# SM2000.net
KiCad netlist of a schematic drawn in EAGLE
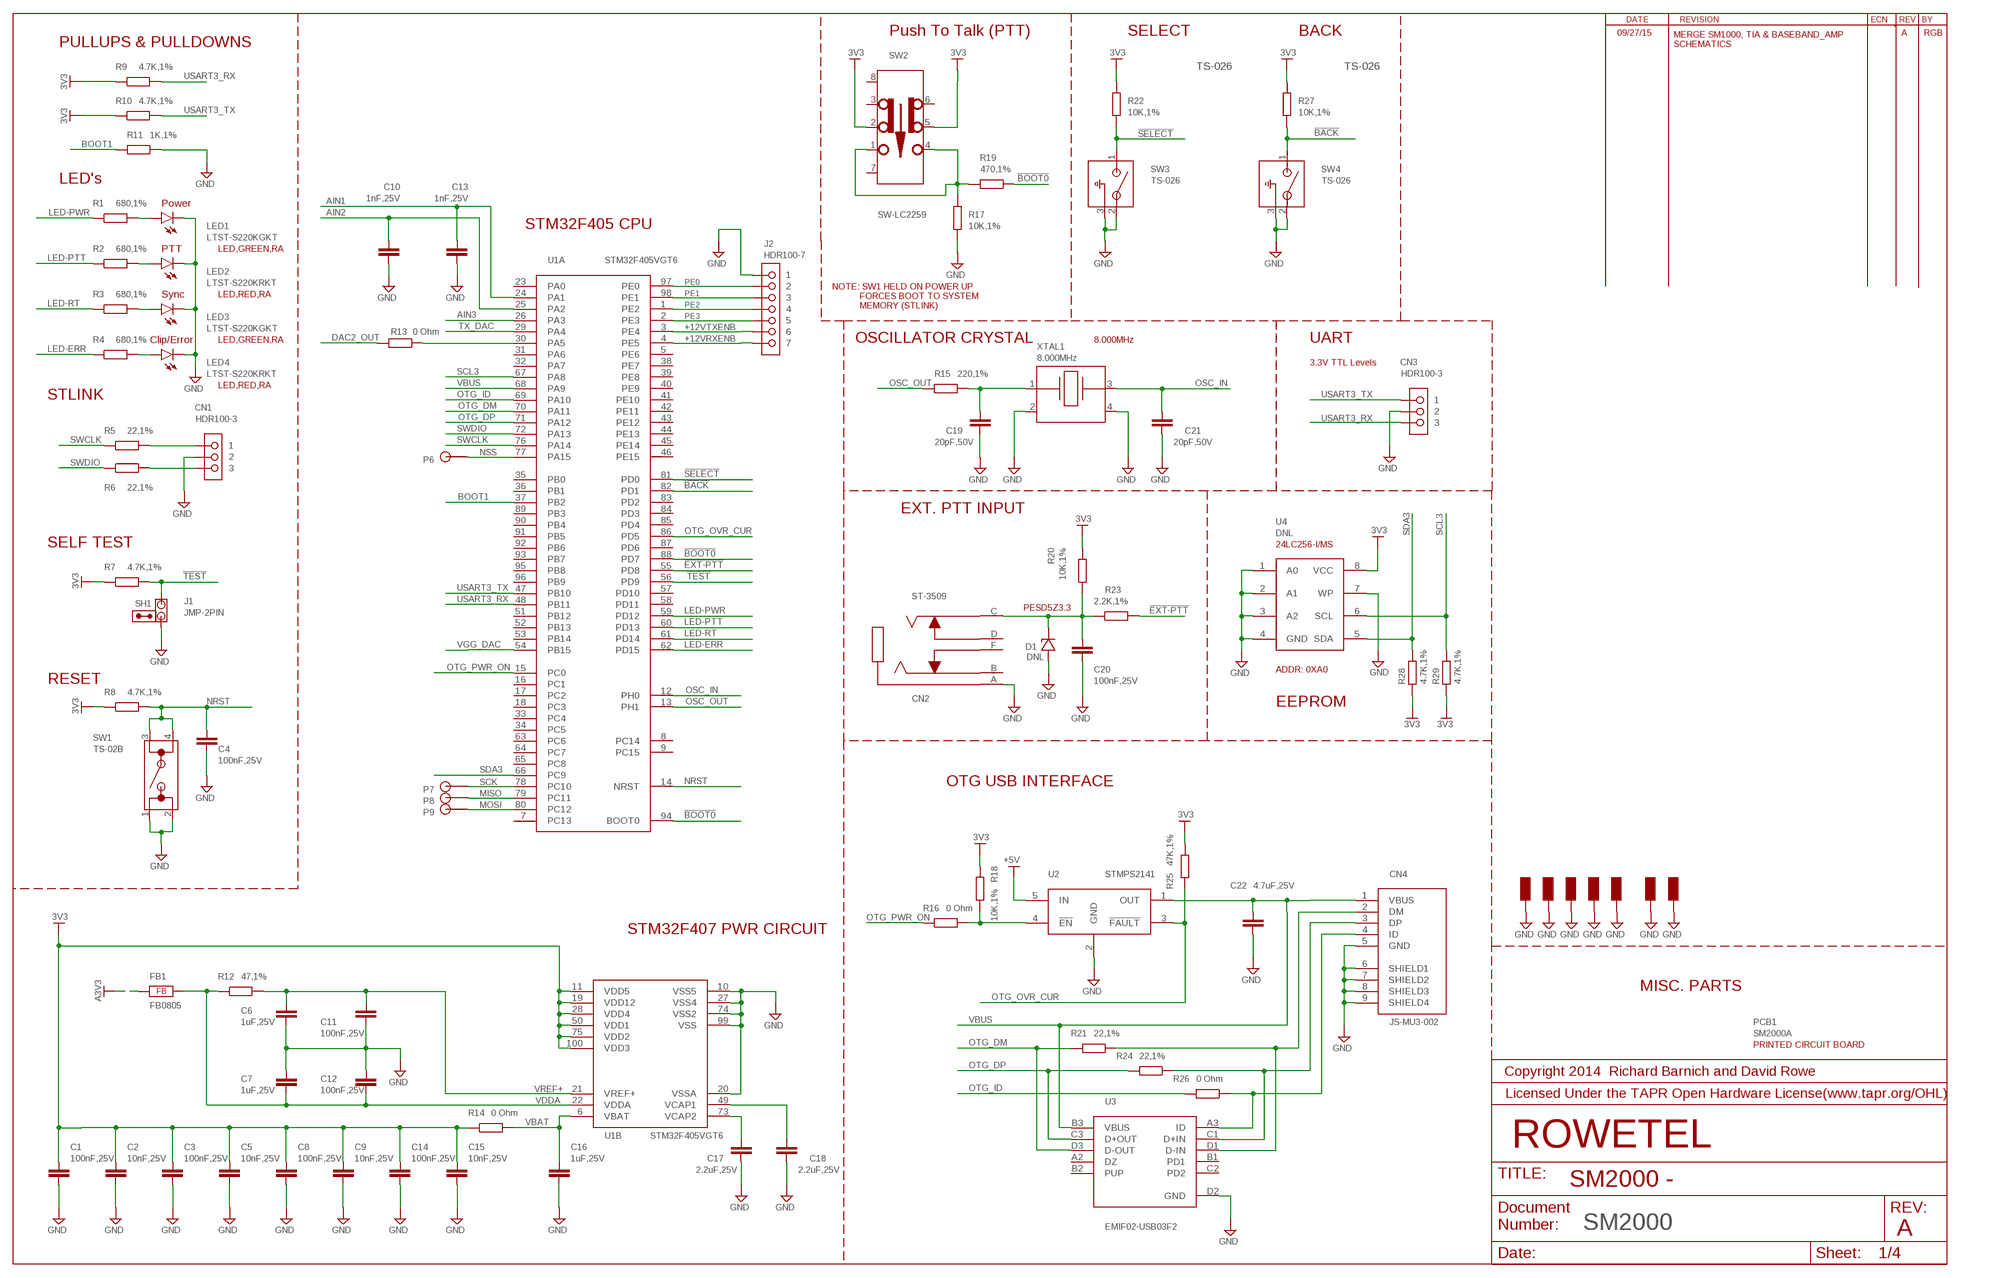
[diagram p0: schematic, sheet 1]
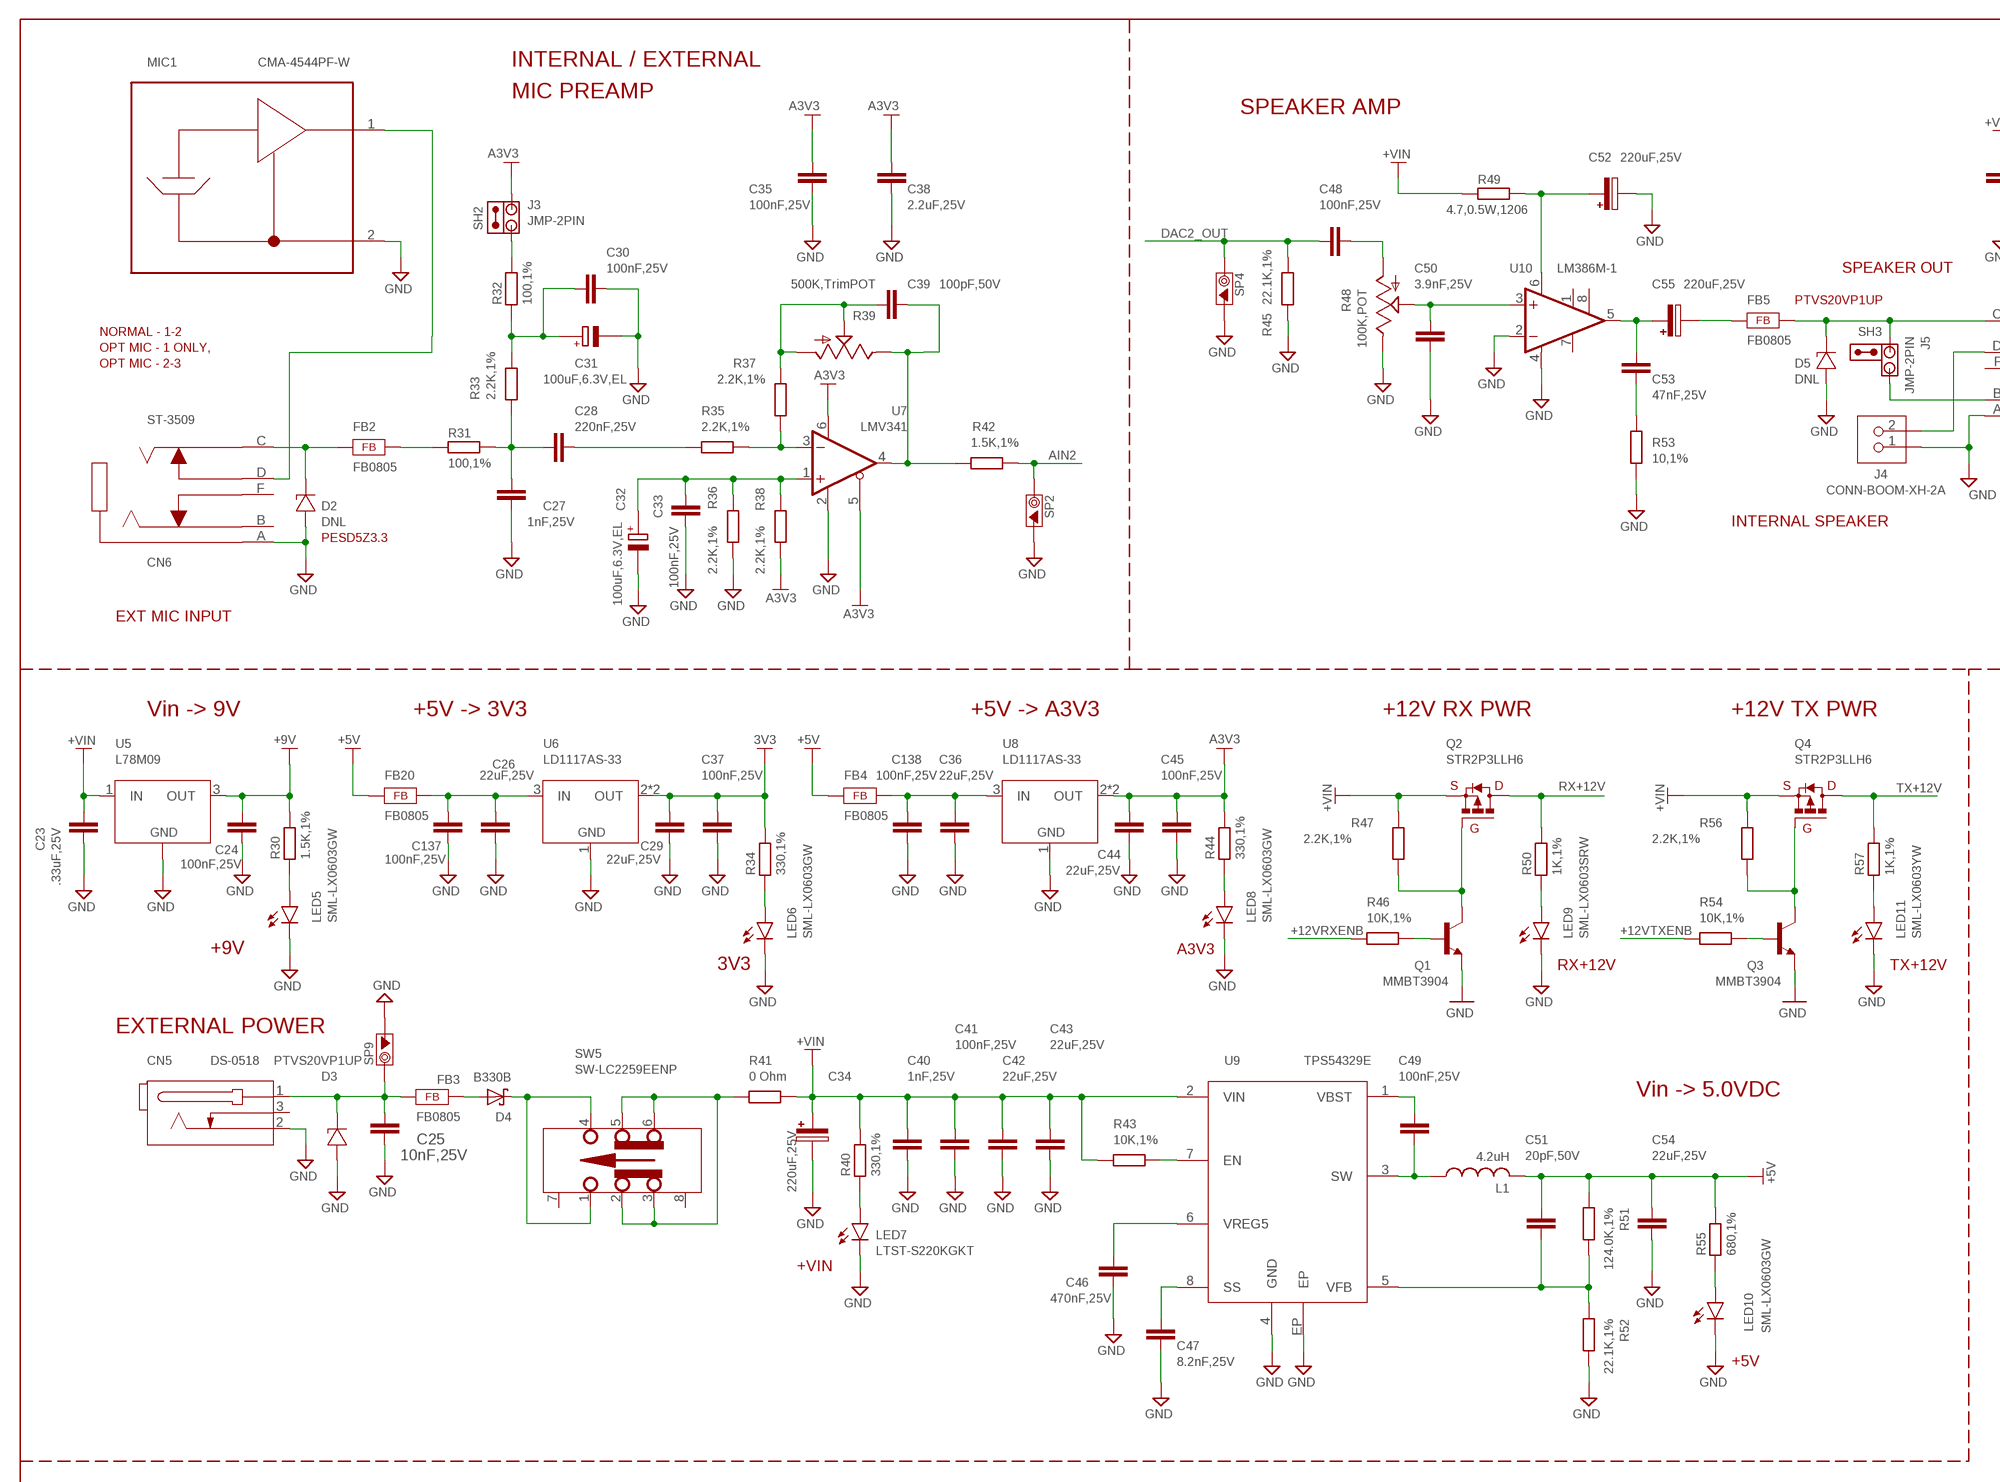
[diagram p1: schematic, sheet 2, part 1 of 2]
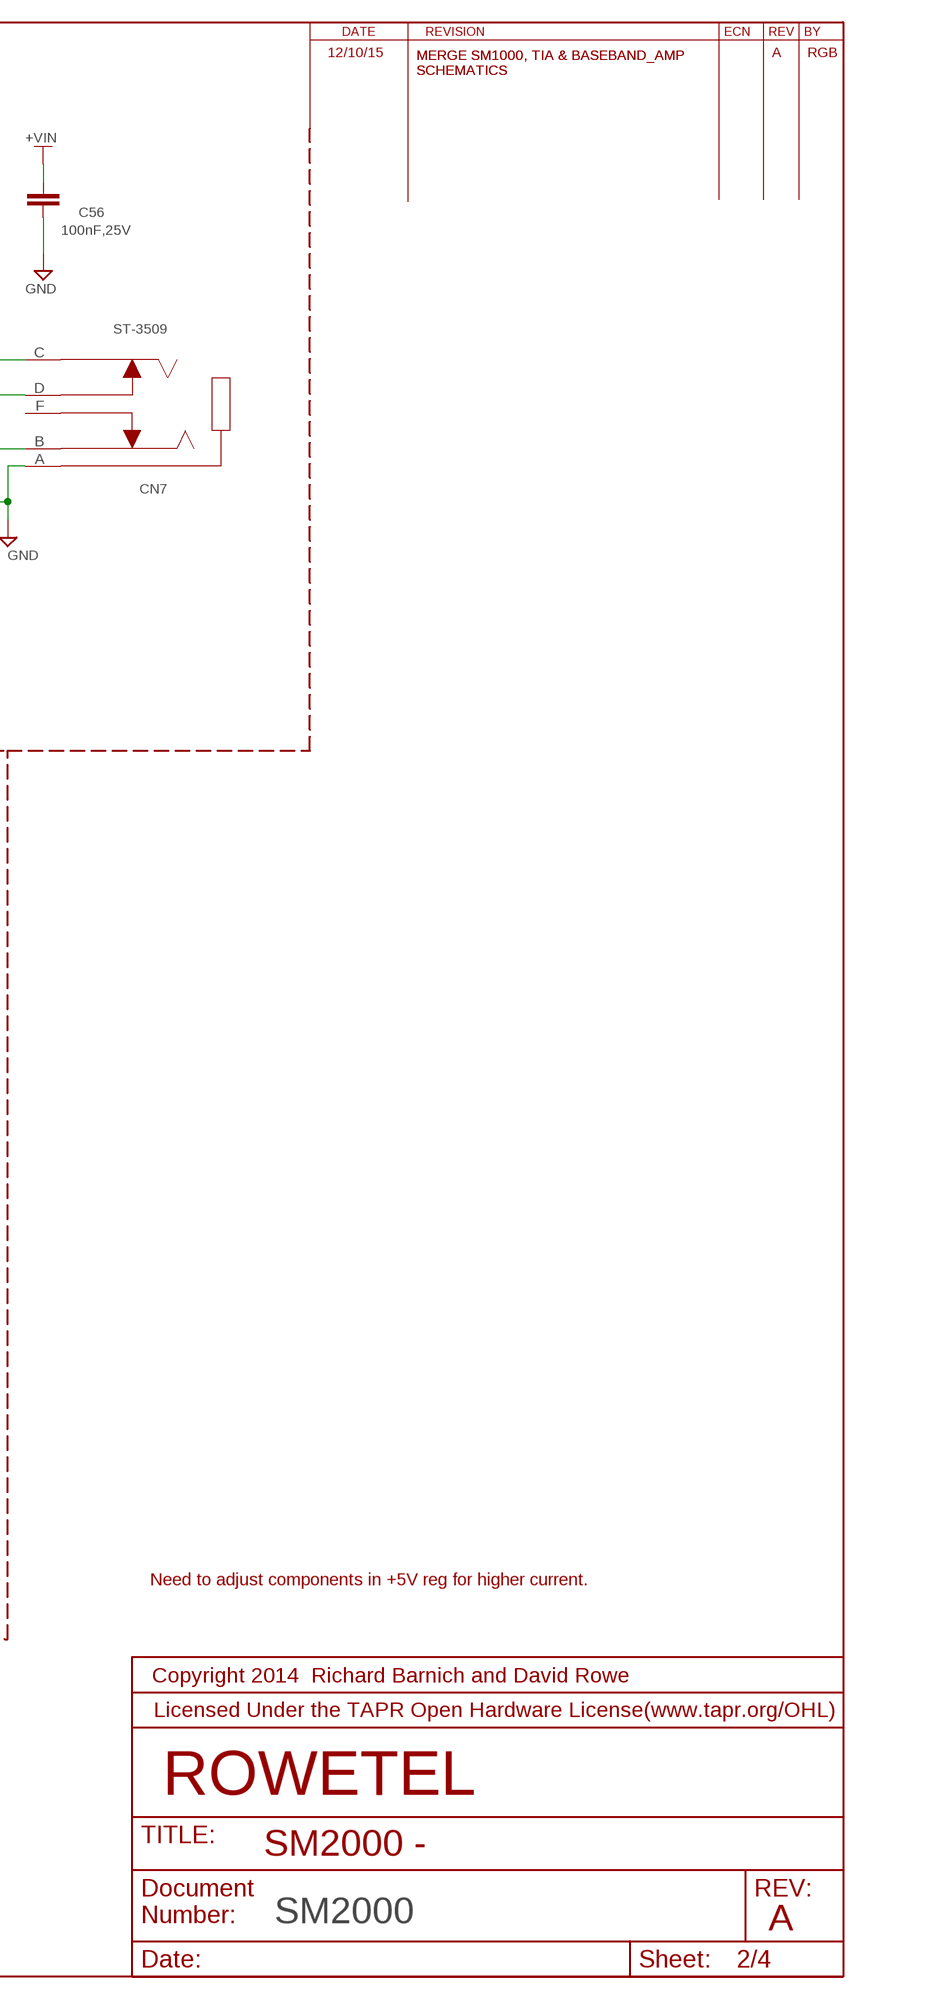
[diagram p2: schematic, sheet 2, part 2 of 2]
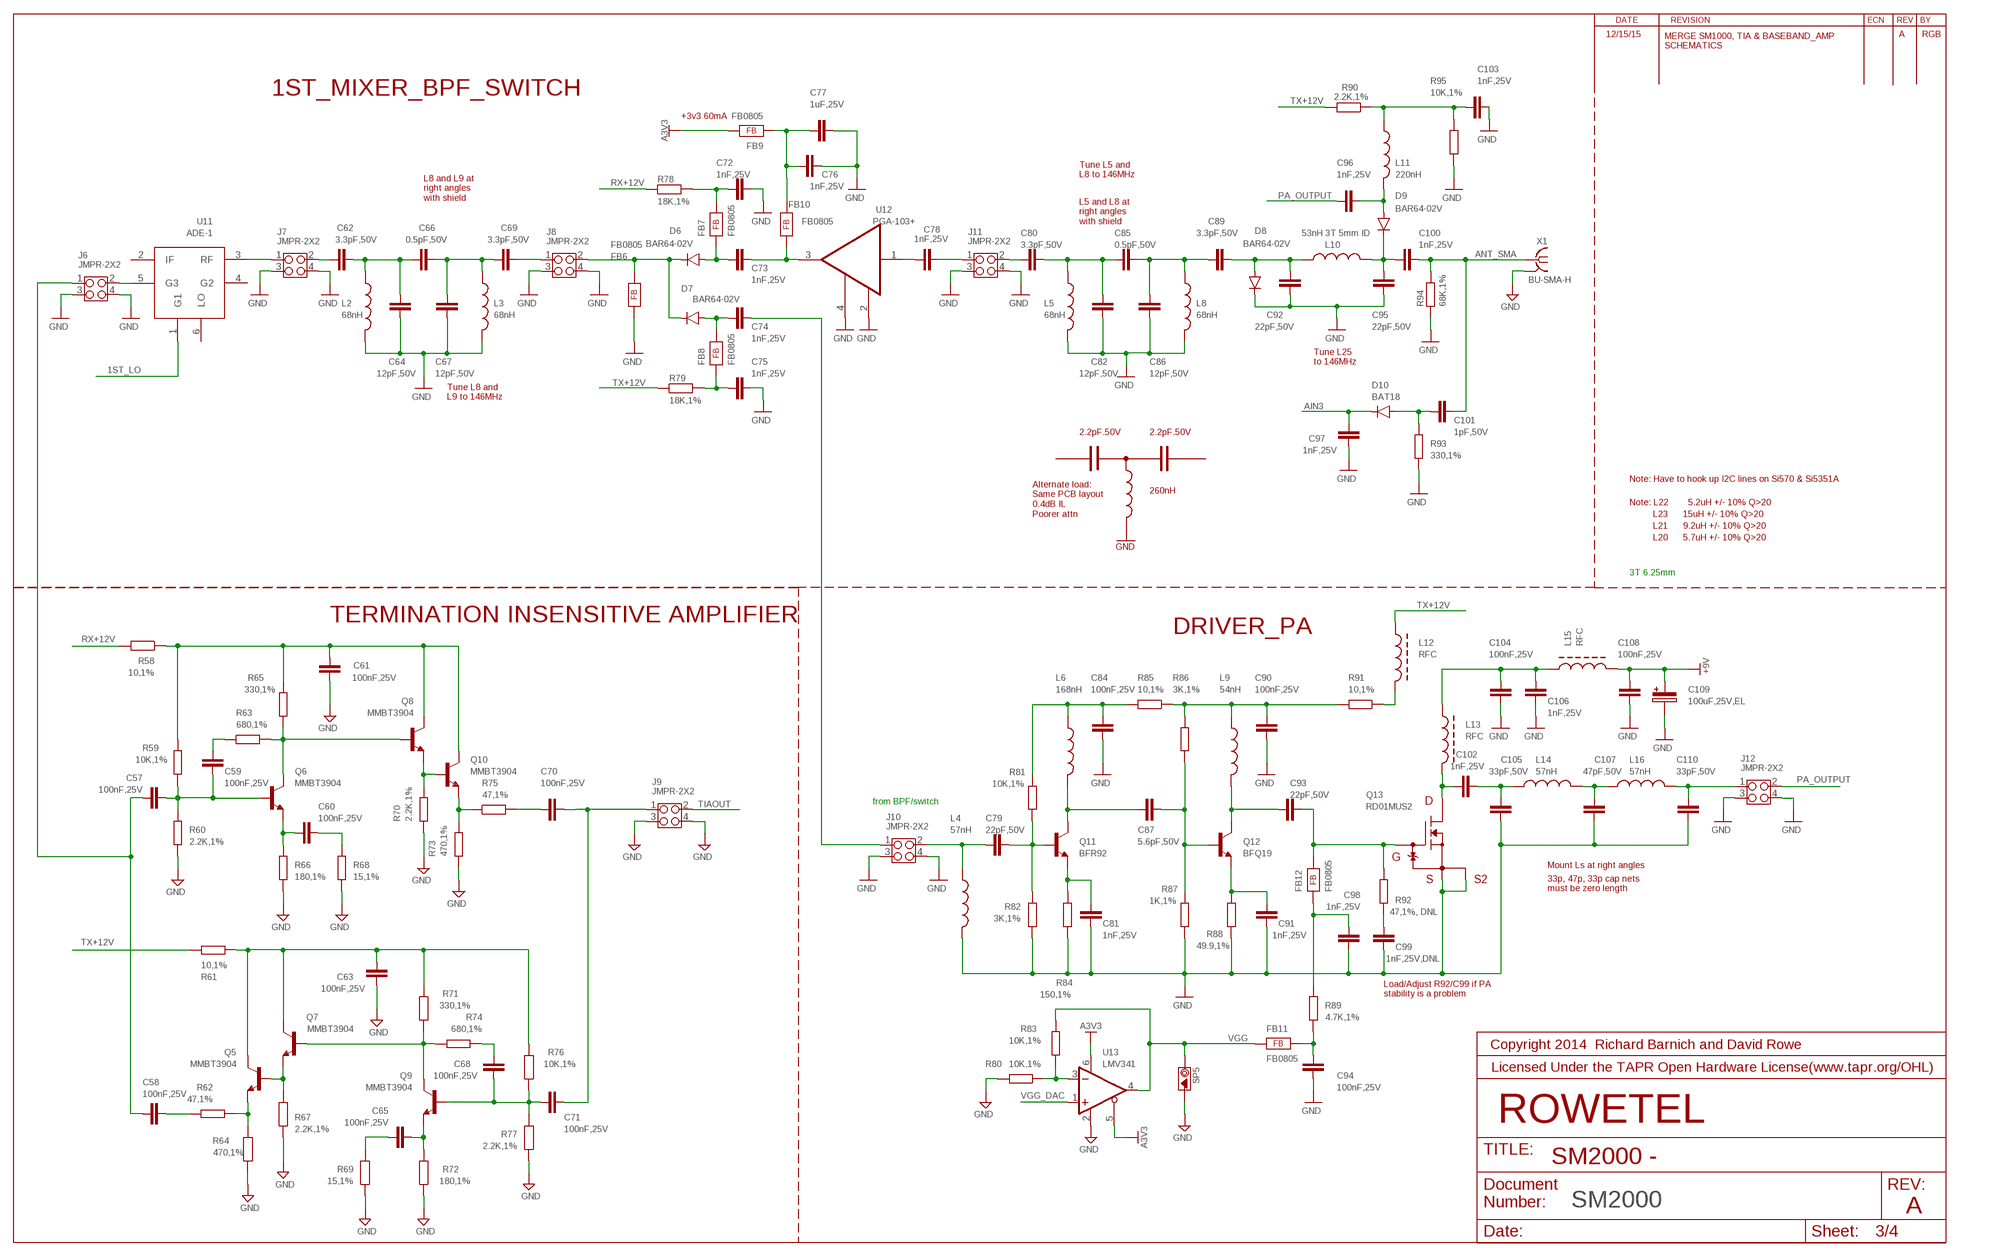
[diagram p3: schematic, sheet 3]
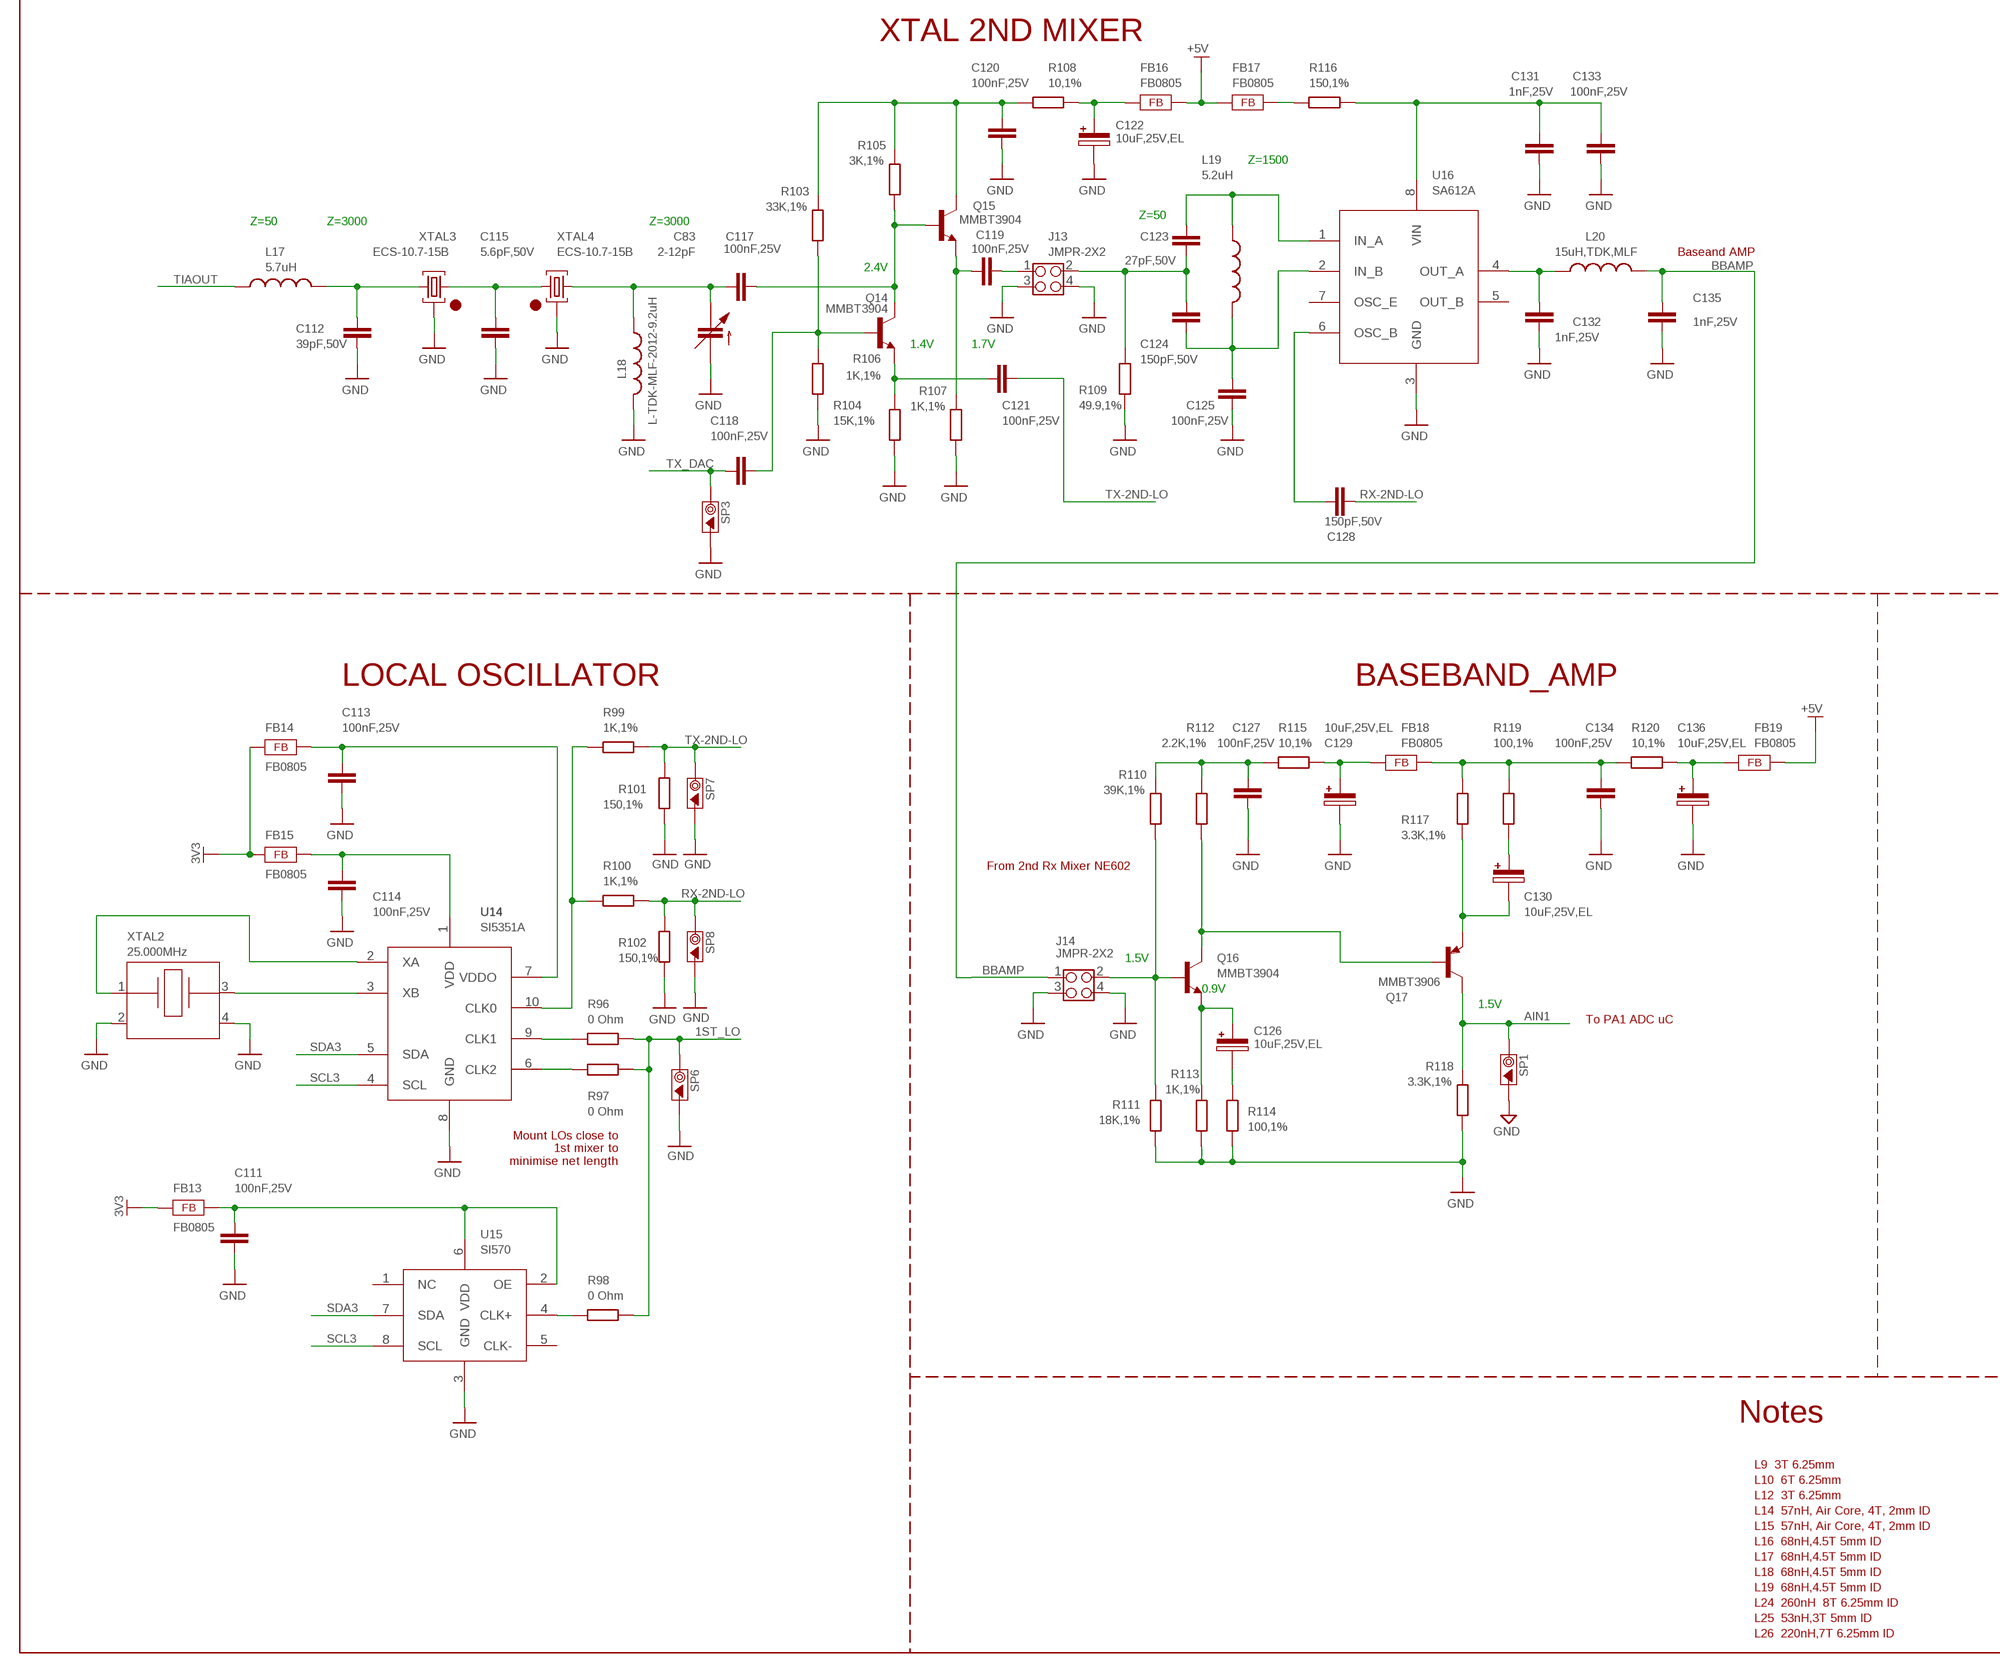
[diagram p4: schematic, sheet 4, part 1 of 2]
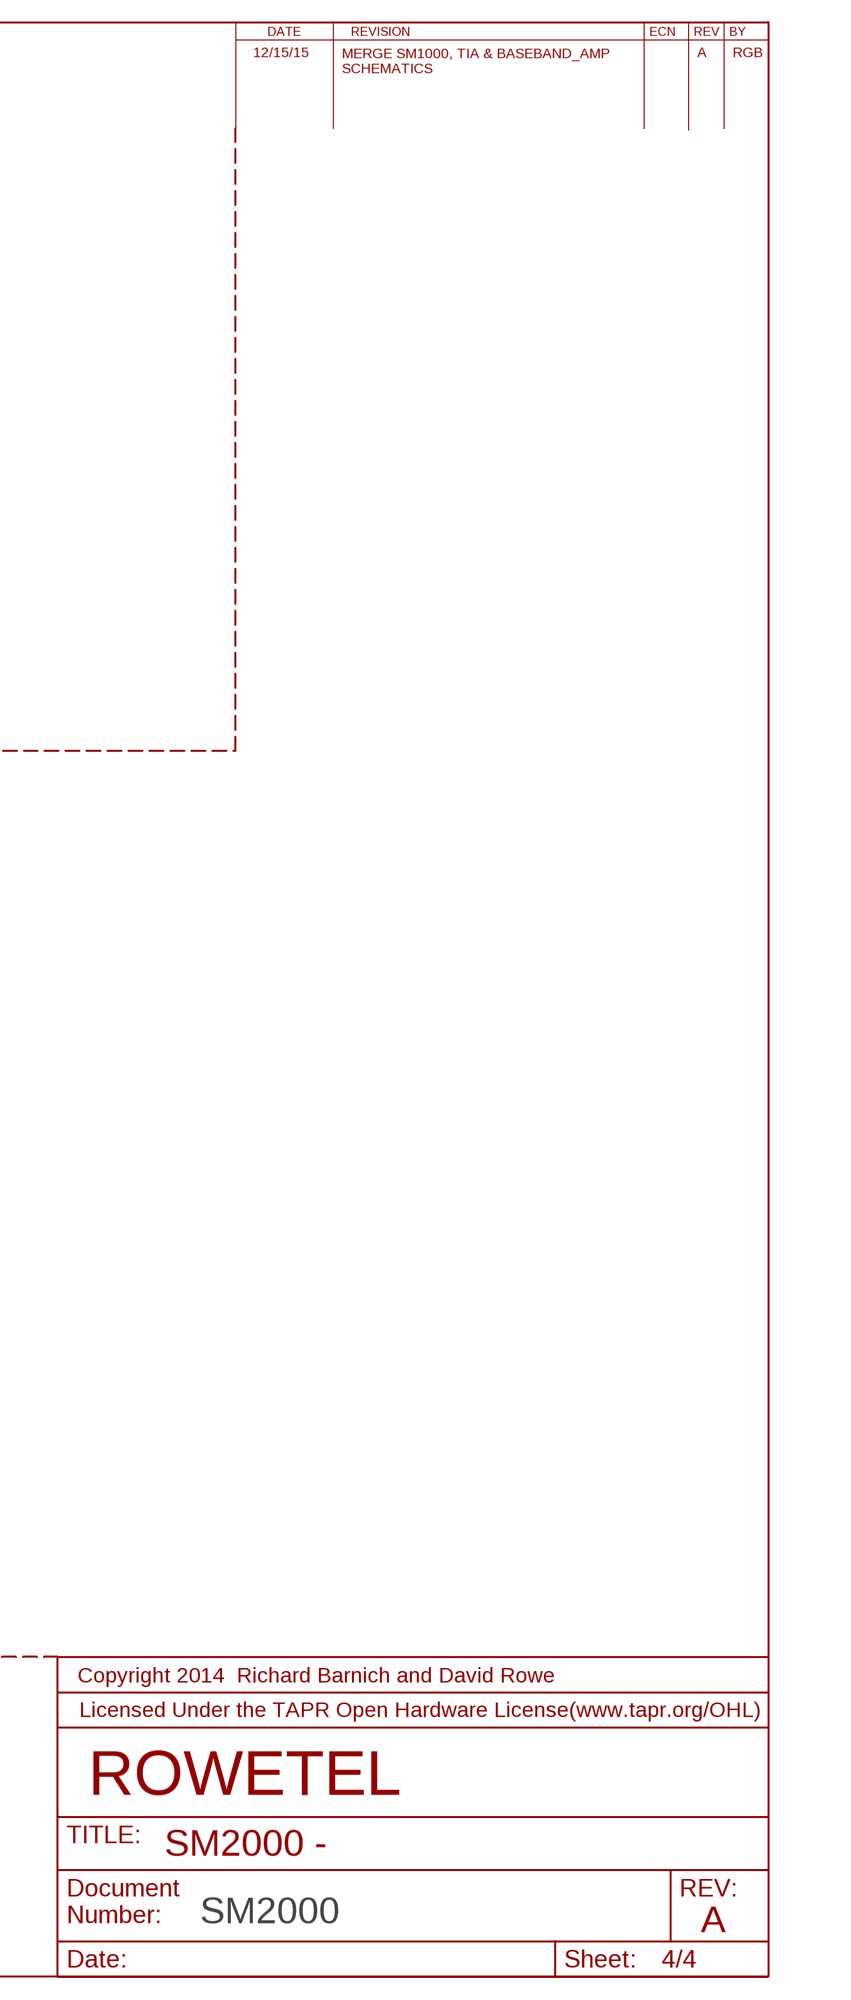
[diagram p5: schematic, sheet 4, part 2 of 2]

(export (version "E")
  (design (tool "Eeschema 10.0.6"))
  (components
    (comp (ref "C57")
      (value "100nF,25V")
      (footprint "eagle-import:C0805")
      (libsource (lib "eagle-import") (part "CAP-0805"))
    )
    (comp (ref "C58")
      (value "100nF,25V")
      (footprint "eagle-import:C0805")
      (libsource (lib "eagle-import") (part "CAP-0805"))
    )
    (comp (ref "C59")
      (value "100nF,25V")
      (footprint "eagle-import:C0805")
      (libsource (lib "eagle-import") (part "CAP-0805"))
    )
    (comp (ref "C60")
      (value "100nF,25V")
      (footprint "eagle-import:C0805")
      (libsource (lib "eagle-import") (part "CAP-0805"))
    )
    (comp (ref "C61")
      (value "100nF,25V")
      (footprint "eagle-import:C0805")
      (libsource (lib "eagle-import") (part "CAP-0805"))
    )
    (comp (ref "C62")
      (value "3.3pF,50V")
      (footprint "eagle-import:C0805")
      (libsource (lib "eagle-import") (part "CAP-0805"))
    )
    (comp (ref "C63")
      (value "100nF,25V")
      (footprint "eagle-import:C0805")
      (libsource (lib "eagle-import") (part "CAP-0805"))
    )
    (comp (ref "C64")
      (value "12pF,50V")
      (footprint "eagle-import:C0805")
      (libsource (lib "eagle-import") (part "CAP-0805"))
    )
    (comp (ref "C65")
      (value "100nF,25V")
      (footprint "eagle-import:C0805")
      (libsource (lib "eagle-import") (part "CAP-0805"))
    )
    (comp (ref "C66")
      (value "0.5pF,50V")
      (footprint "eagle-import:C0805")
      (libsource (lib "eagle-import") (part "CAP-0805"))
    )
    (comp (ref "C67")
      (value "12pF,50V")
      (footprint "eagle-import:C0805")
      (libsource (lib "eagle-import") (part "CAP-0805"))
    )
    (comp (ref "C68")
      (value "100nF,25V")
      (footprint "eagle-import:C0805")
      (libsource (lib "eagle-import") (part "CAP-0805"))
    )
    (comp (ref "C69")
      (value "3.3pF,50V")
      (footprint "eagle-import:C0805")
      (libsource (lib "eagle-import") (part "CAP-0805"))
    )
    (comp (ref "C70")
      (value "100nF,25V")
      (footprint "eagle-import:C0805")
      (libsource (lib "eagle-import") (part "CAP-0805"))
    )
    (comp (ref "C71")
      (value "100nF,25V")
      (footprint "eagle-import:C0805")
      (libsource (lib "eagle-import") (part "CAP-0805"))
    )
    (comp (ref "C72")
      (value "1nF,25V")
      (footprint "eagle-import:C0805")
      (libsource (lib "eagle-import") (part "CAP-0805"))
    )
    (comp (ref "C73")
      (value "1nF,25V")
      (footprint "eagle-import:C0805")
      (libsource (lib "eagle-import") (part "CAP-0805"))
    )
    (comp (ref "C74")
      (value "1nF,25V")
      (footprint "eagle-import:C0805")
      (libsource (lib "eagle-import") (part "CAP-0805"))
    )
    (comp (ref "C75")
      (value "1nF,25V")
      (footprint "eagle-import:C0805")
      (libsource (lib "eagle-import") (part "CAP-0805"))
    )
    (comp (ref "C76")
      (value "1nF,25V")
      (footprint "eagle-import:C0805")
      (libsource (lib "eagle-import") (part "CAP-0805"))
    )
    (comp (ref "C77")
      (value "1uF,25V")
      (footprint "eagle-import:C0805")
      (libsource (lib "eagle-import") (part "CAP-0805"))
    )
    (comp (ref "C78")
      (value "1nF,25V")
      (footprint "eagle-import:C0805")
      (libsource (lib "eagle-import") (part "CAP-0805"))
    )
    (comp (ref "C79")
      (value "22pF,50V")
      (footprint "eagle-import:C0805")
      (libsource (lib "eagle-import") (part "CAP-0805"))
    )
    (comp (ref "C80")
      (value "3.3pF,50V")
      (footprint "eagle-import:C0805")
      (libsource (lib "eagle-import") (part "CAP-0805"))
    )
    (comp (ref "C81")
      (value "1nF,25V")
      (footprint "eagle-import:C0805")
      (libsource (lib "eagle-import") (part "CAP-0805"))
    )
    (comp (ref "C82")
      (value "12pF,50V")
      (footprint "eagle-import:C0805")
      (libsource (lib "eagle-import") (part "CAP-0805"))
    )
    (comp (ref "C84")
      (value "100nF,25V")
      (footprint "eagle-import:C0805")
      (libsource (lib "eagle-import") (part "CAP-0805"))
    )
    (comp (ref "C85")
      (value "0.5pF,50V")
      (footprint "eagle-import:C0805")
      (libsource (lib "eagle-import") (part "CAP-0805"))
    )
    (comp (ref "C86")
      (value "12pF,50V")
      (footprint "eagle-import:C0805")
      (libsource (lib "eagle-import") (part "CAP-0805"))
    )
    (comp (ref "C87")
      (value "5.6pF,50V")
      (footprint "eagle-import:C0805")
      (libsource (lib "eagle-import") (part "CAP-0805"))
    )
    (comp (ref "C89")
      (value "3.3pF,50V")
      (footprint "eagle-import:C0805")
      (libsource (lib "eagle-import") (part "CAP-0805"))
    )
    (comp (ref "C90")
      (value "100nF,25V")
      (footprint "eagle-import:C0805")
      (libsource (lib "eagle-import") (part "CAP-0805"))
    )
    (comp (ref "C91")
      (value "1nF,25V")
      (footprint "eagle-import:C0805")
      (libsource (lib "eagle-import") (part "CAP-0805"))
    )
    (comp (ref "C92")
      (value "22pF,50V")
      (footprint "eagle-import:C0805")
      (libsource (lib "eagle-import") (part "CAP-0805"))
    )
    (comp (ref "C93")
      (value "22pF,50V")
      (footprint "eagle-import:C0805")
      (libsource (lib "eagle-import") (part "CAP-0805"))
    )
    (comp (ref "C94")
      (value "100nF,25V")
      (footprint "eagle-import:C0805")
      (libsource (lib "eagle-import") (part "CAP-0805"))
    )
    (comp (ref "C95")
      (value "22pF,50V")
      (footprint "eagle-import:C0805")
      (libsource (lib "eagle-import") (part "CAP-0805"))
    )
    (comp (ref "C96")
      (value "1nF,25V")
      (footprint "eagle-import:C0805")
      (libsource (lib "eagle-import") (part "CAP-0805"))
    )
    (comp (ref "C97")
      (value "1nF,25V")
      (footprint "eagle-import:C0805")
      (libsource (lib "eagle-import") (part "CAP-0805"))
    )
    (comp (ref "C98")
      (value "1nF,25V")
      (footprint "eagle-import:C0805")
      (libsource (lib "eagle-import") (part "CAP-0805"))
    )
    (comp (ref "C99")
      (value "1nF,25V,DNL")
      (footprint "eagle-import:C0805")
      (libsource (lib "eagle-import") (part "CAP-0805"))
    )
    (comp (ref "C100")
      (value "1nF,25V")
      (footprint "eagle-import:C0805")
      (libsource (lib "eagle-import") (part "CAP-0805"))
    )
    (comp (ref "C101")
      (value "1pF,50V")
      (footprint "eagle-import:C0805")
      (libsource (lib "eagle-import") (part "CAP-0805"))
    )
    (comp (ref "C102")
      (value "1nF,25V")
      (footprint "eagle-import:C0805")
      (libsource (lib "eagle-import") (part "CAP-0805"))
    )
    (comp (ref "C103")
      (value "1nF,25V")
      (footprint "eagle-import:C0805")
      (libsource (lib "eagle-import") (part "CAP-0805"))
    )
    (comp (ref "C104")
      (value "100nF,25V")
      (footprint "eagle-import:C0805")
      (libsource (lib "eagle-import") (part "CAP-0805"))
    )
    (comp (ref "C105")
      (value "33pF,50V")
      (footprint "eagle-import:C0805")
      (libsource (lib "eagle-import") (part "CAP-0805"))
    )
    (comp (ref "C106")
      (value "1nF,25V")
      (footprint "eagle-import:C0805")
      (libsource (lib "eagle-import") (part "CAP-0805"))
    )
    (comp (ref "C107")
      (value "47pF,50V")
      (footprint "eagle-import:C0805")
      (libsource (lib "eagle-import") (part "CAP-0805"))
    )
    (comp (ref "C108")
      (value "100nF,25V")
      (footprint "eagle-import:C0805")
      (libsource (lib "eagle-import") (part "CAP-0805"))
    )
    (comp (ref "C109")
      (value "100uF,25V,EL")
      (footprint "eagle-import:CAP-CHEMI-F80")
      (libsource (lib "eagle-import") (part "CAP-CHEMI-F80"))
    )
    (comp (ref "C110")
      (value "33pF,50V")
      (footprint "eagle-import:C0805")
      (libsource (lib "eagle-import") (part "CAP-0805"))
    )
    (comp (ref "D6")
      (value "BAR64-02V")
      (footprint "eagle-import:SC79_INFINEON")
      (libsource (lib "eagle-import") (part "BAR64-02V"))
    )
    (comp (ref "D7")
      (value "BAR64-02V")
      (footprint "eagle-import:SC79_INFINEON")
      (libsource (lib "eagle-import") (part "BAR64-02V"))
    )
    (comp (ref "D8")
      (value "BAR64-02V")
      (footprint "eagle-import:SC79_INFINEON")
      (libsource (lib "eagle-import") (part "BAR64-02V"))
    )
    (comp (ref "D9")
      (value "BAR64-02V")
      (footprint "eagle-import:SC79_INFINEON")
      (libsource (lib "eagle-import") (part "BAR64-02V"))
    )
    (comp (ref "D10")
      (value "BAT18")
      (footprint "eagle-import:SOT23")
      (libsource (lib "eagle-import") (part "BAT18"))
    )
    (comp (ref "FB6")
      (value "FB0805")
      (footprint "eagle-import:FE0805")
      (libsource (lib "eagle-import") (part "FB0805"))
    )
    (comp (ref "FB7")
      (value "FB0805")
      (footprint "eagle-import:FE0805")
      (libsource (lib "eagle-import") (part "FB0805"))
    )
    (comp (ref "FB8")
      (value "FB0805")
      (footprint "eagle-import:FE0805")
      (libsource (lib "eagle-import") (part "FB0805"))
    )
    (comp (ref "FB9")
      (value "FB0805")
      (footprint "eagle-import:FE0805")
      (libsource (lib "eagle-import") (part "FB0805"))
    )
    (comp (ref "FB10")
      (value "FB0805")
      (footprint "eagle-import:FE0805")
      (libsource (lib "eagle-import") (part "FB0805"))
    )
    (comp (ref "FB11")
      (value "FB0805")
      (footprint "eagle-import:FE0805")
      (libsource (lib "eagle-import") (part "FB0805"))
    )
    (comp (ref "FB12")
      (value "FB0805")
      (footprint "eagle-import:FE0805")
      (libsource (lib "eagle-import") (part "FB0805"))
    )
    (comp (ref "J6")
      (value "JMPR-2X2")
      (footprint "eagle-import:JMPR-2X2X.1")
      (libsource (lib "eagle-import") (part "JMPR-2X2"))
    )
    (comp (ref "J7")
      (value "JMPR-2X2")
      (footprint "eagle-import:JMPR-2X2X.1")
      (libsource (lib "eagle-import") (part "JMPR-2X2"))
    )
    (comp (ref "J8")
      (value "JMPR-2X2")
      (footprint "eagle-import:JMPR-2X2X.1")
      (libsource (lib "eagle-import") (part "JMPR-2X2"))
    )
    (comp (ref "J9")
      (value "JMPR-2X2")
      (footprint "eagle-import:JMPR-2X2X.1")
      (libsource (lib "eagle-import") (part "JMPR-2X2"))
    )
    (comp (ref "J10")
      (value "JMPR-2X2")
      (footprint "eagle-import:JMPR-2X2X.1")
      (libsource (lib "eagle-import") (part "JMPR-2X2"))
    )
    (comp (ref "J11")
      (value "JMPR-2X2")
      (footprint "eagle-import:JMPR-2X2X.1")
      (libsource (lib "eagle-import") (part "JMPR-2X2"))
    )
    (comp (ref "J12")
      (value "JMPR-2X2")
      (footprint "eagle-import:JMPR-2X2X.1")
      (libsource (lib "eagle-import") (part "JMPR-2X2"))
    )
    (comp (ref "L2")
      (value "68nH")
      (footprint "eagle-import:L10X15")
      (libsource (lib "eagle-import") (part "L-ROWE_15X10"))
    )
    (comp (ref "L3")
      (value "68nH")
      (footprint "eagle-import:L10X15")
      (libsource (lib "eagle-import") (part "L-ROWE_15X10"))
    )
    (comp (ref "L4")
      (value "57nH")
      (footprint "eagle-import:L10X15")
      (libsource (lib "eagle-import") (part "L-ROWE_15X10"))
    )
    (comp (ref "L5")
      (value "68nH")
      (footprint "eagle-import:L10X15")
      (libsource (lib "eagle-import") (part "L-ROWE_15X10"))
    )
    (comp (ref "L6")
      (value "168nH")
      (footprint "eagle-import:L10X15")
      (libsource (lib "eagle-import") (part "L-ROWE_15X10"))
    )
    (comp (ref "L8")
      (value "68nH")
      (footprint "eagle-import:L10X15")
      (libsource (lib "eagle-import") (part "L-ROWE_15X10"))
    )
    (comp (ref "L9")
      (value "54nH")
      (footprint "eagle-import:L10X15")
      (libsource (lib "eagle-import") (part "L-ROWE_15X10"))
    )
    (comp (ref "L10")
      (value "53nH 3T 5mm ID")
      (footprint "eagle-import:L10X15")
      (libsource (lib "eagle-import") (part "L-ROWE_15X10"))
    )
    (comp (ref "L11")
      (value "220nH")
      (footprint "eagle-import:L10X15")
      (libsource (lib "eagle-import") (part "L-ROWE_15X10"))
    )
    (comp (ref "L12")
      (value "RFC")
      (footprint "eagle-import:Z15_4")
      (libsource (lib "eagle-import") (part "RFC"))
    )
    (comp (ref "L13")
      (value "RFC")
      (footprint "eagle-import:Z15_4")
      (libsource (lib "eagle-import") (part "RFC"))
    )
    (comp (ref "L14")
      (value "57nH")
      (footprint "eagle-import:L10X15")
      (libsource (lib "eagle-import") (part "L-ROWE_15X10"))
    )
    (comp (ref "L15")
      (value "RFC")
      (footprint "eagle-import:Z15_4")
      (libsource (lib "eagle-import") (part "RFC"))
    )
    (comp (ref "L16")
      (value "57nH")
      (footprint "eagle-import:L10X15")
      (libsource (lib "eagle-import") (part "L-ROWE_15X10"))
    )
    (comp (ref "Q5")
      (value "MMBT3904")
      (footprint "eagle-import:SOT23")
      (libsource (lib "eagle-import") (part "MMBT3904"))
    )
    (comp (ref "Q6")
      (value "MMBT3904")
      (footprint "eagle-import:SOT23")
      (libsource (lib "eagle-import") (part "MMBT3904"))
    )
    (comp (ref "Q7")
      (value "MMBT3904")
      (footprint "eagle-import:SOT23")
      (libsource (lib "eagle-import") (part "MMBT3904"))
    )
    (comp (ref "Q8")
      (value "MMBT3904")
      (footprint "eagle-import:SOT23")
      (libsource (lib "eagle-import") (part "MMBT3904"))
    )
    (comp (ref "Q9")
      (value "MMBT3904")
      (footprint "eagle-import:SOT23")
      (libsource (lib "eagle-import") (part "MMBT3904"))
    )
    (comp (ref "Q10")
      (value "MMBT3904")
      (footprint "eagle-import:SOT23")
      (libsource (lib "eagle-import") (part "MMBT3904"))
    )
    (comp (ref "Q11")
      (value "BFR92")
      (footprint "eagle-import:SOT23")
      (libsource (lib "eagle-import") (part "BFR92"))
    )
    (comp (ref "Q12")
      (value "BFQ19")
      (footprint "eagle-import:SOT89")
      (libsource (lib "eagle-import") (part "BFQ19"))
    )
    (comp (ref "Q13")
      (value "RD01MUS2")
      (footprint "eagle-import:SOT89")
      (libsource (lib "eagle-import") (part "RD01MUS2"))
    )
    (comp (ref "R58")
      (value "10,1%")
      (footprint "eagle-import:R0805")
      (libsource (lib "eagle-import") (part "RES-0805"))
    )
    (comp (ref "R59")
      (value "10K,1%")
      (footprint "eagle-import:R0805")
      (libsource (lib "eagle-import") (part "RES-0805"))
    )
    (comp (ref "R60")
      (value "2.2K,1%")
      (footprint "eagle-import:R0805")
      (libsource (lib "eagle-import") (part "RES-0805"))
    )
    (comp (ref "R61")
      (value "10,1%")
      (footprint "eagle-import:R0805")
      (libsource (lib "eagle-import") (part "RES-0805"))
    )
    (comp (ref "R62")
      (value "47,1%")
      (footprint "eagle-import:R0805")
      (libsource (lib "eagle-import") (part "RES-0805"))
    )
    (comp (ref "R63")
      (value "680,1%")
      (footprint "eagle-import:R0805")
      (libsource (lib "eagle-import") (part "RES-0805"))
    )
    (comp (ref "R64")
      (value "470,1%")
      (footprint "eagle-import:R0805")
      (libsource (lib "eagle-import") (part "RES-0805"))
    )
    (comp (ref "R65")
      (value "330,1%")
      (footprint "eagle-import:R0805")
      (libsource (lib "eagle-import") (part "RES-0805"))
    )
    (comp (ref "R66")
      (value "180,1%")
      (footprint "eagle-import:R0805")
      (libsource (lib "eagle-import") (part "RES-0805"))
    )
    (comp (ref "R67")
      (value "2.2K,1%")
      (footprint "eagle-import:R0805")
      (libsource (lib "eagle-import") (part "RES-0805"))
    )
    (comp (ref "R68")
      (value "15,1%")
      (footprint "eagle-import:R0805")
      (libsource (lib "eagle-import") (part "RES-0805"))
    )
    (comp (ref "R69")
      (value "15,1%")
      (footprint "eagle-import:R0805")
      (libsource (lib "eagle-import") (part "RES-0805"))
    )
    (comp (ref "R70")
      (value "2.2K,1%")
      (footprint "eagle-import:R0805")
      (libsource (lib "eagle-import") (part "RES-0805"))
    )
    (comp (ref "R71")
      (value "330,1%")
      (footprint "eagle-import:R0805")
      (libsource (lib "eagle-import") (part "RES-0805"))
    )
    (comp (ref "R72")
      (value "180,1%")
      (footprint "eagle-import:R0805")
      (libsource (lib "eagle-import") (part "RES-0805"))
    )
    (comp (ref "R73")
      (value "470,1%")
      (footprint "eagle-import:R0805")
      (libsource (lib "eagle-import") (part "RES-0805"))
    )
    (comp (ref "R74")
      (value "680,1%")
      (footprint "eagle-import:R0805")
      (libsource (lib "eagle-import") (part "RES-0805"))
    )
    (comp (ref "R75")
      (value "47,1%")
      (footprint "eagle-import:R0805")
      (libsource (lib "eagle-import") (part "RES-0805"))
    )
    (comp (ref "R76")
      (value "10K,1%")
      (footprint "eagle-import:R0805")
      (libsource (lib "eagle-import") (part "RES-0805"))
    )
    (comp (ref "R77")
      (value "2.2K,1%")
      (footprint "eagle-import:R0805")
      (libsource (lib "eagle-import") (part "RES-0805"))
    )
    (comp (ref "R78")
      (value "18K,1%")
      (footprint "eagle-import:R0805")
      (libsource (lib "eagle-import") (part "RES-0805"))
    )
    (comp (ref "R79")
      (value "18K,1%")
      (footprint "eagle-import:R0805")
      (libsource (lib "eagle-import") (part "RES-0805"))
    )
    (comp (ref "R80")
      (value "10K,1%")
      (footprint "eagle-import:R0805")
      (libsource (lib "eagle-import") (part "RES-0805"))
    )
    (comp (ref "R81")
      (value "10K,1%")
      (footprint "eagle-import:R0805")
      (libsource (lib "eagle-import") (part "RES-0805"))
    )
    (comp (ref "R82")
      (value "3K,1%")
      (footprint "eagle-import:R0805")
      (libsource (lib "eagle-import") (part "RES-0805"))
    )
    (comp (ref "R83")
      (value "10K,1%")
      (footprint "eagle-import:R0805")
      (libsource (lib "eagle-import") (part "RES-0805"))
    )
    (comp (ref "R84")
      (value "150,1%")
      (footprint "eagle-import:R0805")
      (libsource (lib "eagle-import") (part "RES-0805"))
    )
    (comp (ref "R85")
      (value "10,1%")
      (footprint "eagle-import:R0805")
      (libsource (lib "eagle-import") (part "RES-0805"))
    )
    (comp (ref "R86")
      (value "3K,1%")
      (footprint "eagle-import:R0805")
      (libsource (lib "eagle-import") (part "RES-0805"))
    )
    (comp (ref "R87")
      (value "1K,1%")
      (footprint "eagle-import:R0805")
      (libsource (lib "eagle-import") (part "RES-0805"))
    )
    (comp (ref "R88")
      (value "49.9,1%")
      (footprint "eagle-import:R0805")
      (libsource (lib "eagle-import") (part "RES-0805"))
    )
    (comp (ref "R89")
      (value "4.7K,1%")
      (footprint "eagle-import:R0805")
      (libsource (lib "eagle-import") (part "RES-0805"))
    )
    (comp (ref "R90")
      (value "2.2K,1%")
      (footprint "eagle-import:R0805")
      (libsource (lib "eagle-import") (part "RES-0805"))
    )
    (comp (ref "R91")
      (value "10,1%")
      (footprint "eagle-import:R0805")
      (libsource (lib "eagle-import") (part "RES-0805"))
    )
    (comp (ref "R92")
      (value "47,1%, DNL")
      (footprint "eagle-import:R0805")
      (libsource (lib "eagle-import") (part "RES-0805"))
    )
    (comp (ref "R93")
      (value "330,1%")
      (footprint "eagle-import:R0805")
      (libsource (lib "eagle-import") (part "RES-0805"))
    )
    (comp (ref "R94")
      (value "68K,1%")
      (footprint "eagle-import:R0805")
      (libsource (lib "eagle-import") (part "RES-0805"))
    )
    (comp (ref "R95")
      (value "10K,1%")
      (footprint "eagle-import:R0805")
      (libsource (lib "eagle-import") (part "RES-0805"))
    )
    (comp (ref "SP5")
      (value "SCOPE_PAD")
      (footprint "eagle-import:SCOPE_PAD")
      (libsource (lib "eagle-import") (part "SCOPE_PAD"))
    )
    (comp (ref "U11")
      (value "ADE-1")
      (footprint "eagle-import:ADE-1")
      (libsource (lib "eagle-import") (part "ADE-1"))
    )
    (comp (ref "U12")
      (value "PGA-103+")
      (footprint "eagle-import:DF782")
      (libsource (lib "eagle-import") (part "PGA-103+"))
    )
    (comp (ref "U13")
      (value "LMV341")
      (footprint "eagle-import:SOT23-6")
      (libsource (lib "eagle-import") (part "LMV341"))
    )
    (comp (ref "X1")
      (value "BU-SMA-H")
      (footprint "eagle-import:BU-SMA-H")
      (libsource (lib "eagle-import") (part "BU-SMA-H"))
    )
    (comp (ref "C1")
      (value "100nF,25V")
      (footprint "eagle-import:C0805")
      (libsource (lib "eagle-import") (part "CAP-0805"))
    )
    (comp (ref "C2")
      (value "10nF,25V")
      (footprint "eagle-import:C0805")
      (libsource (lib "eagle-import") (part "CAP-0805"))
    )
    (comp (ref "C3")
      (value "100nF,25V")
      (footprint "eagle-import:C0805")
      (libsource (lib "eagle-import") (part "CAP-0805"))
    )
    (comp (ref "C4")
      (value "100nF,25V")
      (footprint "eagle-import:C0805")
      (libsource (lib "eagle-import") (part "CAP-0805"))
    )
    (comp (ref "C5")
      (value "10nF,25V")
      (footprint "eagle-import:C0805")
      (libsource (lib "eagle-import") (part "CAP-0805"))
    )
    (comp (ref "C6")
      (value "1uF,25V")
      (footprint "eagle-import:C0805")
      (libsource (lib "eagle-import") (part "CAP-0805"))
    )
    (comp (ref "C7")
      (value "1uF,25V")
      (footprint "eagle-import:C0805")
      (libsource (lib "eagle-import") (part "CAP-0805"))
    )
    (comp (ref "C8")
      (value "100nF,25V")
      (footprint "eagle-import:C0805")
      (libsource (lib "eagle-import") (part "CAP-0805"))
    )
    (comp (ref "C9")
      (value "10nF,25V")
      (footprint "eagle-import:C0805")
      (libsource (lib "eagle-import") (part "CAP-0805"))
    )
    (comp (ref "C10")
      (value "1nF,25V")
      (footprint "eagle-import:C0805")
      (libsource (lib "eagle-import") (part "CAP-0805"))
    )
    (comp (ref "C11")
      (value "100nF,25V")
      (footprint "eagle-import:C0805")
      (libsource (lib "eagle-import") (part "CAP-0805"))
    )
    (comp (ref "C12")
      (value "100nF,25V")
      (footprint "eagle-import:C0805")
      (libsource (lib "eagle-import") (part "CAP-0805"))
    )
    (comp (ref "C13")
      (value "1nF,25V")
      (footprint "eagle-import:C0805")
      (libsource (lib "eagle-import") (part "CAP-0805"))
    )
    (comp (ref "C14")
      (value "100nF,25V")
      (footprint "eagle-import:C0805")
      (libsource (lib "eagle-import") (part "CAP-0805"))
    )
    (comp (ref "C15")
      (value "10nF,25V")
      (footprint "eagle-import:C0805")
      (libsource (lib "eagle-import") (part "CAP-0805"))
    )
    (comp (ref "C16")
      (value "1uF,25V")
      (footprint "eagle-import:C0805")
      (libsource (lib "eagle-import") (part "CAP-0805"))
    )
    (comp (ref "C17")
      (value "2.2uF,25V")
      (footprint "eagle-import:C0805")
      (libsource (lib "eagle-import") (part "CAP-0805"))
    )
    (comp (ref "C18")
      (value "2.2uF,25V")
      (footprint "eagle-import:C0805")
      (libsource (lib "eagle-import") (part "CAP-0805"))
    )
    (comp (ref "C19")
      (value "20pF,50V")
      (footprint "eagle-import:C0805")
      (libsource (lib "eagle-import") (part "CAP-0805"))
    )
    (comp (ref "C20")
      (value "100nF,25V")
      (footprint "eagle-import:C0805")
      (libsource (lib "eagle-import") (part "CAP-0805"))
    )
    (comp (ref "C21")
      (value "20pF,50V")
      (footprint "eagle-import:C0805")
      (libsource (lib "eagle-import") (part "CAP-0805"))
    )
    (comp (ref "C22")
      (value "4.7uF,25V")
      (footprint "eagle-import:C0805")
      (libsource (lib "eagle-import") (part "CAP-0805"))
    )
    (comp (ref "CN1")
      (value "HDR100-3")
      (footprint "eagle-import:HDR100-3")
      (libsource (lib "eagle-import") (part "HDR100-3"))
    )
    (comp (ref "CN2")
      (value "ST-3509")
      (footprint "eagle-import:ST-3509")
      (libsource (lib "eagle-import") (part "ST-3509"))
    )
    (comp (ref "CN3")
      (value "HDR100-3")
      (footprint "eagle-import:HDR100-3")
      (libsource (lib "eagle-import") (part "HDR100-3"))
    )
    (comp (ref "CN4")
      (value "JS-MU3-002")
      (footprint "eagle-import:JI-MU3-002")
      (libsource (lib "eagle-import") (part "JS-MU3-002"))
    )
    (comp (ref "D1")
      (value "DNL")
      (footprint "eagle-import:SOD523")
      (libsource (lib "eagle-import") (part "PESD5ZX"))
    )
    (comp (ref "FB1")
      (value "FB0805")
      (footprint "eagle-import:FE0805")
      (libsource (lib "eagle-import") (part "FB0805"))
    )
    (comp (ref "J1")
      (value "JMP-2PIN")
      (footprint "eagle-import:JMPR-2PIN")
      (libsource (lib "eagle-import") (part "JMP-2PIN"))
    )
    (comp (ref "J2")
      (value "HDR100-7")
      (footprint "eagle-import:HDR100-7")
      (libsource (lib "eagle-import") (part "HDR100-7"))
    )
    (comp (ref "LED1")
      (value "LTST-S220KGKT")
      (footprint "eagle-import:LTST-S2200K")
      (libsource (lib "eagle-import") (part "LTST-S220K"))
    )
    (comp (ref "LED2")
      (value "LTST-S220KRKT")
      (footprint "eagle-import:LTST-S2200K")
      (libsource (lib "eagle-import") (part "LTST-S220K"))
    )
    (comp (ref "LED3")
      (value "LTST-S220KGKT")
      (footprint "eagle-import:LTST-S2200K")
      (libsource (lib "eagle-import") (part "LTST-S220K"))
    )
    (comp (ref "LED4")
      (value "LTST-S220KRKT")
      (footprint "eagle-import:LTST-S2200K")
      (libsource (lib "eagle-import") (part "LTST-S220K"))
    )
    (comp (ref "P6")
      (value "TPAD50")
      (footprint "eagle-import:TPAD50")
      (libsource (lib "eagle-import") (part "TPAD50"))
    )
    (comp (ref "P7")
      (value "TPAD50")
      (footprint "eagle-import:TPAD50")
      (libsource (lib "eagle-import") (part "TPAD50"))
    )
    (comp (ref "P8")
      (value "TPAD50")
      (footprint "eagle-import:TPAD50")
      (libsource (lib "eagle-import") (part "TPAD50"))
    )
    (comp (ref "P9")
      (value "TPAD50")
      (footprint "eagle-import:TPAD50")
      (libsource (lib "eagle-import") (part "TPAD50"))
    )
    (comp (ref "PCB1")
      (value "SM2000A")
      (footprint "eagle-import:NOPACKAGE")
      (libsource (lib "eagle-import") (part "PCB"))
    )
    (comp (ref "R1")
      (value "680,1%")
      (footprint "eagle-import:R0805")
      (libsource (lib "eagle-import") (part "RES-0805"))
    )
    (comp (ref "R2")
      (value "680,1%")
      (footprint "eagle-import:R0805")
      (libsource (lib "eagle-import") (part "RES-0805"))
    )
    (comp (ref "R3")
      (value "680,1%")
      (footprint "eagle-import:R0805")
      (libsource (lib "eagle-import") (part "RES-0805"))
    )
    (comp (ref "R4")
      (value "680,1%")
      (footprint "eagle-import:R0805")
      (libsource (lib "eagle-import") (part "RES-0805"))
    )
    (comp (ref "R5")
      (value "22,1%")
      (footprint "eagle-import:R0805")
      (libsource (lib "eagle-import") (part "RES-0805"))
    )
    (comp (ref "R6")
      (value "22,1%")
      (footprint "eagle-import:R0805")
      (libsource (lib "eagle-import") (part "RES-0805"))
    )
    (comp (ref "R7")
      (value "4.7K,1%")
      (footprint "eagle-import:R0805")
      (libsource (lib "eagle-import") (part "RES-0805"))
    )
    (comp (ref "R8")
      (value "4.7K,1%")
      (footprint "eagle-import:R0805")
      (libsource (lib "eagle-import") (part "RES-0805"))
    )
    (comp (ref "R9")
      (value "4.7K,1%")
      (footprint "eagle-import:R0805")
      (libsource (lib "eagle-import") (part "RES-0805"))
    )
    (comp (ref "R10")
      (value "4.7K,1%")
      (footprint "eagle-import:R0805")
      (libsource (lib "eagle-import") (part "RES-0805"))
    )
    (comp (ref "R11")
      (value "1K,1%")
      (footprint "eagle-import:R0805")
      (libsource (lib "eagle-import") (part "RES-0805"))
    )
    (comp (ref "R12")
      (value "47,1%")
      (footprint "eagle-import:R0805")
      (libsource (lib "eagle-import") (part "RES-0805"))
    )
    (comp (ref "R13")
      (value "0 Ohm")
      (footprint "eagle-import:R0805")
      (libsource (lib "eagle-import") (part "RES-0805"))
    )
    (comp (ref "R14")
      (value "0 Ohm")
      (footprint "eagle-import:R0805")
      (libsource (lib "eagle-import") (part "RES-0805"))
    )
    (comp (ref "R15")
      (value "220,1%")
      (footprint "eagle-import:R0805")
      (libsource (lib "eagle-import") (part "RES-0805"))
    )
    (comp (ref "R16")
      (value "0 Ohm")
      (footprint "eagle-import:R0805")
      (libsource (lib "eagle-import") (part "RES-0805"))
    )
    (comp (ref "R17")
      (value "10K,1%")
      (footprint "eagle-import:R0805")
      (libsource (lib "eagle-import") (part "RES-0805"))
    )
    (comp (ref "R18")
      (value "10K,1%")
      (footprint "eagle-import:R0805")
      (libsource (lib "eagle-import") (part "RES-0805"))
    )
    (comp (ref "R19")
      (value "470,1%")
      (footprint "eagle-import:R0805")
      (libsource (lib "eagle-import") (part "RES-0805"))
    )
    (comp (ref "R20")
      (value "10K,1%")
      (footprint "eagle-import:R0805")
      (libsource (lib "eagle-import") (part "RES-0805"))
    )
    (comp (ref "R21")
      (value "22,1%")
      (footprint "eagle-import:R0805")
      (libsource (lib "eagle-import") (part "RES-0805"))
    )
    (comp (ref "R22")
      (value "10K,1%")
      (footprint "eagle-import:R0805")
      (libsource (lib "eagle-import") (part "RES-0805"))
    )
    (comp (ref "R23")
      (value "2.2K,1%")
      (footprint "eagle-import:R0805")
      (libsource (lib "eagle-import") (part "RES-0805"))
    )
    (comp (ref "R24")
      (value "22,1%")
      (footprint "eagle-import:R0805")
      (libsource (lib "eagle-import") (part "RES-0805"))
    )
    (comp (ref "R25")
      (value "47K,1%")
      (footprint "eagle-import:R0805")
      (libsource (lib "eagle-import") (part "RES-0805"))
    )
    (comp (ref "R26")
      (value "0 Ohm")
      (footprint "eagle-import:R0805")
      (libsource (lib "eagle-import") (part "RES-0805"))
    )
    (comp (ref "R27")
      (value "10K,1%")
      (footprint "eagle-import:R0805")
      (libsource (lib "eagle-import") (part "RES-0805"))
    )
    (comp (ref "R28")
      (value "4.7K,1%")
      (footprint "eagle-import:R0805")
      (libsource (lib "eagle-import") (part "RES-0805"))
    )
    (comp (ref "R29")
      (value "4.7K,1%")
      (footprint "eagle-import:R0805")
      (libsource (lib "eagle-import") (part "RES-0805"))
    )
    (comp (ref "S1")
      (value "SGND")
      (footprint "eagle-import:SGND")
      (libsource (lib "eagle-import") (part "SGND"))
    )
    (comp (ref "S2")
      (value "SGND")
      (footprint "eagle-import:SGND")
      (libsource (lib "eagle-import") (part "SGND"))
    )
    (comp (ref "S3")
      (value "SGND")
      (footprint "eagle-import:SGND")
      (libsource (lib "eagle-import") (part "SGND"))
    )
    (comp (ref "S4")
      (value "SGND")
      (footprint "eagle-import:SGND")
      (libsource (lib "eagle-import") (part "SGND"))
    )
    (comp (ref "S5")
      (value "SGND")
      (footprint "eagle-import:SGND")
      (libsource (lib "eagle-import") (part "SGND"))
    )
    (comp (ref "S6")
      (value "SGND")
      (footprint "eagle-import:SGND")
      (libsource (lib "eagle-import") (part "SGND"))
    )
    (comp (ref "S7")
      (value "SGND")
      (footprint "eagle-import:SGND")
      (libsource (lib "eagle-import") (part "SGND"))
    )
    (comp (ref "SH1")
      (value "SHUNT,0.1IN")
      (footprint "eagle-import:NOPACKAGE")
      (libsource (lib "eagle-import") (part "SHUNT,0.1IN"))
    )
    (comp (ref "SW1")
      (value "TS-02B")
      (footprint "eagle-import:TS-02B")
      (libsource (lib "eagle-import") (part "TS-02B"))
    )
    (comp (ref "SW2")
      (value "SW-LC2259")
      (footprint "eagle-import:SW-LC2259")
      (libsource (lib "eagle-import") (part "SW-LC2259"))
    )
    (comp (ref "SW3")
      (value "TS-026")
      (footprint "eagle-import:TS-026")
      (libsource (lib "eagle-import") (part "TS-026"))
    )
    (comp (ref "SW4")
      (value "TS-026")
      (footprint "eagle-import:TS-026")
      (libsource (lib "eagle-import") (part "TS-026"))
    )
    (comp (ref "U1")
      (value "STM32F405VGT6")
      (footprint "eagle-import:LQFP100-14")
      (libsource (lib "eagle-import") (part "STM32F407"))
    )
    (comp (ref "U2")
      (value "STMPS2141")
      (footprint "eagle-import:SOT23-5L")
      (libsource (lib "eagle-import") (part "STMPS2141"))
    )
    (comp (ref "U3")
      (value "EMIF02-USB03F2")
      (footprint "eagle-import:ECOPACK-11")
      (libsource (lib "eagle-import") (part "EMIF02-USB03F2"))
    )
    (comp (ref "U4")
      (value "DNL")
      (footprint "eagle-import:SOIC8")
      (libsource (lib "eagle-import") (part "I2C-EEPROM-256K"))
    )
    (comp (ref "XTAL1")
      (value "8.000MHz")
      (footprint "eagle-import:CTS-405")
      (libsource (lib "eagle-import") (part "CTS-405"))
    )
    (comp (ref "C83")
      (value "2-12pF")
      (footprint "eagle-import:TRIMCAP_VAR_2222_V")
      (libsource (lib "eagle-import") (part "TRIMCAP_VAR_2222_V"))
    )
    (comp (ref "C111")
      (value "100nF,25V")
      (footprint "eagle-import:C0805")
      (libsource (lib "eagle-import") (part "CAP-0805"))
    )
    (comp (ref "C112")
      (value "39pF,50V")
      (footprint "eagle-import:C0805")
      (libsource (lib "eagle-import") (part "CAP-0805"))
    )
    (comp (ref "C113")
      (value "100nF,25V")
      (footprint "eagle-import:C0805")
      (libsource (lib "eagle-import") (part "CAP-0805"))
    )
    (comp (ref "C114")
      (value "100nF,25V")
      (footprint "eagle-import:C0805")
      (libsource (lib "eagle-import") (part "CAP-0805"))
    )
    (comp (ref "C115")
      (value "5.6pF,50V")
      (footprint "eagle-import:C0805")
      (libsource (lib "eagle-import") (part "CAP-0805"))
    )
    (comp (ref "C117")
      (value "100nF,25V")
      (footprint "eagle-import:C0805")
      (libsource (lib "eagle-import") (part "CAP-0805"))
    )
    (comp (ref "C118")
      (value "100nF,25V")
      (footprint "eagle-import:C0805")
      (libsource (lib "eagle-import") (part "CAP-0805"))
    )
    (comp (ref "C119")
      (value "100nF,25V")
      (footprint "eagle-import:C0805")
      (libsource (lib "eagle-import") (part "CAP-0805"))
    )
    (comp (ref "C120")
      (value "100nF,25V")
      (footprint "eagle-import:C0805")
      (libsource (lib "eagle-import") (part "CAP-0805"))
    )
    (comp (ref "C121")
      (value "100nF,25V")
      (footprint "eagle-import:C0805")
      (libsource (lib "eagle-import") (part "CAP-0805"))
    )
    (comp (ref "C122")
      (value "10uF,25V,EL")
      (footprint "eagle-import:NICHICON-WJ-5")
      (libsource (lib "eagle-import") (part "CAP-10UF-WJ5"))
    )
    (comp (ref "C123")
      (value "27pF,50V")
      (footprint "eagle-import:C0805")
      (libsource (lib "eagle-import") (part "CAP-0805"))
    )
    (comp (ref "C124")
      (value "150pF,50V")
      (footprint "eagle-import:C0805")
      (libsource (lib "eagle-import") (part "CAP-0805"))
    )
    (comp (ref "C125")
      (value "100nF,25V")
      (footprint "eagle-import:C0805")
      (libsource (lib "eagle-import") (part "CAP-0805"))
    )
    (comp (ref "C126")
      (value "10uF,25V,EL")
      (footprint "eagle-import:NICHICON-WJ-5")
      (libsource (lib "eagle-import") (part "CAP-10UF-WJ5"))
    )
    (comp (ref "C127")
      (value "100nF,25V")
      (footprint "eagle-import:C0805")
      (libsource (lib "eagle-import") (part "CAP-0805"))
    )
    (comp (ref "C128")
      (value "150pF,50V")
      (footprint "eagle-import:C0805")
      (libsource (lib "eagle-import") (part "CAP-0805"))
    )
    (comp (ref "C129")
      (value "10uF,25V,EL")
      (footprint "eagle-import:NICHICON-WJ-5")
      (libsource (lib "eagle-import") (part "CAP-10UF-WJ5"))
    )
    (comp (ref "C130")
      (value "10uF,25V,EL")
      (footprint "eagle-import:NICHICON-WJ-5")
      (libsource (lib "eagle-import") (part "CAP-10UF-WJ5"))
    )
    (comp (ref "C131")
      (value "1nF,25V")
      (footprint "eagle-import:C0805")
      (libsource (lib "eagle-import") (part "CAP-0805"))
    )
    (comp (ref "C132")
      (value "1nF,25V")
      (footprint "eagle-import:C0805")
      (libsource (lib "eagle-import") (part "CAP-0805"))
    )
    (comp (ref "C133")
      (value "100nF,25V")
      (footprint "eagle-import:C0805")
      (libsource (lib "eagle-import") (part "CAP-0805"))
    )
    (comp (ref "C134")
      (value "100nF,25V")
      (footprint "eagle-import:C0805")
      (libsource (lib "eagle-import") (part "CAP-0805"))
    )
    (comp (ref "C135")
      (value "1nF,25V")
      (footprint "eagle-import:C0805")
      (libsource (lib "eagle-import") (part "CAP-0805"))
    )
    (comp (ref "C136")
      (value "10uF,25V,EL")
      (footprint "eagle-import:NICHICON-WJ-5")
      (libsource (lib "eagle-import") (part "CAP-10UF-WJ5"))
    )
    (comp (ref "FB13")
      (value "FB0805")
      (footprint "eagle-import:FE0805")
      (libsource (lib "eagle-import") (part "FB0805"))
    )
    (comp (ref "FB14")
      (value "FB0805")
      (footprint "eagle-import:FE0805")
      (libsource (lib "eagle-import") (part "FB0805"))
    )
    (comp (ref "FB15")
      (value "FB0805")
      (footprint "eagle-import:FE0805")
      (libsource (lib "eagle-import") (part "FB0805"))
    )
    (comp (ref "FB16")
      (value "FB0805")
      (footprint "eagle-import:FE0805")
      (libsource (lib "eagle-import") (part "FB0805"))
    )
    (comp (ref "FB17")
      (value "FB0805")
      (footprint "eagle-import:FE0805")
      (libsource (lib "eagle-import") (part "FB0805"))
    )
    (comp (ref "FB18")
      (value "FB0805")
      (footprint "eagle-import:FE0805")
      (libsource (lib "eagle-import") (part "FB0805"))
    )
    (comp (ref "FB19")
      (value "FB0805")
      (footprint "eagle-import:FE0805")
      (libsource (lib "eagle-import") (part "FB0805"))
    )
    (comp (ref "J13")
      (value "JMPR-2X2")
      (footprint "eagle-import:JMPR-2X2X.1")
      (libsource (lib "eagle-import") (part "JMPR-2X2"))
    )
    (comp (ref "J14")
      (value "JMPR-2X2")
      (footprint "eagle-import:JMPR-2X2X.1")
      (libsource (lib "eagle-import") (part "JMPR-2X2"))
    )
    (comp (ref "L17")
      (value "5.7uH")
      (footprint "eagle-import:L-TDK-MLF2012")
      (libsource (lib "eagle-import") (part "L-TDK-MLF-2012"))
    )
    (comp (ref "L18")
      (value "L-TDK-MLF-2012-9.2uH")
      (footprint "eagle-import:L-TDK-MLF2012")
      (libsource (lib "eagle-import") (part "L-TDK-MLF-2012"))
    )
    (comp (ref "L19")
      (value "5.2uH")
      (footprint "eagle-import:L-TDK-MLF2012")
      (libsource (lib "eagle-import") (part "L-TDK-MLF-2012"))
    )
    (comp (ref "L20")
      (value "15uH,TDK,MLF")
      (footprint "eagle-import:L-TDK-MLF2012")
      (libsource (lib "eagle-import") (part "L-TDK-MLF-2012"))
    )
    (comp (ref "Q14")
      (value "MMBT3904")
      (footprint "eagle-import:SOT23")
      (libsource (lib "eagle-import") (part "MMBT3904"))
    )
    (comp (ref "Q15")
      (value "MMBT3904")
      (footprint "eagle-import:SOT23")
      (libsource (lib "eagle-import") (part "MMBT3904"))
    )
    (comp (ref "Q16")
      (value "MMBT3904")
      (footprint "eagle-import:SOT23")
      (libsource (lib "eagle-import") (part "MMBT3904"))
    )
    (comp (ref "Q17")
      (value "MMBT3906")
      (footprint "eagle-import:SOT23")
      (libsource (lib "eagle-import") (part "MMBT3906"))
    )
    (comp (ref "R96")
      (value "0 Ohm")
      (footprint "eagle-import:R0805")
      (libsource (lib "eagle-import") (part "RES-0805"))
    )
    (comp (ref "R97")
      (value "0 Ohm")
      (footprint "eagle-import:R0805")
      (libsource (lib "eagle-import") (part "RES-0805"))
    )
    (comp (ref "R98")
      (value "0 Ohm")
      (footprint "eagle-import:R0805")
      (libsource (lib "eagle-import") (part "RES-0805"))
    )
    (comp (ref "R99")
      (value "1K,1%")
      (footprint "eagle-import:R0805")
      (libsource (lib "eagle-import") (part "RES-0805"))
    )
    (comp (ref "R100")
      (value "1K,1%")
      (footprint "eagle-import:R0805")
      (libsource (lib "eagle-import") (part "RES-0805"))
    )
    (comp (ref "R101")
      (value "150,1%")
      (footprint "eagle-import:R0805")
      (libsource (lib "eagle-import") (part "RES-0805"))
    )
    (comp (ref "R102")
      (value "150,1%")
      (footprint "eagle-import:R0805")
      (libsource (lib "eagle-import") (part "RES-0805"))
    )
    (comp (ref "R103")
      (value "33K,1%")
      (footprint "eagle-import:R0805")
      (libsource (lib "eagle-import") (part "RES-0805"))
    )
    (comp (ref "R104")
      (value "15K,1%")
      (footprint "eagle-import:R0805")
      (libsource (lib "eagle-import") (part "RES-0805"))
    )
    (comp (ref "R105")
      (value "3K,1%")
      (footprint "eagle-import:R0805")
      (libsource (lib "eagle-import") (part "RES-0805"))
    )
    (comp (ref "R106")
      (value "1K,1%")
      (footprint "eagle-import:R0805")
      (libsource (lib "eagle-import") (part "RES-0805"))
    )
    (comp (ref "R107")
      (value "1K,1%")
      (footprint "eagle-import:R0805")
      (libsource (lib "eagle-import") (part "RES-0805"))
    )
    (comp (ref "R108")
      (value "10,1%")
      (footprint "eagle-import:R0805")
      (libsource (lib "eagle-import") (part "RES-0805"))
    )
    (comp (ref "R109")
      (value "49.9,1%")
      (footprint "eagle-import:R0805")
      (libsource (lib "eagle-import") (part "RES-0805"))
    )
    (comp (ref "R110")
      (value "39K,1%")
      (footprint "eagle-import:R0805")
      (libsource (lib "eagle-import") (part "RES-0805"))
    )
    (comp (ref "R111")
      (value "18K,1%")
      (footprint "eagle-import:R0805")
      (libsource (lib "eagle-import") (part "RES-0805"))
    )
    (comp (ref "R112")
      (value "2.2K,1%")
      (footprint "eagle-import:R0805")
      (libsource (lib "eagle-import") (part "RES-0805"))
    )
    (comp (ref "R113")
      (value "1K,1%")
      (footprint "eagle-import:R0805")
      (libsource (lib "eagle-import") (part "RES-0805"))
    )
    (comp (ref "R114")
      (value "100,1%")
      (footprint "eagle-import:R0805")
      (libsource (lib "eagle-import") (part "RES-0805"))
    )
    (comp (ref "R115")
      (value "10,1%")
      (footprint "eagle-import:R0805")
      (libsource (lib "eagle-import") (part "RES-0805"))
    )
    (comp (ref "R116")
      (value "150,1%")
      (footprint "eagle-import:R0805")
      (libsource (lib "eagle-import") (part "RES-0805"))
    )
    (comp (ref "R117")
      (value "3.3K,1%")
      (footprint "eagle-import:R0805")
      (libsource (lib "eagle-import") (part "RES-0805"))
    )
    (comp (ref "R118")
      (value "3.3K,1%")
      (footprint "eagle-import:R0805")
      (libsource (lib "eagle-import") (part "RES-0805"))
    )
    (comp (ref "R119")
      (value "100,1%")
      (footprint "eagle-import:R0805")
      (libsource (lib "eagle-import") (part "RES-0805"))
    )
    (comp (ref "R120")
      (value "10,1%")
      (footprint "eagle-import:R0805")
      (libsource (lib "eagle-import") (part "RES-0805"))
    )
    (comp (ref "SP1")
      (value "SCOPE_PAD")
      (footprint "eagle-import:SCOPE_PAD")
      (libsource (lib "eagle-import") (part "SCOPE_PAD"))
    )
    (comp (ref "SP3")
      (value "SCOPE_PAD")
      (footprint "eagle-import:SCOPE_PAD")
      (libsource (lib "eagle-import") (part "SCOPE_PAD"))
    )
    (comp (ref "SP6")
      (value "SCOPE_PAD")
      (footprint "eagle-import:SCOPE_PAD")
      (libsource (lib "eagle-import") (part "SCOPE_PAD"))
    )
    (comp (ref "SP7")
      (value "SCOPE_PAD")
      (footprint "eagle-import:SCOPE_PAD")
      (libsource (lib "eagle-import") (part "SCOPE_PAD"))
    )
    (comp (ref "SP8")
      (value "SCOPE_PAD")
      (footprint "eagle-import:SCOPE_PAD")
      (libsource (lib "eagle-import") (part "SCOPE_PAD"))
    )
    (comp (ref "U14")
      (value "SI5351A")
      (footprint "eagle-import:MSOP10")
      (libsource (lib "eagle-import") (part "SI5351A"))
    )
    (comp (ref "U15")
      (value "SI570")
      (footprint "eagle-import:SI570")
      (libsource (lib "eagle-import") (part "SI570"))
    )
    (comp (ref "U16")
      (value "SA612A")
      (footprint "eagle-import:SO-08")
      (libsource (lib "eagle-import") (part "SA612A"))
    )
    (comp (ref "XTAL2")
      (value "25.000MHz")
      (footprint "eagle-import:CTS-405")
      (libsource (lib "eagle-import") (part "CTS-405"))
    )
    (comp (ref "XTAL3")
      (value "ECS-10.7-15B")
      (footprint "eagle-import:HC49U")
      (libsource (lib "eagle-import") (part "ECS-10.7-15BECS-10.7-12A"))
    )
    (comp (ref "XTAL4")
      (value "ECS-10.7-15B")
      (footprint "eagle-import:HC49U")
      (libsource (lib "eagle-import") (part "ECS-10.7-15BECS-10.7-12A"))
    )
    (comp (ref "C23")
      (value ".33uF,25V")
      (footprint "eagle-import:C0805")
      (libsource (lib "eagle-import") (part "CAP-0805"))
    )
    (comp (ref "C24")
      (value "100nF,25V")
      (footprint "eagle-import:C0805")
      (libsource (lib "eagle-import") (part "CAP-0805"))
    )
    (comp (ref "C25")
      (value "10nF,25V")
      (footprint "eagle-import:C0805")
      (libsource (lib "eagle-import") (part "CAP-0805"))
    )
    (comp (ref "C26")
      (value "22uF,25V")
      (footprint "eagle-import:C1210")
      (libsource (lib "eagle-import") (part "CAP-1210"))
    )
    (comp (ref "C27")
      (value "1nF,25V")
      (footprint "eagle-import:C0805")
      (libsource (lib "eagle-import") (part "CAP-0805"))
    )
    (comp (ref "C28")
      (value "220nF,25V")
      (footprint "eagle-import:C0805")
      (libsource (lib "eagle-import") (part "CAP-0805"))
    )
    (comp (ref "C29")
      (value "22uF,25V")
      (footprint "eagle-import:C1210")
      (libsource (lib "eagle-import") (part "CAP-1210"))
    )
    (comp (ref "C30")
      (value "100nF,25V")
      (footprint "eagle-import:C0805")
      (libsource (lib "eagle-import") (part "CAP-0805"))
    )
    (comp (ref "C31")
      (value "100uF,6.3V,EL")
      (footprint "eagle-import:NICHICON-WX-6.3")
      (libsource (lib "eagle-import") (part "NICHICON-WX-6.3"))
    )
    (comp (ref "C32")
      (value "100uF,6.3V,EL")
      (footprint "eagle-import:NICHICON-WX-6.3")
      (libsource (lib "eagle-import") (part "NICHICON-WX-6.3"))
    )
    (comp (ref "C33")
      (value "100nF,25V")
      (footprint "eagle-import:C0805")
      (libsource (lib "eagle-import") (part "CAP-0805"))
    )
    (comp (ref "C34")
      (value "220uF,25V")
      (footprint "eagle-import:CAP-CHEMI-HA0")
      (libsource (lib "eagle-import") (part "CAP-CHEMI-MVE-HA0"))
    )
    (comp (ref "C35")
      (value "100nF,25V")
      (footprint "eagle-import:C0805")
      (libsource (lib "eagle-import") (part "CAP-0805"))
    )
    (comp (ref "C36")
      (value "22uF,25V")
      (footprint "eagle-import:C1210")
      (libsource (lib "eagle-import") (part "CAP-1210"))
    )
    (comp (ref "C37")
      (value "100nF,25V")
      (footprint "eagle-import:C0805")
      (libsource (lib "eagle-import") (part "CAP-0805"))
    )
    (comp (ref "C38")
      (value "2.2uF,25V")
      (footprint "eagle-import:C0805")
      (libsource (lib "eagle-import") (part "CAP-0805"))
    )
    (comp (ref "C39")
      (value "100pF,50V")
      (footprint "eagle-import:C0805")
      (libsource (lib "eagle-import") (part "CAP-0805"))
    )
    (comp (ref "C40")
      (value "1nF,25V")
      (footprint "eagle-import:C0805")
      (libsource (lib "eagle-import") (part "CAP-0805"))
    )
    (comp (ref "C41")
      (value "100nF,25V")
      (footprint "eagle-import:C0805")
      (libsource (lib "eagle-import") (part "CAP-0805"))
    )
    (comp (ref "C42")
      (value "22uF,25V")
      (footprint "eagle-import:C1210")
      (libsource (lib "eagle-import") (part "CAP-1210"))
    )
    (comp (ref "C43")
      (value "22uF,25V")
      (footprint "eagle-import:C1210")
      (libsource (lib "eagle-import") (part "CAP-1210"))
    )
    (comp (ref "C44")
      (value "22uF,25V")
      (footprint "eagle-import:C1210")
      (libsource (lib "eagle-import") (part "CAP-1210"))
    )
    (comp (ref "C45")
      (value "100nF,25V")
      (footprint "eagle-import:C0805")
      (libsource (lib "eagle-import") (part "CAP-0805"))
    )
    (comp (ref "C46")
      (value "470nF,25V")
      (footprint "eagle-import:C0805")
      (libsource (lib "eagle-import") (part "CAP-0805"))
    )
    (comp (ref "C47")
      (value "8.2nF,25V")
      (footprint "eagle-import:C0805")
      (libsource (lib "eagle-import") (part "CAP-0805"))
    )
    (comp (ref "C48")
      (value "100nF,25V")
      (footprint "eagle-import:C0805")
      (libsource (lib "eagle-import") (part "CAP-0805"))
    )
    (comp (ref "C49")
      (value "100nF,25V")
      (footprint "eagle-import:C0805")
      (libsource (lib "eagle-import") (part "CAP-0805"))
    )
    (comp (ref "C50")
      (value "3.9nF,25V")
      (footprint "eagle-import:C0805")
      (libsource (lib "eagle-import") (part "CAP-0805"))
    )
    (comp (ref "C51")
      (value "20pF,50V")
      (footprint "eagle-import:C0805")
      (libsource (lib "eagle-import") (part "CAP-0805"))
    )
    (comp (ref "C52")
      (value "220uF,25V")
      (footprint "eagle-import:CAP-CHEMI-HA0")
      (libsource (lib "eagle-import") (part "CAP-CHEMI-MVE-HA0"))
    )
    (comp (ref "C53")
      (value "47nF,25V")
      (footprint "eagle-import:C0805")
      (libsource (lib "eagle-import") (part "CAP-0805"))
    )
    (comp (ref "C54")
      (value "22uF,25V")
      (footprint "eagle-import:C1210")
      (libsource (lib "eagle-import") (part "CAP-1210"))
    )
    (comp (ref "C55")
      (value "220uF,25V")
      (footprint "eagle-import:CAP-CHEMI-HA0")
      (libsource (lib "eagle-import") (part "CAP-CHEMI-MVE-HA0"))
    )
    (comp (ref "C56")
      (value "100nF,25V")
      (footprint "eagle-import:C0805")
      (libsource (lib "eagle-import") (part "CAP-0805"))
    )
    (comp (ref "C137")
      (value "100nF,25V")
      (footprint "eagle-import:C0805")
      (libsource (lib "eagle-import") (part "CAP-0805"))
    )
    (comp (ref "C138")
      (value "100nF,25V")
      (footprint "eagle-import:C0805")
      (libsource (lib "eagle-import") (part "CAP-0805"))
    )
    (comp (ref "CN5")
      (value "DS-0518")
      (footprint "eagle-import:DS-0518")
      (libsource (lib "eagle-import") (part "DS-0518"))
    )
    (comp (ref "CN6")
      (value "ST-3509")
      (footprint "eagle-import:ST-3509")
      (libsource (lib "eagle-import") (part "ST-3509"))
    )
    (comp (ref "CN7")
      (value "ST-3509")
      (footprint "eagle-import:ST-3509")
      (libsource (lib "eagle-import") (part "ST-3509"))
    )
    (comp (ref "D2")
      (value "DNL")
      (footprint "eagle-import:SOD523")
      (libsource (lib "eagle-import") (part "PESD5ZX"))
    )
    (comp (ref "D3")
      (value "PTVS20VP1UP")
      (footprint "eagle-import:SOD128")
      (libsource (lib "eagle-import") (part "PTVS20VP1UP"))
    )
    (comp (ref "D4")
      (value "B330B")
      (footprint "eagle-import:SMB")
      (libsource (lib "eagle-import") (part "B330B"))
    )
    (comp (ref "D5")
      (value "DNL")
      (footprint "eagle-import:SOD128")
      (libsource (lib "eagle-import") (part "PTVS20VP1UP"))
    )
    (comp (ref "FB2")
      (value "FB0805")
      (footprint "eagle-import:FE0805")
      (libsource (lib "eagle-import") (part "FB0805"))
    )
    (comp (ref "FB3")
      (value "FB0805")
      (footprint "eagle-import:FE0805")
      (libsource (lib "eagle-import") (part "FB0805"))
    )
    (comp (ref "FB4")
      (value "FB0805")
      (footprint "eagle-import:FE0805")
      (libsource (lib "eagle-import") (part "FB0805"))
    )
    (comp (ref "FB5")
      (value "FB0805")
      (footprint "eagle-import:FE0805")
      (libsource (lib "eagle-import") (part "FB0805"))
    )
    (comp (ref "FB20")
      (value "FB0805")
      (footprint "eagle-import:FE0805")
      (libsource (lib "eagle-import") (part "FB0805"))
    )
    (comp (ref "J3")
      (value "JMP-2PIN")
      (footprint "eagle-import:JMPR-2PIN")
      (libsource (lib "eagle-import") (part "JMP-2PIN"))
    )
    (comp (ref "J4")
      (value "CONN-BOOM-XH-2A")
      (footprint "eagle-import:CONN-BOOM-XH-2A")
      (libsource (lib "eagle-import") (part "CONN-BOOM-XH-2A"))
    )
    (comp (ref "J5")
      (value "JMP-2PIN")
      (footprint "eagle-import:JMPR-2PIN")
      (libsource (lib "eagle-import") (part "JMP-2PIN"))
    )
    (comp (ref "L1")
      (value "4.2uH")
      (footprint "eagle-import:SRR5028")
      (libsource (lib "eagle-import") (part "SRR5028"))
    )
    (comp (ref "LED5")
      (value "SML-LX0603GW")
      (footprint "eagle-import:SML-LX0603SRW")
      (libsource (lib "eagle-import") (part "SML-LX0603SRW"))
    )
    (comp (ref "LED6")
      (value "SML-LX0603GW")
      (footprint "eagle-import:SML-LX0603SRW")
      (libsource (lib "eagle-import") (part "SML-LX0603SRW"))
    )
    (comp (ref "LED7")
      (value "LTST-S220KGKT")
      (footprint "eagle-import:LTST-S2200K")
      (libsource (lib "eagle-import") (part "LTST-S220K"))
    )
    (comp (ref "LED8")
      (value "SML-LX0603GW")
      (footprint "eagle-import:SML-LX0603SRW")
      (libsource (lib "eagle-import") (part "SML-LX0603SRW"))
    )
    (comp (ref "LED9")
      (value "SML-LX0603SRW")
      (footprint "eagle-import:SML-LX0603SRW")
      (libsource (lib "eagle-import") (part "SML-LX0603SRW"))
    )
    (comp (ref "LED10")
      (value "SML-LX0603GW")
      (footprint "eagle-import:SML-LX0603SRW")
      (libsource (lib "eagle-import") (part "SML-LX0603SRW"))
    )
    (comp (ref "LED11")
      (value "SML-LX0603YW")
      (footprint "eagle-import:SML-LX0603SRW")
      (libsource (lib "eagle-import") (part "SML-LX0603SRW"))
    )
    (comp (ref "MIC1")
      (value "CMA-4544PF-W")
      (footprint "eagle-import:CMA-4544PF-W")
      (libsource (lib "eagle-import") (part "CMA-4544PF-W"))
    )
    (comp (ref "Q1")
      (value "MMBT3904")
      (footprint "eagle-import:SOT23")
      (libsource (lib "eagle-import") (part "MMBT3904"))
    )
    (comp (ref "Q2")
      (value "STR2P3LLH6")
      (footprint "eagle-import:SOT23")
      (libsource (lib "eagle-import") (part "STR2P3LLH6"))
    )
    (comp (ref "Q3")
      (value "MMBT3904")
      (footprint "eagle-import:SOT23")
      (libsource (lib "eagle-import") (part "MMBT3904"))
    )
    (comp (ref "Q4")
      (value "STR2P3LLH6")
      (footprint "eagle-import:SOT23")
      (libsource (lib "eagle-import") (part "STR2P3LLH6"))
    )
    (comp (ref "R30")
      (value "1.5K,1%")
      (footprint "eagle-import:R0805")
      (libsource (lib "eagle-import") (part "RES-0805"))
    )
    (comp (ref "R31")
      (value "100,1%")
      (footprint "eagle-import:R0805")
      (libsource (lib "eagle-import") (part "RES-0805"))
    )
    (comp (ref "R32")
      (value "100,1%")
      (footprint "eagle-import:R0805")
      (libsource (lib "eagle-import") (part "RES-0805"))
    )
    (comp (ref "R33")
      (value "2.2K,1%")
      (footprint "eagle-import:R0805")
      (libsource (lib "eagle-import") (part "RES-0805"))
    )
    (comp (ref "R34")
      (value "330,1%")
      (footprint "eagle-import:R0805")
      (libsource (lib "eagle-import") (part "RES-0805"))
    )
    (comp (ref "R35")
      (value "2.2K,1%")
      (footprint "eagle-import:R0805")
      (libsource (lib "eagle-import") (part "RES-0805"))
    )
    (comp (ref "R36")
      (value "2.2K,1%")
      (footprint "eagle-import:R0805")
      (libsource (lib "eagle-import") (part "RES-0805"))
    )
    (comp (ref "R37")
      (value "2.2K,1%")
      (footprint "eagle-import:R0805")
      (libsource (lib "eagle-import") (part "RES-0805"))
    )
    (comp (ref "R38")
      (value "2.2K,1%")
      (footprint "eagle-import:R0805")
      (libsource (lib "eagle-import") (part "RES-0805"))
    )
    (comp (ref "R39")
      (value "500K,TrimPOT")
      (footprint "eagle-import:POT3361")
      (libsource (lib "eagle-import") (part "POT3361"))
    )
    (comp (ref "R40")
      (value "330,1%")
      (footprint "eagle-import:R0805")
      (libsource (lib "eagle-import") (part "RES-0805"))
    )
    (comp (ref "R41")
      (value "0 Ohm")
      (footprint "eagle-import:R0805")
      (libsource (lib "eagle-import") (part "RES-0805"))
    )
    (comp (ref "R42")
      (value "1.5K,1%")
      (footprint "eagle-import:R0805")
      (libsource (lib "eagle-import") (part "RES-0805"))
    )
    (comp (ref "R43")
      (value "10K,1%")
      (footprint "eagle-import:R0805")
      (libsource (lib "eagle-import") (part "RES-0805"))
    )
    (comp (ref "R44")
      (value "330,1%")
      (footprint "eagle-import:R0805")
      (libsource (lib "eagle-import") (part "RES-0805"))
    )
    (comp (ref "R45")
      (value "22.1K,1%")
      (footprint "eagle-import:R0805")
      (libsource (lib "eagle-import") (part "RES-0805"))
    )
    (comp (ref "R46")
      (value "10K,1%")
      (footprint "eagle-import:R0805")
      (libsource (lib "eagle-import") (part "RES-0805"))
    )
    (comp (ref "R47")
      (value "2.2K,1%")
      (footprint "eagle-import:R0805")
      (libsource (lib "eagle-import") (part "RES-0805"))
    )
    (comp (ref "R48")
      (value "100K,POT")
      (footprint "eagle-import:POT-3310C")
      (libsource (lib "eagle-import") (part "POT-3310C"))
    )
    (comp (ref "R49")
      (value "4.7,0.5W,1206")
      (footprint "eagle-import:R1206")
      (libsource (lib "eagle-import") (part "RES-1206"))
    )
    (comp (ref "R50")
      (value "1K,1%")
      (footprint "eagle-import:R0805")
      (libsource (lib "eagle-import") (part "RES-0805"))
    )
    (comp (ref "R51")
      (value "124.0K,1%")
      (footprint "eagle-import:R0805")
      (libsource (lib "eagle-import") (part "RES-0805"))
    )
    (comp (ref "R52")
      (value "22.1K,1%")
      (footprint "eagle-import:R0805")
      (libsource (lib "eagle-import") (part "RES-0805"))
    )
    (comp (ref "R53")
      (value "10,1%")
      (footprint "eagle-import:R0805")
      (libsource (lib "eagle-import") (part "RES-0805"))
    )
    (comp (ref "R54")
      (value "10K,1%")
      (footprint "eagle-import:R0805")
      (libsource (lib "eagle-import") (part "RES-0805"))
    )
    (comp (ref "R55")
      (value "680,1%")
      (footprint "eagle-import:R0805")
      (libsource (lib "eagle-import") (part "RES-0805"))
    )
    (comp (ref "R56")
      (value "2.2K,1%")
      (footprint "eagle-import:R0805")
      (libsource (lib "eagle-import") (part "RES-0805"))
    )
    (comp (ref "R57")
      (value "1K,1%")
      (footprint "eagle-import:R0805")
      (libsource (lib "eagle-import") (part "RES-0805"))
    )
    (comp (ref "SH2")
      (value "SHUNT,0.1IN")
      (footprint "eagle-import:NOPACKAGE")
      (libsource (lib "eagle-import") (part "SHUNT,0.1IN"))
    )
    (comp (ref "SH3")
      (value "SHUNT,0.1IN")
      (footprint "eagle-import:NOPACKAGE")
      (libsource (lib "eagle-import") (part "SHUNT,0.1IN"))
    )
    (comp (ref "SP2")
      (value "SCOPE_PAD")
      (footprint "eagle-import:SCOPE_PAD")
      (libsource (lib "eagle-import") (part "SCOPE_PAD"))
    )
    (comp (ref "SP4")
      (value "SCOPE_PAD")
      (footprint "eagle-import:SCOPE_PAD")
      (libsource (lib "eagle-import") (part "SCOPE_PAD"))
    )
    (comp (ref "SP9")
      (value "SCOPE_PAD")
      (footprint "eagle-import:SCOPE_PAD")
      (libsource (lib "eagle-import") (part "SCOPE_PAD"))
    )
    (comp (ref "SW5")
      (value "SW-LC2259EENP")
      (footprint "eagle-import:SW-LC2259")
      (libsource (lib "eagle-import") (part "SW-LC2259"))
    )
    (comp (ref "U5")
      (value "L78M09")
      (footprint "eagle-import:DPAK")
      (libsource (lib "eagle-import") (part "L78MXX"))
    )
    (comp (ref "U6")
      (value "LD1117AS-33")
      (footprint "eagle-import:SOT223")
      (libsource (lib "eagle-import") (part "LD1117AS33"))
    )
    (comp (ref "U7")
      (value "LMV341")
      (footprint "eagle-import:SOT23-6")
      (libsource (lib "eagle-import") (part "LMV341"))
    )
    (comp (ref "U8")
      (value "LD1117AS-33")
      (footprint "eagle-import:SOT223")
      (libsource (lib "eagle-import") (part "LD1117AS33"))
    )
    (comp (ref "U9")
      (value "TPS54329E")
      (footprint "eagle-import:PSO-DDA")
      (libsource (lib "eagle-import") (part "TPS54329E"))
    )
    (comp (ref "U10")
      (value "LM386M-1")
      (footprint "eagle-import:SO08")
      (libsource (lib "eagle-import") (part "LM386?-M1"))
    )
  )
  (nets
    (net (code "1") (name "+5V") (class "Default")
      (node (ref "C51") (pin "1") (pinfunction "1_1") (pintype "passive"))
      (node (ref "C54") (pin "1") (pinfunction "1_1") (pintype "passive"))
      (node (ref "FB16") (pin "2") (pinfunction "2_2") (pintype "passive"))
      (node (ref "FB17") (pin "1") (pinfunction "1_1") (pintype "passive"))
      (node (ref "FB19") (pin "2") (pinfunction "2_2") (pintype "passive"))
      (node (ref "FB20") (pin "1") (pinfunction "1_1") (pintype "passive"))
      (node (ref "FB4") (pin "1") (pinfunction "1_1") (pintype "passive"))
      (node (ref "L1") (pin "2") (pinfunction "2_2") (pintype "passive"))
      (node (ref "R51") (pin "1") (pinfunction "1_1") (pintype "passive"))
      (node (ref "R55") (pin "2") (pinfunction "2_2") (pintype "passive"))
      (node (ref "U2") (pin "5") (pinfunction "IN_5") (pintype "bidirectional"))
    )
    (net (code "2") (name "+9V") (class "Default")
      (node (ref "C108") (pin "1") (pinfunction "1_1") (pintype "passive"))
      (node (ref "C109") (pin "1") (pinfunction "1_1") (pintype "passive"))
      (node (ref "C24") (pin "1") (pinfunction "1_1") (pintype "passive"))
      (node (ref "L15") (pin "2") (pinfunction "2_2") (pintype "passive"))
      (node (ref "R30") (pin "2") (pinfunction "2_2") (pintype "passive"))
      (node (ref "U5") (pin "3") (pinfunction "OUT_3") (pintype "bidirectional"))
    )
    (net (code "3") (name "+12VRXENB") (class "Default")
      (node (ref "J2") (pin "7") (pinfunction "7_7") (pintype "bidirectional"))
      (node (ref "R46") (pin "1") (pinfunction "1_1") (pintype "passive"))
      (node (ref "U1") (pin "4") (pinfunction "PE5_4") (pintype "bidirectional"))
    )
    (net (code "4") (name "+12VTXENB") (class "Default")
      (node (ref "J2") (pin "6") (pinfunction "6_6") (pintype "bidirectional"))
      (node (ref "R54") (pin "1") (pinfunction "1_1") (pintype "passive"))
      (node (ref "U1") (pin "3") (pinfunction "PE4_3") (pintype "bidirectional"))
    )
    (net (code "5") (name "+VIN") (class "Default")
      (node (ref "C23") (pin "1") (pinfunction "1_1") (pintype "passive"))
      (node (ref "C34") (pin "1") (pinfunction "1_1") (pintype "passive"))
      (node (ref "C40") (pin "1") (pinfunction "1_1") (pintype "passive"))
      (node (ref "C41") (pin "1") (pinfunction "1_1") (pintype "passive"))
      (node (ref "C42") (pin "1") (pinfunction "1_1") (pintype "passive"))
      (node (ref "C43") (pin "1") (pinfunction "1_1") (pintype "passive"))
      (node (ref "C56") (pin "1") (pinfunction "1_1") (pintype "passive"))
      (node (ref "Q2") (pin "2") (pinfunction "S_2") (pintype "bidirectional"))
      (node (ref "Q4") (pin "2") (pinfunction "S_2") (pintype "bidirectional"))
      (node (ref "R40") (pin "2") (pinfunction "2_2") (pintype "passive"))
      (node (ref "R41") (pin "2") (pinfunction "2_2") (pintype "passive"))
      (node (ref "R43") (pin "1") (pinfunction "1_1") (pintype "passive"))
      (node (ref "R47") (pin "2") (pinfunction "2_2") (pintype "passive"))
      (node (ref "R49") (pin "1") (pinfunction "1_1") (pintype "passive"))
      (node (ref "R56") (pin "2") (pinfunction "2_2") (pintype "passive"))
      (node (ref "U5") (pin "1") (pinfunction "IN_1") (pintype "bidirectional"))
      (node (ref "U9") (pin "2") (pinfunction "VIN_2") (pintype "bidirectional"))
    )
    (net (code "6") (name "1ST_LO") (class "Default")
      (node (ref "R96") (pin "1") (pinfunction "1_1") (pintype "passive"))
      (node (ref "R97") (pin "1") (pinfunction "1_1") (pintype "passive"))
      (node (ref "R98") (pin "1") (pinfunction "1_1") (pintype "passive"))
      (node (ref "SP6") (pin "1") (pinfunction "1_1") (pintype "bidirectional"))
      (node (ref "U11") (pin "1") (pinfunction "G1_1") (pintype "bidirectional"))
    )
    (net (code "7") (name "3V3") (class "Default")
      (node (ref "C1") (pin "1") (pinfunction "1_1") (pintype "passive"))
      (node (ref "C14") (pin "1") (pinfunction "1_1") (pintype "passive"))
      (node (ref "C15") (pin "1") (pinfunction "1_1") (pintype "passive"))
      (node (ref "C2") (pin "1") (pinfunction "1_1") (pintype "passive"))
      (node (ref "C29") (pin "1") (pinfunction "1_1") (pintype "passive"))
      (node (ref "C3") (pin "1") (pinfunction "1_1") (pintype "passive"))
      (node (ref "C37") (pin "1") (pinfunction "1_1") (pintype "passive"))
      (node (ref "C5") (pin "1") (pinfunction "1_1") (pintype "passive"))
      (node (ref "C8") (pin "1") (pinfunction "1_1") (pintype "passive"))
      (node (ref "C9") (pin "1") (pinfunction "1_1") (pintype "passive"))
      (node (ref "FB13") (pin "1") (pinfunction "1_1") (pintype "passive"))
      (node (ref "FB14") (pin "1") (pinfunction "1_1") (pintype "passive"))
      (node (ref "FB15") (pin "1") (pinfunction "1_1") (pintype "passive"))
      (node (ref "R10") (pin "1") (pinfunction "1_1") (pintype "passive"))
      (node (ref "R14") (pin "1") (pinfunction "1_1") (pintype "passive"))
      (node (ref "R18") (pin "2") (pinfunction "2_2") (pintype "passive"))
      (node (ref "R20") (pin "1") (pinfunction "1_1") (pintype "passive"))
      (node (ref "R22") (pin "2") (pinfunction "2_2") (pintype "passive"))
      (node (ref "R25") (pin "1") (pinfunction "1_1") (pintype "passive"))
      (node (ref "R27") (pin "2") (pinfunction "2_2") (pintype "passive"))
      (node (ref "R28") (pin "1") (pinfunction "1_1") (pintype "passive"))
      (node (ref "R29") (pin "1") (pinfunction "1_1") (pintype "passive"))
      (node (ref "R34") (pin "2") (pinfunction "2_2") (pintype "passive"))
      (node (ref "R7") (pin "1") (pinfunction "1_1") (pintype "passive"))
      (node (ref "R8") (pin "1") (pinfunction "1_1") (pintype "passive"))
      (node (ref "R9") (pin "1") (pinfunction "1_1") (pintype "passive"))
      (node (ref "SW2") (pin "2") (pinfunction "2_2") (pintype "passive"))
      (node (ref "SW2") (pin "5") (pinfunction "5_5") (pintype "passive"))
      (node (ref "U1") (pin "100") (pinfunction "VDD3_100") (pintype "bidirectional"))
      (node (ref "U1") (pin "11") (pinfunction "VDD5_11") (pintype "bidirectional"))
      (node (ref "U1") (pin "19") (pinfunction "VDD12_19") (pintype "bidirectional"))
      (node (ref "U1") (pin "28") (pinfunction "VDD4_28") (pintype "bidirectional"))
      (node (ref "U1") (pin "50") (pinfunction "VDD1_50") (pintype "bidirectional"))
      (node (ref "U1") (pin "75") (pinfunction "VDD2_75") (pintype "bidirectional"))
      (node (ref "U4") (pin "8") (pinfunction "VCC_8") (pintype "bidirectional"))
      (node (ref "U6") (pin "2") (pinfunction "OUT_2") (pintype "bidirectional"))
      (node (ref "U6") (pin "4") (pinfunction "OUT_4") (pintype "bidirectional"))
    )
    (net (code "8") (name "A3V3") (class "Default")
      (node (ref "C35") (pin "1") (pinfunction "1_1") (pintype "passive"))
      (node (ref "C38") (pin "1") (pinfunction "1_1") (pintype "passive"))
      (node (ref "C44") (pin "1") (pinfunction "1_1") (pintype "passive"))
      (node (ref "C45") (pin "1") (pinfunction "1_1") (pintype "passive"))
      (node (ref "FB1") (pin "1") (pinfunction "1_1") (pintype "passive"))
      (node (ref "FB9") (pin "2") (pinfunction "2_2") (pintype "passive"))
      (node (ref "J3") (pin "2") (pinfunction "2_2") (pintype "bidirectional"))
      (node (ref "R38") (pin "2") (pinfunction "2_2") (pintype "passive"))
      (node (ref "R44") (pin "2") (pinfunction "2_2") (pintype "passive"))
      (node (ref "U13") (pin "5") (pinfunction "~{SHDN}_5") (pintype "bidirectional"))
      (node (ref "U13") (pin "6") (pinfunction "V+_6") (pintype "bidirectional"))
      (node (ref "U7") (pin "5") (pinfunction "~{SHDN}_5") (pintype "bidirectional"))
      (node (ref "U7") (pin "6") (pinfunction "V+_6") (pintype "bidirectional"))
      (node (ref "U8") (pin "2") (pinfunction "OUT_2") (pintype "bidirectional"))
      (node (ref "U8") (pin "4") (pinfunction "OUT_4") (pintype "bidirectional"))
    )
    (net (code "9") (name "AIN1") (class "Default")
      (node (ref "C13") (pin "1") (pinfunction "1_1") (pintype "passive"))
      (node (ref "Q17") (pin "3") (pinfunction "C_3") (pintype "passive"))
      (node (ref "R118") (pin "2") (pinfunction "2_2") (pintype "passive"))
      (node (ref "SP1") (pin "1") (pinfunction "1_1") (pintype "bidirectional"))
      (node (ref "U1") (pin "24") (pinfunction "PA1_24") (pintype "bidirectional"))
    )
    (net (code "10") (name "AIN2") (class "Default")
      (node (ref "C10") (pin "1") (pinfunction "1_1") (pintype "passive"))
      (node (ref "R42") (pin "1") (pinfunction "1_1") (pintype "passive"))
      (node (ref "SP2") (pin "1") (pinfunction "1_1") (pintype "bidirectional"))
      (node (ref "U1") (pin "25") (pinfunction "PA2_25") (pintype "bidirectional"))
    )
    (net (code "11") (name "AIN3") (class "Default")
      (node (ref "C97") (pin "2") (pinfunction "2_2") (pintype "passive"))
      (node (ref "D10") (pin "1") (pinfunction "K_1") (pintype "passive"))
      (node (ref "U1") (pin "26") (pinfunction "PA3_26") (pintype "bidirectional"))
    )
    (net (code "12") (name "ANT_SMA") (class "Default")
      (node (ref "C100") (pin "1") (pinfunction "1_1") (pintype "passive"))
      (node (ref "C101") (pin "2") (pinfunction "2_2") (pintype "passive"))
      (node (ref "R94") (pin "2") (pinfunction "2_2") (pintype "passive"))
      (node (ref "X1") (pin "1") (pinfunction "1_1") (pintype "passive"))
    )
    (net (code "13") (name "BBAMP") (class "Default")
      (node (ref "C135") (pin "2") (pinfunction "2_2") (pintype "passive"))
      (node (ref "J14") (pin "1") (pinfunction "1_1") (pintype "bidirectional"))
      (node (ref "L20") (pin "P$2") (pinfunction "2_P$2") (pintype "passive"))
    )
    (net (code "14") (name "BOOT1") (class "Default")
      (node (ref "R11") (pin "2") (pinfunction "2_2") (pintype "passive"))
      (node (ref "U1") (pin "37") (pinfunction "PB2_37") (pintype "bidirectional"))
    )
    (net (code "15") (name "DAC2_OUT") (class "Default")
      (node (ref "C48") (pin "1") (pinfunction "1_1") (pintype "passive"))
      (node (ref "R13") (pin "2") (pinfunction "2_2") (pintype "passive"))
      (node (ref "R45") (pin "1") (pinfunction "1_1") (pintype "passive"))
      (node (ref "SP4") (pin "1") (pinfunction "1_1") (pintype "bidirectional"))
    )
    (net (code "16") (name "GND") (class "Default")
      (node (ref "C1") (pin "2") (pinfunction "2_2") (pintype "passive"))
      (node (ref "C10") (pin "2") (pinfunction "2_2") (pintype "passive"))
      (node (ref "C103") (pin "2") (pinfunction "2_2") (pintype "passive"))
      (node (ref "C104") (pin "2") (pinfunction "2_2") (pintype "passive"))
      (node (ref "C105") (pin "2") (pinfunction "2_2") (pintype "passive"))
      (node (ref "C106") (pin "2") (pinfunction "2_2") (pintype "passive"))
      (node (ref "C107") (pin "2") (pinfunction "2_2") (pintype "passive"))
      (node (ref "C108") (pin "2") (pinfunction "2_2") (pintype "passive"))
      (node (ref "C109") (pin "2") (pinfunction "2_2") (pintype "passive"))
      (node (ref "C11") (pin "2") (pinfunction "2_2") (pintype "passive"))
      (node (ref "C110") (pin "2") (pinfunction "2_2") (pintype "passive"))
      (node (ref "C111") (pin "2") (pinfunction "2_2") (pintype "passive"))
      (node (ref "C112") (pin "2") (pinfunction "2_2") (pintype "passive"))
      (node (ref "C113") (pin "2") (pinfunction "2_2") (pintype "passive"))
      (node (ref "C114") (pin "2") (pinfunction "2_2") (pintype "passive"))
      (node (ref "C115") (pin "2") (pinfunction "2_2") (pintype "passive"))
      (node (ref "C12") (pin "2") (pinfunction "2_2") (pintype "passive"))
      (node (ref "C120") (pin "2") (pinfunction "2_2") (pintype "passive"))
      (node (ref "C122") (pin "2") (pinfunction "2_2") (pintype "passive"))
      (node (ref "C125") (pin "1") (pinfunction "1_1") (pintype "passive"))
      (node (ref "C127") (pin "2") (pinfunction "2_2") (pintype "passive"))
      (node (ref "C129") (pin "2") (pinfunction "2_2") (pintype "passive"))
      (node (ref "C13") (pin "2") (pinfunction "2_2") (pintype "passive"))
      (node (ref "C131") (pin "1") (pinfunction "1_1") (pintype "passive"))
      (node (ref "C132") (pin "1") (pinfunction "1_1") (pintype "passive"))
      (node (ref "C133") (pin "1") (pinfunction "1_1") (pintype "passive"))
      (node (ref "C134") (pin "2") (pinfunction "2_2") (pintype "passive"))
      (node (ref "C135") (pin "1") (pinfunction "1_1") (pintype "passive"))
      (node (ref "C136") (pin "2") (pinfunction "2_2") (pintype "passive"))
      (node (ref "C137") (pin "2") (pinfunction "2_2") (pintype "passive"))
      (node (ref "C138") (pin "2") (pinfunction "2_2") (pintype "passive"))
      (node (ref "C14") (pin "2") (pinfunction "2_2") (pintype "passive"))
      (node (ref "C15") (pin "2") (pinfunction "2_2") (pintype "passive"))
      (node (ref "C16") (pin "2") (pinfunction "2_2") (pintype "passive"))
      (node (ref "C17") (pin "2") (pinfunction "2_2") (pintype "passive"))
      (node (ref "C18") (pin "2") (pinfunction "2_2") (pintype "passive"))
      (node (ref "C19") (pin "2") (pinfunction "2_2") (pintype "passive"))
      (node (ref "C2") (pin "2") (pinfunction "2_2") (pintype "passive"))
      (node (ref "C20") (pin "2") (pinfunction "2_2") (pintype "passive"))
      (node (ref "C21") (pin "2") (pinfunction "2_2") (pintype "passive"))
      (node (ref "C22") (pin "2") (pinfunction "2_2") (pintype "passive"))
      (node (ref "C23") (pin "2") (pinfunction "2_2") (pintype "passive"))
      (node (ref "C24") (pin "2") (pinfunction "2_2") (pintype "passive"))
      (node (ref "C25") (pin "2") (pinfunction "2_2") (pintype "passive"))
      (node (ref "C26") (pin "2") (pinfunction "2_2") (pintype "passive"))
      (node (ref "C27") (pin "2") (pinfunction "2_2") (pintype "passive"))
      (node (ref "C29") (pin "2") (pinfunction "2_2") (pintype "passive"))
      (node (ref "C3") (pin "2") (pinfunction "2_2") (pintype "passive"))
      (node (ref "C30") (pin "2") (pinfunction "2_2") (pintype "passive"))
      (node (ref "C31") (pin "2") (pinfunction "-_2") (pintype "passive"))
      (node (ref "C32") (pin "2") (pinfunction "-_2") (pintype "passive"))
      (node (ref "C33") (pin "1") (pinfunction "1_1") (pintype "passive"))
      (node (ref "C34") (pin "2") (pinfunction "2_2") (pintype "passive"))
      (node (ref "C35") (pin "2") (pinfunction "2_2") (pintype "passive"))
      (node (ref "C36") (pin "2") (pinfunction "2_2") (pintype "passive"))
      (node (ref "C37") (pin "2") (pinfunction "2_2") (pintype "passive"))
      (node (ref "C38") (pin "2") (pinfunction "2_2") (pintype "passive"))
      (node (ref "C4") (pin "2") (pinfunction "2_2") (pintype "passive"))
      (node (ref "C40") (pin "2") (pinfunction "2_2") (pintype "passive"))
      (node (ref "C41") (pin "2") (pinfunction "2_2") (pintype "passive"))
      (node (ref "C42") (pin "2") (pinfunction "2_2") (pintype "passive"))
      (node (ref "C43") (pin "2") (pinfunction "2_2") (pintype "passive"))
      (node (ref "C44") (pin "2") (pinfunction "2_2") (pintype "passive"))
      (node (ref "C45") (pin "2") (pinfunction "2_2") (pintype "passive"))
      (node (ref "C46") (pin "2") (pinfunction "2_2") (pintype "passive"))
      (node (ref "C47") (pin "2") (pinfunction "2_2") (pintype "passive"))
      (node (ref "C5") (pin "2") (pinfunction "2_2") (pintype "passive"))
      (node (ref "C50") (pin "2") (pinfunction "2_2") (pintype "passive"))
      (node (ref "C52") (pin "2") (pinfunction "2_2") (pintype "passive"))
      (node (ref "C54") (pin "2") (pinfunction "2_2") (pintype "passive"))
      (node (ref "C56") (pin "2") (pinfunction "2_2") (pintype "passive"))
      (node (ref "C6") (pin "2") (pinfunction "2_2") (pintype "passive"))
      (node (ref "C61") (pin "2") (pinfunction "2_2") (pintype "passive"))
      (node (ref "C63") (pin "2") (pinfunction "2_2") (pintype "passive"))
      (node (ref "C64") (pin "2") (pinfunction "2_2") (pintype "passive"))
      (node (ref "C67") (pin "1") (pinfunction "1_1") (pintype "passive"))
      (node (ref "C7") (pin "2") (pinfunction "2_2") (pintype "passive"))
      (node (ref "C72") (pin "2") (pinfunction "2_2") (pintype "passive"))
      (node (ref "C75") (pin "2") (pinfunction "2_2") (pintype "passive"))
      (node (ref "C76") (pin "2") (pinfunction "2_2") (pintype "passive"))
      (node (ref "C77") (pin "2") (pinfunction "2_2") (pintype "passive"))
      (node (ref "C8") (pin "2") (pinfunction "2_2") (pintype "passive"))
      (node (ref "C81") (pin "2") (pinfunction "2_2") (pintype "passive"))
      (node (ref "C82") (pin "2") (pinfunction "2_2") (pintype "passive"))
      (node (ref "C83") (pin "S") (pinfunction "S_S") (pintype "passive"))
      (node (ref "C84") (pin "2") (pinfunction "2_2") (pintype "passive"))
      (node (ref "C86") (pin "1") (pinfunction "1_1") (pintype "passive"))
      (node (ref "C9") (pin "2") (pinfunction "2_2") (pintype "passive"))
      (node (ref "C90") (pin "2") (pinfunction "2_2") (pintype "passive"))
      (node (ref "C91") (pin "2") (pinfunction "2_2") (pintype "passive"))
      (node (ref "C92") (pin "2") (pinfunction "2_2") (pintype "passive"))
      (node (ref "C94") (pin "2") (pinfunction "2_2") (pintype "passive"))
      (node (ref "C95") (pin "2") (pinfunction "2_2") (pintype "passive"))
      (node (ref "C97") (pin "1") (pinfunction "1_1") (pintype "passive"))
      (node (ref "C98") (pin "2") (pinfunction "2_2") (pintype "passive"))
      (node (ref "C99") (pin "2") (pinfunction "2_2") (pintype "passive"))
      (node (ref "CN1") (pin "2") (pinfunction "2_2") (pintype "bidirectional"))
      (node (ref "CN2") (pin "A") (pinfunction "A_A") (pintype "bidirectional"))
      (node (ref "CN3") (pin "2") (pinfunction "2_2") (pintype "bidirectional"))
      (node (ref "CN4") (pin "5") (pinfunction "GND_5") (pintype "bidirectional"))
      (node (ref "CN4") (pin "6") (pinfunction "SHIELD1_6") (pintype "bidirectional"))
      (node (ref "CN4") (pin "7") (pinfunction "SHIELD2_7") (pintype "bidirectional"))
      (node (ref "CN4") (pin "8") (pinfunction "SHIELD3_8") (pintype "bidirectional"))
      (node (ref "CN4") (pin "9") (pinfunction "SHIELD4_9") (pintype "bidirectional"))
      (node (ref "CN5") (pin "2") (pinfunction "2_2") (pintype "bidirectional"))
      (node (ref "CN6") (pin "A") (pinfunction "A_A") (pintype "bidirectional"))
      (node (ref "CN7") (pin "A") (pinfunction "A_A") (pintype "bidirectional"))
      (node (ref "D1") (pin "A") (pinfunction "A_A") (pintype "passive"))
      (node (ref "D2") (pin "A") (pinfunction "A_A") (pintype "passive"))
      (node (ref "D3") (pin "A") (pinfunction "A_A") (pintype "passive"))
      (node (ref "D5") (pin "A") (pinfunction "A_A") (pintype "passive"))
      (node (ref "D8") (pin "C") (pinfunction "C_C") (pintype "passive"))
      (node (ref "FB6") (pin "1") (pinfunction "1_1") (pintype "passive"))
      (node (ref "J1") (pin "2") (pinfunction "2_2") (pintype "bidirectional"))
      (node (ref "J10") (pin "3") (pinfunction "3_3") (pintype "bidirectional"))
      (node (ref "J10") (pin "4") (pinfunction "4_4") (pintype "bidirectional"))
      (node (ref "J11") (pin "3") (pinfunction "3_3") (pintype "bidirectional"))
      (node (ref "J11") (pin "4") (pinfunction "4_4") (pintype "bidirectional"))
      (node (ref "J12") (pin "3") (pinfunction "3_3") (pintype "bidirectional"))
      (node (ref "J12") (pin "4") (pinfunction "4_4") (pintype "bidirectional"))
      (node (ref "J13") (pin "3") (pinfunction "3_3") (pintype "bidirectional"))
      (node (ref "J13") (pin "4") (pinfunction "4_4") (pintype "bidirectional"))
      (node (ref "J14") (pin "3") (pinfunction "3_3") (pintype "bidirectional"))
      (node (ref "J14") (pin "4") (pinfunction "4_4") (pintype "bidirectional"))
      (node (ref "J2") (pin "1") (pinfunction "1_1") (pintype "bidirectional"))
      (node (ref "J4") (pin "1") (pinfunction "1_1") (pintype "passive"))
      (node (ref "J6") (pin "3") (pinfunction "3_3") (pintype "bidirectional"))
      (node (ref "J6") (pin "4") (pinfunction "4_4") (pintype "bidirectional"))
      (node (ref "J7") (pin "3") (pinfunction "3_3") (pintype "bidirectional"))
      (node (ref "J7") (pin "4") (pinfunction "4_4") (pintype "bidirectional"))
      (node (ref "J8") (pin "3") (pinfunction "3_3") (pintype "bidirectional"))
      (node (ref "J8") (pin "4") (pinfunction "4_4") (pintype "bidirectional"))
      (node (ref "J9") (pin "3") (pinfunction "3_3") (pintype "bidirectional"))
      (node (ref "J9") (pin "4") (pinfunction "4_4") (pintype "bidirectional"))
      (node (ref "L18") (pin "P$2") (pinfunction "2_P$2") (pintype "passive"))
      (node (ref "L2") (pin "2") (pinfunction "2_2") (pintype "passive"))
      (node (ref "L3") (pin "2") (pinfunction "2_2") (pintype "passive"))
      (node (ref "L4") (pin "2") (pinfunction "2_2") (pintype "passive"))
      (node (ref "L5") (pin "2") (pinfunction "2_2") (pintype "passive"))
      (node (ref "L8") (pin "2") (pinfunction "2_2") (pintype "passive"))
      (node (ref "LED1") (pin "C") (pinfunction "C_C") (pintype "passive"))
      (node (ref "LED10") (pin "C") (pinfunction "C_C") (pintype "passive"))
      (node (ref "LED11") (pin "C") (pinfunction "C_C") (pintype "passive"))
      (node (ref "LED2") (pin "C") (pinfunction "C_C") (pintype "passive"))
      (node (ref "LED3") (pin "C") (pinfunction "C_C") (pintype "passive"))
      (node (ref "LED4") (pin "C") (pinfunction "C_C") (pintype "passive"))
      (node (ref "LED5") (pin "C") (pinfunction "C_C") (pintype "passive"))
      (node (ref "LED6") (pin "C") (pinfunction "C_C") (pintype "passive"))
      (node (ref "LED7") (pin "C") (pinfunction "C_C") (pintype "passive"))
      (node (ref "LED8") (pin "C") (pinfunction "C_C") (pintype "passive"))
      (node (ref "LED9") (pin "C") (pinfunction "C_C") (pintype "passive"))
      (node (ref "MIC1") (pin "2") (pinfunction "2_2") (pintype "bidirectional"))
      (node (ref "Q1") (pin "2") (pinfunction "E_2") (pintype "passive"))
      (node (ref "Q13") (pin "2") (pinfunction "S_2") (pintype "passive"))
      (node (ref "Q13") (pin "4") (pinfunction "S2_4") (pintype "bidirectional"))
      (node (ref "Q3") (pin "2") (pinfunction "E_2") (pintype "passive"))
      (node (ref "R101") (pin "2") (pinfunction "2_2") (pintype "passive"))
      (node (ref "R102") (pin "2") (pinfunction "2_2") (pintype "passive"))
      (node (ref "R104") (pin "1") (pinfunction "1_1") (pintype "passive"))
      (node (ref "R106") (pin "1") (pinfunction "1_1") (pintype "passive"))
      (node (ref "R107") (pin "1") (pinfunction "1_1") (pintype "passive"))
      (node (ref "R109") (pin "1") (pinfunction "1_1") (pintype "passive"))
      (node (ref "R11") (pin "1") (pinfunction "1_1") (pintype "passive"))
      (node (ref "R111") (pin "1") (pinfunction "1_1") (pintype "passive"))
      (node (ref "R113") (pin "1") (pinfunction "1_1") (pintype "passive"))
      (node (ref "R114") (pin "1") (pinfunction "1_1") (pintype "passive"))
      (node (ref "R118") (pin "1") (pinfunction "1_1") (pintype "passive"))
      (node (ref "R17") (pin "1") (pinfunction "1_1") (pintype "passive"))
      (node (ref "R36") (pin "2") (pinfunction "2_2") (pintype "passive"))
      (node (ref "R45") (pin "2") (pinfunction "2_2") (pintype "passive"))
      (node (ref "R48") (pin "1") (pinfunction "1_1") (pintype "passive"))
      (node (ref "R52") (pin "2") (pinfunction "2_2") (pintype "passive"))
      (node (ref "R53") (pin "2") (pinfunction "2_2") (pintype "passive"))
      (node (ref "R60") (pin "1") (pinfunction "1_1") (pintype "passive"))
      (node (ref "R64") (pin "1") (pinfunction "1_1") (pintype "passive"))
      (node (ref "R66") (pin "1") (pinfunction "1_1") (pintype "passive"))
      (node (ref "R67") (pin "1") (pinfunction "1_1") (pintype "passive"))
      (node (ref "R68") (pin "1") (pinfunction "1_1") (pintype "passive"))
      (node (ref "R69") (pin "1") (pinfunction "1_1") (pintype "passive"))
      (node (ref "R70") (pin "1") (pinfunction "1_1") (pintype "passive"))
      (node (ref "R72") (pin "1") (pinfunction "1_1") (pintype "passive"))
      (node (ref "R73") (pin "1") (pinfunction "1_1") (pintype "passive"))
      (node (ref "R77") (pin "1") (pinfunction "1_1") (pintype "passive"))
      (node (ref "R80") (pin "2") (pinfunction "2_2") (pintype "passive"))
      (node (ref "R82") (pin "1") (pinfunction "1_1") (pintype "passive"))
      (node (ref "R84") (pin "1") (pinfunction "1_1") (pintype "passive"))
      (node (ref "R87") (pin "1") (pinfunction "1_1") (pintype "passive"))
      (node (ref "R88") (pin "1") (pinfunction "1_1") (pintype "passive"))
      (node (ref "R93") (pin "1") (pinfunction "1_1") (pintype "passive"))
      (node (ref "R94") (pin "1") (pinfunction "1_1") (pintype "passive"))
      (node (ref "R95") (pin "1") (pinfunction "1_1") (pintype "passive"))
      (node (ref "S1") (pin "SGND") (pinfunction "P$1_SGND") (pintype "bidirectional"))
      (node (ref "S2") (pin "SGND") (pinfunction "P$1_SGND") (pintype "bidirectional"))
      (node (ref "S3") (pin "SGND") (pinfunction "P$1_SGND") (pintype "bidirectional"))
      (node (ref "S4") (pin "SGND") (pinfunction "P$1_SGND") (pintype "bidirectional"))
      (node (ref "S5") (pin "SGND") (pinfunction "P$1_SGND") (pintype "bidirectional"))
      (node (ref "S6") (pin "SGND") (pinfunction "P$1_SGND") (pintype "bidirectional"))
      (node (ref "S7") (pin "SGND") (pinfunction "P$1_SGND") (pintype "bidirectional"))
      (node (ref "SP1") (pin "2") (pinfunction "2_2") (pintype "bidirectional"))
      (node (ref "SP2") (pin "2") (pinfunction "2_2") (pintype "bidirectional"))
      (node (ref "SP3") (pin "2") (pinfunction "2_2") (pintype "bidirectional"))
      (node (ref "SP4") (pin "2") (pinfunction "2_2") (pintype "bidirectional"))
      (node (ref "SP5") (pin "2") (pinfunction "2_2") (pintype "bidirectional"))
      (node (ref "SP6") (pin "2") (pinfunction "2_2") (pintype "bidirectional"))
      (node (ref "SP7") (pin "2") (pinfunction "2_2") (pintype "bidirectional"))
      (node (ref "SP8") (pin "2") (pinfunction "2_2") (pintype "bidirectional"))
      (node (ref "SP9") (pin "2") (pinfunction "2_2") (pintype "bidirectional"))
      (node (ref "SW1") (pin "1") (pinfunction "1_1") (pintype "bidirectional"))
      (node (ref "SW1") (pin "2") (pinfunction "2_2") (pintype "bidirectional"))
      (node (ref "SW3") (pin "2") (pinfunction "2_2") (pintype "bidirectional"))
      (node (ref "SW3") (pin "3") (pinfunction "3_3") (pintype "bidirectional"))
      (node (ref "SW4") (pin "2") (pinfunction "2_2") (pintype "bidirectional"))
      (node (ref "SW4") (pin "3") (pinfunction "3_3") (pintype "bidirectional"))
      (node (ref "U1") (pin "10") (pinfunction "VSS5_10") (pintype "bidirectional"))
      (node (ref "U1") (pin "20") (pinfunction "VSSA_20") (pintype "bidirectional"))
      (node (ref "U1") (pin "27") (pinfunction "VSS4_27") (pintype "bidirectional"))
      (node (ref "U1") (pin "74") (pinfunction "VSS2_74") (pintype "bidirectional"))
      (node (ref "U1") (pin "99") (pinfunction "VSS_99") (pintype "bidirectional"))
      (node (ref "U10") (pin "2") (pinfunction "-IN_2") (pintype "input"))
      (node (ref "U10") (pin "4") (pinfunction "GND_4") (pintype "power_in"))
      (node (ref "U12") (pin "2") (pinfunction "GND_2") (pintype "bidirectional"))
      (node (ref "U12") (pin "4") (pinfunction "GND1_4") (pintype "bidirectional"))
      (node (ref "U13") (pin "2") (pinfunction "GND_2") (pintype "bidirectional"))
      (node (ref "U14") (pin "8") (pinfunction "GND_8") (pintype "power_in"))
      (node (ref "U15") (pin "3") (pinfunction "GND_3") (pintype "power_in"))
      (node (ref "U16") (pin "3") (pinfunction "GND_3") (pintype "bidirectional"))
      (node (ref "U2") (pin "2") (pinfunction "GND_2") (pintype "bidirectional"))
      (node (ref "U3") (pin "D2") (pinfunction "GND_D2") (pintype "bidirectional"))
      (node (ref "U4") (pin "1") (pinfunction "A0_1") (pintype "bidirectional"))
      (node (ref "U4") (pin "2") (pinfunction "A1_2") (pintype "bidirectional"))
      (node (ref "U4") (pin "3") (pinfunction "A2_3") (pintype "bidirectional"))
      (node (ref "U4") (pin "4") (pinfunction "GND_4") (pintype "bidirectional"))
      (node (ref "U4") (pin "7") (pinfunction "WP_7") (pintype "bidirectional"))
      (node (ref "U5") (pin "4") (pinfunction "GND_4") (pintype "bidirectional"))
      (node (ref "U6") (pin "1") (pinfunction "GND_1") (pintype "bidirectional"))
      (node (ref "U7") (pin "2") (pinfunction "GND_2") (pintype "bidirectional"))
      (node (ref "U8") (pin "1") (pinfunction "GND_1") (pintype "bidirectional"))
      (node (ref "U9") (pin "4") (pinfunction "GND_4") (pintype "bidirectional"))
      (node (ref "U9") (pin "EP") (pinfunction "EP_EP") (pintype "bidirectional"))
      (node (ref "X1") (pin "2") (pinfunction "2_2") (pintype "passive"))
      (node (ref "X1") (pin "3") (pinfunction "2_3") (pintype "passive"))
      (node (ref "X1") (pin "4") (pinfunction "2_4") (pintype "passive"))
      (node (ref "X1") (pin "5") (pinfunction "2_5") (pintype "passive"))
      (node (ref "XTAL1") (pin "2") (pinfunction "2_2") (pintype "passive"))
      (node (ref "XTAL1") (pin "4") (pinfunction "4_4") (pintype "passive"))
      (node (ref "XTAL2") (pin "2") (pinfunction "2_2") (pintype "passive"))
      (node (ref "XTAL2") (pin "4") (pinfunction "4_4") (pintype "passive"))
      (node (ref "XTAL3") (pin "2") (pinfunction "2_2") (pintype "passive"))
      (node (ref "XTAL4") (pin "2") (pinfunction "2_2") (pintype "passive"))
    )
    (net (code "17") (name "LED-ERR") (class "Default")
      (node (ref "R4") (pin "1") (pinfunction "1_1") (pintype "passive"))
      (node (ref "U1") (pin "62") (pinfunction "PD15_62") (pintype "bidirectional"))
    )
    (net (code "18") (name "LED-PTT") (class "Default")
      (node (ref "R2") (pin "1") (pinfunction "1_1") (pintype "passive"))
      (node (ref "U1") (pin "60") (pinfunction "PD13_60") (pintype "bidirectional"))
    )
    (net (code "19") (name "LED-PWR") (class "Default")
      (node (ref "R1") (pin "1") (pinfunction "1_1") (pintype "passive"))
      (node (ref "U1") (pin "59") (pinfunction "PD12_59") (pintype "bidirectional"))
    )
    (net (code "20") (name "LED-RT") (class "Default")
      (node (ref "R3") (pin "1") (pinfunction "1_1") (pintype "passive"))
      (node (ref "U1") (pin "61") (pinfunction "PD14_61") (pintype "bidirectional"))
    )
    (net (code "21") (name "MISO") (class "Default")
      (node (ref "P8") (pin "1") (pinfunction "1_1") (pintype "bidirectional"))
      (node (ref "U1") (pin "79") (pinfunction "PC11_79") (pintype "bidirectional"))
    )
    (net (code "22") (name "MOSI") (class "Default")
      (node (ref "P9") (pin "1") (pinfunction "1_1") (pintype "bidirectional"))
      (node (ref "U1") (pin "80") (pinfunction "PC12_80") (pintype "bidirectional"))
    )
    (net (code "23") (name "NRST") (class "Default")
      (node (ref "C4") (pin "1") (pinfunction "1_1") (pintype "passive"))
      (node (ref "R8") (pin "2") (pinfunction "2_2") (pintype "passive"))
      (node (ref "SW1") (pin "3") (pinfunction "3_3") (pintype "bidirectional"))
      (node (ref "SW1") (pin "4") (pinfunction "4_4") (pintype "bidirectional"))
      (node (ref "U1") (pin "14") (pinfunction "NRST_14") (pintype "bidirectional"))
    )
    (net (code "24") (name "NSS") (class "Default")
      (node (ref "P6") (pin "1") (pinfunction "1_1") (pintype "bidirectional"))
      (node (ref "U1") (pin "77") (pinfunction "PA15_77") (pintype "bidirectional"))
    )
    (net (code "25") (name "Net-(C19-Pad1)") (class "Default")
      (node (ref "C19") (pin "1") (pinfunction "1_1") (pintype "passive"))
      (node (ref "R15") (pin "2") (pinfunction "2_2") (pintype "passive"))
      (node (ref "XTAL1") (pin "1") (pinfunction "1_1") (pintype "passive"))
    )
    (net (code "26") (name "Net-(C20-Pad1)") (class "Default")
      (node (ref "C20") (pin "1") (pinfunction "1_1") (pintype "passive"))
      (node (ref "CN2") (pin "C") (pinfunction "C_C") (pintype "bidirectional"))
      (node (ref "D1") (pin "C") (pinfunction "C_C") (pintype "passive"))
      (node (ref "R20") (pin "2") (pinfunction "2_2") (pintype "passive"))
      (node (ref "R23") (pin "1") (pinfunction "1_1") (pintype "passive"))
    )
    (net (code "27") (name "Net-(C25-Pad1)") (class "Default")
      (node (ref "C25") (pin "1") (pinfunction "1_1") (pintype "passive"))
      (node (ref "CN5") (pin "1") (pinfunction "1_1") (pintype "bidirectional"))
      (node (ref "D3") (pin "C") (pinfunction "C_C") (pintype "passive"))
      (node (ref "FB3") (pin "1") (pinfunction "1_1") (pintype "passive"))
      (node (ref "SP9") (pin "1") (pinfunction "1_1") (pintype "bidirectional"))
    )
    (net (code "28") (name "Net-(C27-Pad1)") (class "Default")
      (node (ref "C27") (pin "1") (pinfunction "1_1") (pintype "passive"))
      (node (ref "C28") (pin "1") (pinfunction "1_1") (pintype "passive"))
      (node (ref "R31") (pin "2") (pinfunction "2_2") (pintype "passive"))
      (node (ref "R33") (pin "1") (pinfunction "1_1") (pintype "passive"))
    )
    (net (code "29") (name "Net-(C28-Pad2)") (class "Default")
      (node (ref "C28") (pin "2") (pinfunction "2_2") (pintype "passive"))
      (node (ref "R35") (pin "1") (pinfunction "1_1") (pintype "passive"))
    )
    (net (code "30") (name "Net-(C31-+)") (class "Default")
      (node (ref "C30") (pin "1") (pinfunction "1_1") (pintype "passive"))
      (node (ref "C31") (pin "1") (pinfunction "+_1") (pintype "passive"))
      (node (ref "R32") (pin "1") (pinfunction "1_1") (pintype "passive"))
      (node (ref "R33") (pin "2") (pinfunction "2_2") (pintype "passive"))
    )
    (net (code "31") (name "Net-(C32-+)") (class "Default")
      (node (ref "C32") (pin "1") (pinfunction "+_1") (pintype "passive"))
      (node (ref "C33") (pin "2") (pinfunction "2_2") (pintype "passive"))
      (node (ref "R36") (pin "1") (pinfunction "1_1") (pintype "passive"))
      (node (ref "R38") (pin "1") (pinfunction "1_1") (pintype "passive"))
      (node (ref "U7") (pin "1") (pinfunction "+IN_1") (pintype "input"))
    )
    (net (code "32") (name "Net-(C39-Pad1)") (class "Default")
      (node (ref "C39") (pin "1") (pinfunction "1_1") (pintype "passive"))
      (node (ref "R37") (pin "2") (pinfunction "2_2") (pintype "passive"))
      (node (ref "R39") (pin "2") (pinfunction "2_2") (pintype "passive"))
      (node (ref "R39") (pin "3") (pinfunction "3_3") (pintype "passive"))
    )
    (net (code "33") (name "Net-(C48-Pad2)") (class "Default")
      (node (ref "C48") (pin "2") (pinfunction "2_2") (pintype "passive"))
      (node (ref "R48") (pin "3") (pinfunction "3_3") (pintype "passive"))
    )
    (net (code "34") (name "Net-(C53-Pad2)") (class "Default")
      (node (ref "C53") (pin "2") (pinfunction "2_2") (pintype "passive"))
      (node (ref "R53") (pin "1") (pinfunction "1_1") (pintype "passive"))
    )
    (net (code "35") (name "Net-(C55-Pad2)") (class "Default")
      (node (ref "C55") (pin "2") (pinfunction "2_2") (pintype "passive"))
      (node (ref "FB5") (pin "1") (pinfunction "1_1") (pintype "passive"))
    )
    (net (code "36") (name "Net-(C57-Pad2)") (class "Default")
      (node (ref "C57") (pin "2") (pinfunction "2_2") (pintype "passive"))
      (node (ref "C58") (pin "1") (pinfunction "1_1") (pintype "passive"))
      (node (ref "J6") (pin "1") (pinfunction "1_1") (pintype "bidirectional"))
    )
    (net (code "37") (name "Net-(C58-Pad2)") (class "Default")
      (node (ref "C58") (pin "2") (pinfunction "2_2") (pintype "passive"))
      (node (ref "R62") (pin "2") (pinfunction "2_2") (pintype "passive"))
    )
    (net (code "38") (name "Net-(C59-Pad1)") (class "Default")
      (node (ref "C59") (pin "1") (pinfunction "1_1") (pintype "passive"))
      (node (ref "R63") (pin "1") (pinfunction "1_1") (pintype "passive"))
    )
    (net (code "39") (name "Net-(C60-Pad2)") (class "Default")
      (node (ref "C60") (pin "2") (pinfunction "2_2") (pintype "passive"))
      (node (ref "R68") (pin "2") (pinfunction "2_2") (pintype "passive"))
    )
    (net (code "40") (name "Net-(C62-Pad1)") (class "Default")
      (node (ref "C62") (pin "1") (pinfunction "1_1") (pintype "passive"))
      (node (ref "C64") (pin "1") (pinfunction "1_1") (pintype "passive"))
      (node (ref "C66") (pin "2") (pinfunction "2_2") (pintype "passive"))
      (node (ref "L2") (pin "1") (pinfunction "1_1") (pintype "passive"))
    )
    (net (code "41") (name "Net-(C62-Pad2)") (class "Default")
      (node (ref "C62") (pin "2") (pinfunction "2_2") (pintype "passive"))
      (node (ref "J7") (pin "2") (pinfunction "2_2") (pintype "bidirectional"))
    )
    (net (code "42") (name "Net-(C65-Pad2)") (class "Default")
      (node (ref "C65") (pin "2") (pinfunction "2_2") (pintype "passive"))
      (node (ref "R69") (pin "2") (pinfunction "2_2") (pintype "passive"))
    )
    (net (code "43") (name "Net-(C66-Pad1)") (class "Default")
      (node (ref "C66") (pin "1") (pinfunction "1_1") (pintype "passive"))
      (node (ref "C67") (pin "2") (pinfunction "2_2") (pintype "passive"))
      (node (ref "C69") (pin "2") (pinfunction "2_2") (pintype "passive"))
      (node (ref "L3") (pin "1") (pinfunction "1_1") (pintype "passive"))
    )
    (net (code "44") (name "Net-(C68-Pad1)") (class "Default")
      (node (ref "C68") (pin "1") (pinfunction "1_1") (pintype "passive"))
      (node (ref "R74") (pin "1") (pinfunction "1_1") (pintype "passive"))
    )
    (net (code "45") (name "Net-(C69-Pad1)") (class "Default")
      (node (ref "C69") (pin "1") (pinfunction "1_1") (pintype "passive"))
      (node (ref "J8") (pin "1") (pinfunction "1_1") (pintype "bidirectional"))
    )
    (net (code "46") (name "Net-(C70-Pad1)") (class "Default")
      (node (ref "C70") (pin "1") (pinfunction "1_1") (pintype "passive"))
      (node (ref "C71") (pin "2") (pinfunction "2_2") (pintype "passive"))
      (node (ref "J9") (pin "1") (pinfunction "1_1") (pintype "bidirectional"))
    )
    (net (code "47") (name "Net-(C70-Pad2)") (class "Default")
      (node (ref "C70") (pin "2") (pinfunction "2_2") (pintype "passive"))
      (node (ref "R75") (pin "2") (pinfunction "2_2") (pintype "passive"))
    )
    (net (code "48") (name "Net-(C72-Pad1)") (class "Default")
      (node (ref "C72") (pin "1") (pinfunction "1_1") (pintype "passive"))
      (node (ref "FB7") (pin "2") (pinfunction "2_2") (pintype "passive"))
      (node (ref "R78") (pin "2") (pinfunction "2_2") (pintype "passive"))
    )
    (net (code "49") (name "Net-(C73-Pad1)") (class "Default")
      (node (ref "C73") (pin "1") (pinfunction "1_1") (pintype "passive"))
      (node (ref "D6") (pin "A") (pinfunction "A_A") (pintype "passive"))
      (node (ref "FB7") (pin "1") (pinfunction "1_1") (pintype "passive"))
    )
    (net (code "50") (name "Net-(C74-Pad1)") (class "Default")
      (node (ref "C74") (pin "1") (pinfunction "1_1") (pintype "passive"))
      (node (ref "D7") (pin "A") (pinfunction "A_A") (pintype "passive"))
      (node (ref "FB8") (pin "2") (pinfunction "2_2") (pintype "passive"))
    )
    (net (code "51") (name "Net-(C74-Pad2)") (class "Default")
      (node (ref "C74") (pin "2") (pinfunction "2_2") (pintype "passive"))
      (node (ref "J10") (pin "1") (pinfunction "1_1") (pintype "bidirectional"))
    )
    (net (code "52") (name "Net-(C75-Pad1)") (class "Default")
      (node (ref "C75") (pin "1") (pinfunction "1_1") (pintype "passive"))
      (node (ref "FB8") (pin "1") (pinfunction "1_1") (pintype "passive"))
      (node (ref "R79") (pin "2") (pinfunction "2_2") (pintype "passive"))
    )
    (net (code "53") (name "Net-(C76-Pad1)") (class "Default")
      (node (ref "C76") (pin "1") (pinfunction "1_1") (pintype "passive"))
      (node (ref "C77") (pin "1") (pinfunction "1_1") (pintype "passive"))
      (node (ref "FB10") (pin "2") (pinfunction "2_2") (pintype "passive"))
      (node (ref "FB9") (pin "1") (pinfunction "1_1") (pintype "passive"))
    )
    (net (code "54") (name "Net-(C78-Pad2)") (class "Default")
      (node (ref "C78") (pin "2") (pinfunction "2_2") (pintype "passive"))
      (node (ref "J11") (pin "1") (pinfunction "1_1") (pintype "bidirectional"))
    )
    (net (code "55") (name "Net-(C79-Pad2)") (class "Default")
      (node (ref "C79") (pin "2") (pinfunction "2_2") (pintype "passive"))
      (node (ref "J10") (pin "2") (pinfunction "2_2") (pintype "bidirectional"))
      (node (ref "L4") (pin "1") (pinfunction "1_1") (pintype "passive"))
    )
    (net (code "56") (name "Net-(C80-Pad1)") (class "Default")
      (node (ref "C80") (pin "1") (pinfunction "1_1") (pintype "passive"))
      (node (ref "C82") (pin "1") (pinfunction "1_1") (pintype "passive"))
      (node (ref "C85") (pin "2") (pinfunction "2_2") (pintype "passive"))
      (node (ref "L5") (pin "1") (pinfunction "1_1") (pintype "passive"))
    )
    (net (code "57") (name "Net-(C80-Pad2)") (class "Default")
      (node (ref "C80") (pin "2") (pinfunction "2_2") (pintype "passive"))
      (node (ref "J11") (pin "2") (pinfunction "2_2") (pintype "bidirectional"))
    )
    (net (code "58") (name "Net-(C84-Pad1)") (class "Default")
      (node (ref "C84") (pin "1") (pinfunction "1_1") (pintype "passive"))
      (node (ref "L6") (pin "1") (pinfunction "1_1") (pintype "passive"))
      (node (ref "R81") (pin "2") (pinfunction "2_2") (pintype "passive"))
      (node (ref "R85") (pin "2") (pinfunction "2_2") (pintype "passive"))
    )
    (net (code "59") (name "Net-(C85-Pad1)") (class "Default")
      (node (ref "C85") (pin "1") (pinfunction "1_1") (pintype "passive"))
      (node (ref "C86") (pin "2") (pinfunction "2_2") (pintype "passive"))
      (node (ref "C89") (pin "2") (pinfunction "2_2") (pintype "passive"))
      (node (ref "L8") (pin "1") (pinfunction "1_1") (pintype "passive"))
    )
    (net (code "60") (name "Net-(C89-Pad1)") (class "Default")
      (node (ref "C89") (pin "1") (pinfunction "1_1") (pintype "passive"))
      (node (ref "C92") (pin "1") (pinfunction "1_1") (pintype "passive"))
      (node (ref "D8") (pin "A") (pinfunction "A_A") (pintype "passive"))
      (node (ref "L10") (pin "1") (pinfunction "1_1") (pintype "passive"))
    )
    (net (code "61") (name "Net-(C90-Pad1)") (class "Default")
      (node (ref "C90") (pin "1") (pinfunction "1_1") (pintype "passive"))
      (node (ref "L9") (pin "1") (pinfunction "1_1") (pintype "passive"))
      (node (ref "R85") (pin "1") (pinfunction "1_1") (pintype "passive"))
      (node (ref "R86") (pin "2") (pinfunction "2_2") (pintype "passive"))
      (node (ref "R91") (pin "2") (pinfunction "2_2") (pintype "passive"))
    )
    (net (code "62") (name "Net-(C93-Pad2)") (class "Default")
      (node (ref "C93") (pin "2") (pinfunction "2_2") (pintype "passive"))
      (node (ref "L9") (pin "2") (pinfunction "2_2") (pintype "passive"))
      (node (ref "Q12") (pin "2") (pinfunction "C_2") (pintype "passive"))
      (node (ref "Q12") (pin "4") (pinfunction "C_4") (pintype "passive"))
    )
    (net (code "63") (name "Net-(C94-Pad1)") (class "Default")
      (node (ref "C94") (pin "1") (pinfunction "1_1") (pintype "passive"))
      (node (ref "FB11") (pin "2") (pinfunction "2_2") (pintype "passive"))
      (node (ref "R89") (pin "1") (pinfunction "1_1") (pintype "passive"))
    )
    (net (code "64") (name "Net-(C96-Pad1)") (class "Default")
      (node (ref "C96") (pin "1") (pinfunction "1_1") (pintype "passive"))
      (node (ref "D9") (pin "A") (pinfunction "A_A") (pintype "passive"))
      (node (ref "L11") (pin "2") (pinfunction "2_2") (pintype "passive"))
    )
    (net (code "65") (name "Net-(C98-Pad1)") (class "Default")
      (node (ref "C98") (pin "1") (pinfunction "1_1") (pintype "passive"))
      (node (ref "FB12") (pin "1") (pinfunction "1_1") (pintype "passive"))
      (node (ref "R89") (pin "2") (pinfunction "2_2") (pintype "passive"))
    )
    (net (code "66") (name "Net-(C99-Pad1)") (class "Default")
      (node (ref "C99") (pin "1") (pinfunction "1_1") (pintype "passive"))
      (node (ref "R92") (pin "1") (pinfunction "1_1") (pintype "passive"))
    )
    (net (code "67") (name "Net-(C100-Pad2)") (class "Default")
      (node (ref "C100") (pin "2") (pinfunction "2_2") (pintype "passive"))
      (node (ref "C95") (pin "1") (pinfunction "1_1") (pintype "passive"))
      (node (ref "D9") (pin "C") (pinfunction "C_C") (pintype "passive"))
      (node (ref "L10") (pin "2") (pinfunction "2_2") (pintype "passive"))
    )
    (net (code "68") (name "Net-(C102-Pad2)") (class "Default")
      (node (ref "C102") (pin "2") (pinfunction "2_2") (pintype "passive"))
      (node (ref "C105") (pin "1") (pinfunction "1_1") (pintype "passive"))
      (node (ref "L14") (pin "1") (pinfunction "1_1") (pintype "passive"))
    )
    (net (code "69") (name "Net-(C103-Pad1)") (class "Default")
      (node (ref "C103") (pin "1") (pinfunction "1_1") (pintype "passive"))
      (node (ref "L11") (pin "1") (pinfunction "1_1") (pintype "passive"))
      (node (ref "R90") (pin "1") (pinfunction "1_1") (pintype "passive"))
      (node (ref "R95") (pin "2") (pinfunction "2_2") (pintype "passive"))
    )
    (net (code "70") (name "Net-(C104-Pad1)") (class "Default")
      (node (ref "C104") (pin "1") (pinfunction "1_1") (pintype "passive"))
      (node (ref "C106") (pin "1") (pinfunction "1_1") (pintype "passive"))
      (node (ref "L13") (pin "1") (pinfunction "1_1") (pintype "passive"))
      (node (ref "L15") (pin "1") (pinfunction "1_1") (pintype "passive"))
    )
    (net (code "71") (name "Net-(C107-Pad1)") (class "Default")
      (node (ref "C107") (pin "1") (pinfunction "1_1") (pintype "passive"))
      (node (ref "L14") (pin "2") (pinfunction "2_2") (pintype "passive"))
      (node (ref "L16") (pin "1") (pinfunction "1_1") (pintype "passive"))
    )
    (net (code "72") (name "Net-(C110-Pad1)") (class "Default")
      (node (ref "C110") (pin "1") (pinfunction "1_1") (pintype "passive"))
      (node (ref "J12") (pin "1") (pinfunction "1_1") (pintype "bidirectional"))
      (node (ref "L16") (pin "2") (pinfunction "2_2") (pintype "passive"))
    )
    (net (code "73") (name "Net-(C115-Pad1)") (class "Default")
      (node (ref "C115") (pin "1") (pinfunction "1_1") (pintype "passive"))
      (node (ref "XTAL3") (pin "1") (pinfunction "1_1") (pintype "passive"))
      (node (ref "XTAL4") (pin "1") (pinfunction "1_1") (pintype "passive"))
    )
    (net (code "74") (name "Net-(C119-Pad2)") (class "Default")
      (node (ref "C119") (pin "2") (pinfunction "2_2") (pintype "passive"))
      (node (ref "J13") (pin "1") (pinfunction "1_1") (pintype "bidirectional"))
    )
    (net (code "75") (name "Net-(C122-Pad1)") (class "Default")
      (node (ref "C122") (pin "1") (pinfunction "1_1") (pintype "passive"))
      (node (ref "FB16") (pin "1") (pinfunction "1_1") (pintype "passive"))
      (node (ref "R108") (pin "1") (pinfunction "1_1") (pintype "passive"))
    )
    (net (code "76") (name "Net-(C123-Pad1)") (class "Default")
      (node (ref "C123") (pin "1") (pinfunction "1_1") (pintype "passive"))
      (node (ref "C124") (pin "2") (pinfunction "2_2") (pintype "passive"))
      (node (ref "J13") (pin "2") (pinfunction "2_2") (pintype "bidirectional"))
      (node (ref "R109") (pin "2") (pinfunction "2_2") (pintype "passive"))
    )
    (net (code "77") (name "Net-(C126-Pad2)") (class "Default")
      (node (ref "C126") (pin "2") (pinfunction "2_2") (pintype "passive"))
      (node (ref "R114") (pin "2") (pinfunction "2_2") (pintype "passive"))
    )
    (net (code "78") (name "Net-(C127-Pad1)") (class "Default")
      (node (ref "C127") (pin "1") (pinfunction "1_1") (pintype "passive"))
      (node (ref "R110") (pin "2") (pinfunction "2_2") (pintype "passive"))
      (node (ref "R112") (pin "2") (pinfunction "2_2") (pintype "passive"))
      (node (ref "R115") (pin "2") (pinfunction "2_2") (pintype "passive"))
    )
    (net (code "79") (name "Net-(C129-Pad1)") (class "Default")
      (node (ref "C129") (pin "1") (pinfunction "1_1") (pintype "passive"))
      (node (ref "FB18") (pin "1") (pinfunction "1_1") (pintype "passive"))
      (node (ref "R115") (pin "1") (pinfunction "1_1") (pintype "passive"))
    )
    (net (code "80") (name "Net-(C130-Pad1)") (class "Default")
      (node (ref "C130") (pin "1") (pinfunction "1_1") (pintype "passive"))
      (node (ref "R119") (pin "1") (pinfunction "1_1") (pintype "passive"))
    )
    (net (code "81") (name "Net-(C134-Pad1)") (class "Default")
      (node (ref "C134") (pin "1") (pinfunction "1_1") (pintype "passive"))
      (node (ref "FB18") (pin "2") (pinfunction "2_2") (pintype "passive"))
      (node (ref "R117") (pin "2") (pinfunction "2_2") (pintype "passive"))
      (node (ref "R119") (pin "2") (pinfunction "2_2") (pintype "passive"))
      (node (ref "R120") (pin "2") (pinfunction "2_2") (pintype "passive"))
    )
    (net (code "82") (name "Net-(C136-Pad1)") (class "Default")
      (node (ref "C136") (pin "1") (pinfunction "1_1") (pintype "passive"))
      (node (ref "FB19") (pin "1") (pinfunction "1_1") (pintype "passive"))
      (node (ref "R120") (pin "1") (pinfunction "1_1") (pintype "passive"))
    )
    (net (code "83") (name "Net-(CN1-Pad1)") (class "Default")
      (node (ref "CN1") (pin "1") (pinfunction "1_1") (pintype "bidirectional"))
      (node (ref "R5") (pin "2") (pinfunction "2_2") (pintype "passive"))
    )
    (net (code "84") (name "Net-(CN1-Pad3)") (class "Default")
      (node (ref "CN1") (pin "3") (pinfunction "3_3") (pintype "bidirectional"))
      (node (ref "R6") (pin "2") (pinfunction "2_2") (pintype "passive"))
    )
    (net (code "85") (name "Net-(CN4-DM)") (class "Default")
      (node (ref "CN4") (pin "2") (pinfunction "DM_2") (pintype "bidirectional"))
      (node (ref "R21") (pin "1") (pinfunction "1_1") (pintype "passive"))
      (node (ref "U3") (pin "D1") (pinfunction "D-IN_D1") (pintype "bidirectional"))
    )
    (net (code "86") (name "Net-(CN4-DP)") (class "Default")
      (node (ref "CN4") (pin "3") (pinfunction "DP_3") (pintype "bidirectional"))
      (node (ref "R24") (pin "1") (pinfunction "1_1") (pintype "passive"))
      (node (ref "U3") (pin "C1") (pinfunction "D+IN_C1") (pintype "bidirectional"))
    )
    (net (code "87") (name "Net-(CN4-ID)") (class "Default")
      (node (ref "CN4") (pin "4") (pinfunction "ID_4") (pintype "bidirectional"))
      (node (ref "R26") (pin "1") (pinfunction "1_1") (pintype "passive"))
      (node (ref "U3") (pin "A3") (pinfunction "ID_A3") (pintype "bidirectional"))
    )
    (net (code "88") (name "Net-(CN6-PadC)") (class "Default")
      (node (ref "CN6") (pin "C") (pinfunction "C_C") (pintype "bidirectional"))
      (node (ref "D2") (pin "C") (pinfunction "C_C") (pintype "passive"))
      (node (ref "FB2") (pin "1") (pinfunction "1_1") (pintype "passive"))
    )
    (net (code "89") (name "Net-(CN6-PadD)") (class "Default")
      (node (ref "CN6") (pin "D") (pinfunction "D_D") (pintype "bidirectional"))
      (node (ref "MIC1") (pin "1") (pinfunction "1_1") (pintype "bidirectional"))
    )
    (net (code "90") (name "Net-(CN7-PadB)") (class "Default")
      (node (ref "CN7") (pin "B") (pinfunction "B_B") (pintype "bidirectional"))
      (node (ref "J5") (pin "1") (pinfunction "1_1") (pintype "bidirectional"))
    )
    (net (code "91") (name "Net-(CN7-PadC)") (class "Default")
      (node (ref "CN7") (pin "C") (pinfunction "C_C") (pintype "bidirectional"))
      (node (ref "D5") (pin "C") (pinfunction "C_C") (pintype "passive"))
      (node (ref "FB5") (pin "2") (pinfunction "2_2") (pintype "passive"))
      (node (ref "J5") (pin "2") (pinfunction "2_2") (pintype "bidirectional"))
    )
    (net (code "92") (name "Net-(CN7-PadD)") (class "Default")
      (node (ref "CN7") (pin "D") (pinfunction "D_D") (pintype "bidirectional"))
      (node (ref "J4") (pin "2") (pinfunction "2_2") (pintype "passive"))
    )
    (net (code "93") (name "Net-(D4-K)") (class "Default")
      (node (ref "D4") (pin "C") (pinfunction "K_C") (pintype "passive"))
      (node (ref "SW5") (pin "1") (pinfunction "1_1") (pintype "passive"))
      (node (ref "SW5") (pin "4") (pinfunction "4_4") (pintype "passive"))
    )
    (net (code "94") (name "Net-(D4-PadA)") (class "Default")
      (node (ref "D4") (pin "A") (pinfunction "A_A") (pintype "passive"))
      (node (ref "FB3") (pin "2") (pinfunction "2_2") (pintype "passive"))
    )
    (net (code "95") (name "Net-(D6-PadC)") (class "Default")
      (node (ref "D6") (pin "C") (pinfunction "C_C") (pintype "passive"))
      (node (ref "D7") (pin "C") (pinfunction "C_C") (pintype "passive"))
      (node (ref "FB6") (pin "2") (pinfunction "2_2") (pintype "passive"))
      (node (ref "J8") (pin "2") (pinfunction "2_2") (pintype "bidirectional"))
    )
    (net (code "96") (name "Net-(D10-A)") (class "Default")
      (node (ref "C101") (pin "1") (pinfunction "1_1") (pintype "passive"))
      (node (ref "D10") (pin "3") (pinfunction "A_3") (pintype "passive"))
      (node (ref "R93") (pin "2") (pinfunction "2_2") (pintype "passive"))
    )
    (net (code "97") (name "Net-(FB2-Pad2)") (class "Default")
      (node (ref "FB2") (pin "2") (pinfunction "2_2") (pintype "passive"))
      (node (ref "R31") (pin "1") (pinfunction "1_1") (pintype "passive"))
    )
    (net (code "98") (name "Net-(FB17-Pad2)") (class "Default")
      (node (ref "FB17") (pin "2") (pinfunction "2_2") (pintype "passive"))
      (node (ref "R116") (pin "2") (pinfunction "2_2") (pintype "passive"))
    )
    (net (code "99") (name "Net-(J3-Pad1)") (class "Default")
      (node (ref "J3") (pin "1") (pinfunction "1_1") (pintype "bidirectional"))
      (node (ref "R32") (pin "2") (pinfunction "2_2") (pintype "passive"))
    )
    (net (code "100") (name "Net-(L12-Pad2)") (class "Default")
      (node (ref "L12") (pin "2") (pinfunction "2_2") (pintype "passive"))
      (node (ref "R91") (pin "1") (pinfunction "1_1") (pintype "passive"))
    )
    (net (code "101") (name "Net-(L17-2)") (class "Default")
      (node (ref "C112") (pin "1") (pinfunction "1_1") (pintype "passive"))
      (node (ref "L17") (pin "P$2") (pinfunction "2_P$2") (pintype "passive"))
      (node (ref "XTAL3") (pin "3") (pinfunction "3_3") (pintype "passive"))
    )
    (net (code "102") (name "Net-(L18-1)") (class "Default")
      (node (ref "C117") (pin "1") (pinfunction "1_1") (pintype "passive"))
      (node (ref "C83") (pin "R1") (pinfunction "R_R1") (pintype "passive"))
      (node (ref "C83") (pin "R2") (pinfunction "R_R2") (pintype "passive"))
      (node (ref "L18") (pin "P$1") (pinfunction "1_P$1") (pintype "passive"))
      (node (ref "XTAL4") (pin "3") (pinfunction "3_3") (pintype "passive"))
    )
    (net (code "103") (name "Net-(L19-1)") (class "Default")
      (node (ref "C123") (pin "2") (pinfunction "2_2") (pintype "passive"))
      (node (ref "L19") (pin "P$1") (pinfunction "1_P$1") (pintype "passive"))
      (node (ref "U16") (pin "1") (pinfunction "IN_A_1") (pintype "bidirectional"))
    )
    (net (code "104") (name "Net-(L19-2)") (class "Default")
      (node (ref "C124") (pin "1") (pinfunction "1_1") (pintype "passive"))
      (node (ref "C125") (pin "2") (pinfunction "2_2") (pintype "passive"))
      (node (ref "L19") (pin "P$2") (pinfunction "2_P$2") (pintype "passive"))
      (node (ref "U16") (pin "2") (pinfunction "IN_B_2") (pintype "bidirectional"))
    )
    (net (code "105") (name "Net-(L20-1)") (class "Default")
      (node (ref "C132") (pin "2") (pinfunction "2_2") (pintype "passive"))
      (node (ref "L20") (pin "P$1") (pinfunction "1_P$1") (pintype "passive"))
      (node (ref "U16") (pin "4") (pinfunction "OUT_A_4") (pintype "bidirectional"))
    )
    (net (code "106") (name "Net-(LED1-PadA)") (class "Default")
      (node (ref "LED1") (pin "A") (pinfunction "A_A") (pintype "passive"))
      (node (ref "R1") (pin "2") (pinfunction "2_2") (pintype "passive"))
    )
    (net (code "107") (name "Net-(LED2-PadA)") (class "Default")
      (node (ref "LED2") (pin "A") (pinfunction "A_A") (pintype "passive"))
      (node (ref "R2") (pin "2") (pinfunction "2_2") (pintype "passive"))
    )
    (net (code "108") (name "Net-(LED3-PadA)") (class "Default")
      (node (ref "LED3") (pin "A") (pinfunction "A_A") (pintype "passive"))
      (node (ref "R3") (pin "2") (pinfunction "2_2") (pintype "passive"))
    )
    (net (code "109") (name "Net-(LED4-PadA)") (class "Default")
      (node (ref "LED4") (pin "A") (pinfunction "A_A") (pintype "passive"))
      (node (ref "R4") (pin "2") (pinfunction "2_2") (pintype "passive"))
    )
    (net (code "110") (name "Net-(LED5-PadA)") (class "Default")
      (node (ref "LED5") (pin "A") (pinfunction "A_A") (pintype "passive"))
      (node (ref "R30") (pin "1") (pinfunction "1_1") (pintype "passive"))
    )
    (net (code "111") (name "Net-(LED6-PadA)") (class "Default")
      (node (ref "LED6") (pin "A") (pinfunction "A_A") (pintype "passive"))
      (node (ref "R34") (pin "1") (pinfunction "1_1") (pintype "passive"))
    )
    (net (code "112") (name "Net-(LED7-PadA)") (class "Default")
      (node (ref "LED7") (pin "A") (pinfunction "A_A") (pintype "passive"))
      (node (ref "R40") (pin "1") (pinfunction "1_1") (pintype "passive"))
    )
    (net (code "113") (name "Net-(LED8-PadA)") (class "Default")
      (node (ref "LED8") (pin "A") (pinfunction "A_A") (pintype "passive"))
      (node (ref "R44") (pin "1") (pinfunction "1_1") (pintype "passive"))
    )
    (net (code "114") (name "Net-(LED9-PadA)") (class "Default")
      (node (ref "LED9") (pin "A") (pinfunction "A_A") (pintype "passive"))
      (node (ref "R50") (pin "1") (pinfunction "1_1") (pintype "passive"))
    )
    (net (code "115") (name "Net-(LED10-PadA)") (class "Default")
      (node (ref "LED10") (pin "A") (pinfunction "A_A") (pintype "passive"))
      (node (ref "R55") (pin "1") (pinfunction "1_1") (pintype "passive"))
    )
    (net (code "116") (name "Net-(LED11-PadA)") (class "Default")
      (node (ref "LED11") (pin "A") (pinfunction "A_A") (pintype "passive"))
      (node (ref "R57") (pin "1") (pinfunction "1_1") (pintype "passive"))
    )
    (net (code "117") (name "Net-(Q1-B)") (class "Default")
      (node (ref "Q1") (pin "1") (pinfunction "B_1") (pintype "passive"))
      (node (ref "R46") (pin "2") (pinfunction "2_2") (pintype "passive"))
    )
    (net (code "118") (name "Net-(Q1-C)") (class "Default")
      (node (ref "Q1") (pin "3") (pinfunction "C_3") (pintype "passive"))
      (node (ref "Q2") (pin "1") (pinfunction "G_1") (pintype "bidirectional"))
      (node (ref "R47") (pin "1") (pinfunction "1_1") (pintype "passive"))
    )
    (net (code "119") (name "Net-(Q3-B)") (class "Default")
      (node (ref "Q3") (pin "1") (pinfunction "B_1") (pintype "passive"))
      (node (ref "R54") (pin "2") (pinfunction "2_2") (pintype "passive"))
    )
    (net (code "120") (name "Net-(Q3-C)") (class "Default")
      (node (ref "Q3") (pin "3") (pinfunction "C_3") (pintype "passive"))
      (node (ref "Q4") (pin "1") (pinfunction "G_1") (pintype "bidirectional"))
      (node (ref "R56") (pin "1") (pinfunction "1_1") (pintype "passive"))
    )
    (net (code "121") (name "Net-(Q5-B)") (class "Default")
      (node (ref "Q5") (pin "1") (pinfunction "B_1") (pintype "passive"))
      (node (ref "Q7") (pin "2") (pinfunction "E_2") (pintype "passive"))
      (node (ref "R67") (pin "2") (pinfunction "2_2") (pintype "passive"))
    )
    (net (code "122") (name "Net-(Q5-C)") (class "Default")
      (node (ref "C63") (pin "1") (pinfunction "1_1") (pintype "passive"))
      (node (ref "Q5") (pin "3") (pinfunction "C_3") (pintype "passive"))
      (node (ref "Q7") (pin "3") (pinfunction "C_3") (pintype "passive"))
      (node (ref "R61") (pin "2") (pinfunction "2_2") (pintype "passive"))
      (node (ref "R71") (pin "1") (pinfunction "1_1") (pintype "passive"))
      (node (ref "R76") (pin "2") (pinfunction "2_2") (pintype "passive"))
    )
    (net (code "123") (name "Net-(Q5-E)") (class "Default")
      (node (ref "Q5") (pin "2") (pinfunction "E_2") (pintype "passive"))
      (node (ref "R62") (pin "1") (pinfunction "1_1") (pintype "passive"))
      (node (ref "R64") (pin "2") (pinfunction "2_2") (pintype "passive"))
    )
    (net (code "124") (name "Net-(Q6-B)") (class "Default")
      (node (ref "C57") (pin "1") (pinfunction "1_1") (pintype "passive"))
      (node (ref "C59") (pin "2") (pinfunction "2_2") (pintype "passive"))
      (node (ref "Q6") (pin "1") (pinfunction "B_1") (pintype "passive"))
      (node (ref "R59") (pin "1") (pinfunction "1_1") (pintype "passive"))
      (node (ref "R60") (pin "2") (pinfunction "2_2") (pintype "passive"))
    )
    (net (code "125") (name "Net-(Q6-C)") (class "Default")
      (node (ref "Q6") (pin "3") (pinfunction "C_3") (pintype "passive"))
      (node (ref "Q8") (pin "1") (pinfunction "B_1") (pintype "passive"))
      (node (ref "R63") (pin "2") (pinfunction "2_2") (pintype "passive"))
      (node (ref "R65") (pin "2") (pinfunction "2_2") (pintype "passive"))
    )
    (net (code "126") (name "Net-(Q6-E)") (class "Default")
      (node (ref "C60") (pin "1") (pinfunction "1_1") (pintype "passive"))
      (node (ref "Q6") (pin "2") (pinfunction "E_2") (pintype "passive"))
      (node (ref "R66") (pin "2") (pinfunction "2_2") (pintype "passive"))
    )
    (net (code "127") (name "Net-(Q7-B)") (class "Default")
      (node (ref "Q7") (pin "1") (pinfunction "B_1") (pintype "passive"))
      (node (ref "Q9") (pin "3") (pinfunction "C_3") (pintype "passive"))
      (node (ref "R71") (pin "2") (pinfunction "2_2") (pintype "passive"))
      (node (ref "R74") (pin "2") (pinfunction "2_2") (pintype "passive"))
    )
    (net (code "128") (name "Net-(Q9-B)") (class "Default")
      (node (ref "C68") (pin "2") (pinfunction "2_2") (pintype "passive"))
      (node (ref "C71") (pin "1") (pinfunction "1_1") (pintype "passive"))
      (node (ref "Q9") (pin "1") (pinfunction "B_1") (pintype "passive"))
      (node (ref "R76") (pin "1") (pinfunction "1_1") (pintype "passive"))
      (node (ref "R77") (pin "2") (pinfunction "2_2") (pintype "passive"))
    )
    (net (code "129") (name "Net-(Q9-E)") (class "Default")
      (node (ref "C65") (pin "1") (pinfunction "1_1") (pintype "passive"))
      (node (ref "Q9") (pin "2") (pinfunction "E_2") (pintype "passive"))
      (node (ref "R72") (pin "2") (pinfunction "2_2") (pintype "passive"))
    )
    (net (code "130") (name "Net-(Q10-B)") (class "Default")
      (node (ref "Q10") (pin "1") (pinfunction "B_1") (pintype "passive"))
      (node (ref "Q8") (pin "2") (pinfunction "E_2") (pintype "passive"))
      (node (ref "R70") (pin "2") (pinfunction "2_2") (pintype "passive"))
    )
    (net (code "131") (name "Net-(Q10-C)") (class "Default")
      (node (ref "C61") (pin "1") (pinfunction "1_1") (pintype "passive"))
      (node (ref "Q10") (pin "3") (pinfunction "C_3") (pintype "passive"))
      (node (ref "Q8") (pin "3") (pinfunction "C_3") (pintype "passive"))
      (node (ref "R58") (pin "1") (pinfunction "1_1") (pintype "passive"))
      (node (ref "R59") (pin "2") (pinfunction "2_2") (pintype "passive"))
      (node (ref "R65") (pin "1") (pinfunction "1_1") (pintype "passive"))
    )
    (net (code "132") (name "Net-(Q10-E)") (class "Default")
      (node (ref "Q10") (pin "2") (pinfunction "E_2") (pintype "passive"))
      (node (ref "R73") (pin "2") (pinfunction "2_2") (pintype "passive"))
      (node (ref "R75") (pin "1") (pinfunction "1_1") (pintype "passive"))
    )
    (net (code "133") (name "Net-(Q11-B)") (class "Default")
      (node (ref "C79") (pin "1") (pinfunction "1_1") (pintype "passive"))
      (node (ref "Q11") (pin "1") (pinfunction "B_1") (pintype "passive"))
      (node (ref "R81") (pin "1") (pinfunction "1_1") (pintype "passive"))
      (node (ref "R82") (pin "2") (pinfunction "2_2") (pintype "passive"))
    )
    (net (code "134") (name "Net-(Q11-C)") (class "Default")
      (node (ref "C87") (pin "2") (pinfunction "2_2") (pintype "passive"))
      (node (ref "L6") (pin "2") (pinfunction "2_2") (pintype "passive"))
      (node (ref "Q11") (pin "3") (pinfunction "C_3") (pintype "passive"))
    )
    (net (code "135") (name "Net-(Q11-E)") (class "Default")
      (node (ref "C81") (pin "1") (pinfunction "1_1") (pintype "passive"))
      (node (ref "Q11") (pin "2") (pinfunction "E_2") (pintype "passive"))
      (node (ref "R84") (pin "2") (pinfunction "2_2") (pintype "passive"))
    )
    (net (code "136") (name "Net-(Q12-B)") (class "Default")
      (node (ref "C87") (pin "1") (pinfunction "1_1") (pintype "passive"))
      (node (ref "Q12") (pin "1") (pinfunction "B_1") (pintype "passive"))
      (node (ref "R86") (pin "1") (pinfunction "1_1") (pintype "passive"))
      (node (ref "R87") (pin "2") (pinfunction "2_2") (pintype "passive"))
    )
    (net (code "137") (name "Net-(Q12-E)") (class "Default")
      (node (ref "C91") (pin "1") (pinfunction "1_1") (pintype "passive"))
      (node (ref "Q12") (pin "3") (pinfunction "E_3") (pintype "passive"))
      (node (ref "R88") (pin "2") (pinfunction "2_2") (pintype "passive"))
    )
    (net (code "138") (name "Net-(Q13-D)") (class "Default")
      (node (ref "C102") (pin "1") (pinfunction "1_1") (pintype "passive"))
      (node (ref "L13") (pin "2") (pinfunction "2_2") (pintype "passive"))
      (node (ref "Q13") (pin "3") (pinfunction "D_3") (pintype "passive"))
    )
    (net (code "139") (name "Net-(Q13-G)") (class "Default")
      (node (ref "C93") (pin "1") (pinfunction "1_1") (pintype "passive"))
      (node (ref "FB12") (pin "2") (pinfunction "2_2") (pintype "passive"))
      (node (ref "Q13") (pin "1") (pinfunction "G_1") (pintype "passive"))
      (node (ref "R92") (pin "2") (pinfunction "2_2") (pintype "passive"))
    )
    (net (code "140") (name "Net-(Q14-B)") (class "Default")
      (node (ref "C118") (pin "1") (pinfunction "1_1") (pintype "passive"))
      (node (ref "Q14") (pin "1") (pinfunction "B_1") (pintype "passive"))
      (node (ref "R103") (pin "1") (pinfunction "1_1") (pintype "passive"))
      (node (ref "R104") (pin "2") (pinfunction "2_2") (pintype "passive"))
    )
    (net (code "141") (name "Net-(Q14-C)") (class "Default")
      (node (ref "C117") (pin "2") (pinfunction "2_2") (pintype "passive"))
      (node (ref "Q14") (pin "3") (pinfunction "C_3") (pintype "passive"))
      (node (ref "Q15") (pin "1") (pinfunction "B_1") (pintype "passive"))
      (node (ref "R105") (pin "1") (pinfunction "1_1") (pintype "passive"))
    )
    (net (code "142") (name "Net-(Q14-E)") (class "Default")
      (node (ref "C121") (pin "1") (pinfunction "1_1") (pintype "passive"))
      (node (ref "Q14") (pin "2") (pinfunction "E_2") (pintype "passive"))
      (node (ref "R106") (pin "2") (pinfunction "2_2") (pintype "passive"))
    )
    (net (code "143") (name "Net-(Q15-C)") (class "Default")
      (node (ref "C120") (pin "1") (pinfunction "1_1") (pintype "passive"))
      (node (ref "Q15") (pin "3") (pinfunction "C_3") (pintype "passive"))
      (node (ref "R103") (pin "2") (pinfunction "2_2") (pintype "passive"))
      (node (ref "R105") (pin "2") (pinfunction "2_2") (pintype "passive"))
      (node (ref "R108") (pin "2") (pinfunction "2_2") (pintype "passive"))
    )
    (net (code "144") (name "Net-(Q15-E)") (class "Default")
      (node (ref "C119") (pin "1") (pinfunction "1_1") (pintype "passive"))
      (node (ref "Q15") (pin "2") (pinfunction "E_2") (pintype "passive"))
      (node (ref "R107") (pin "2") (pinfunction "2_2") (pintype "passive"))
    )
    (net (code "145") (name "Net-(Q16-B)") (class "Default")
      (node (ref "J14") (pin "2") (pinfunction "2_2") (pintype "bidirectional"))
      (node (ref "Q16") (pin "1") (pinfunction "B_1") (pintype "passive"))
      (node (ref "R110") (pin "1") (pinfunction "1_1") (pintype "passive"))
      (node (ref "R111") (pin "2") (pinfunction "2_2") (pintype "passive"))
    )
    (net (code "146") (name "Net-(Q16-C)") (class "Default")
      (node (ref "Q16") (pin "3") (pinfunction "C_3") (pintype "passive"))
      (node (ref "Q17") (pin "1") (pinfunction "B_1") (pintype "passive"))
      (node (ref "R112") (pin "1") (pinfunction "1_1") (pintype "passive"))
    )
    (net (code "147") (name "Net-(Q16-E)") (class "Default")
      (node (ref "C126") (pin "1") (pinfunction "1_1") (pintype "passive"))
      (node (ref "Q16") (pin "2") (pinfunction "E_2") (pintype "passive"))
      (node (ref "R113") (pin "2") (pinfunction "2_2") (pintype "passive"))
    )
    (net (code "148") (name "Net-(Q17-E)") (class "Default")
      (node (ref "C130") (pin "2") (pinfunction "2_2") (pintype "passive"))
      (node (ref "Q17") (pin "2") (pinfunction "E_2") (pintype "passive"))
      (node (ref "R117") (pin "1") (pinfunction "1_1") (pintype "passive"))
    )
    (net (code "149") (name "Net-(R17-Pad2)") (class "Default")
      (node (ref "R17") (pin "2") (pinfunction "2_2") (pintype "passive"))
      (node (ref "R19") (pin "2") (pinfunction "2_2") (pintype "passive"))
      (node (ref "SW2") (pin "1") (pinfunction "1_1") (pintype "passive"))
      (node (ref "SW2") (pin "4") (pinfunction "4_4") (pintype "passive"))
    )
    (net (code "150") (name "Net-(R41-Pad1)") (class "Default")
      (node (ref "R41") (pin "1") (pinfunction "1_1") (pintype "passive"))
      (node (ref "SW5") (pin "2") (pinfunction "2_2") (pintype "passive"))
      (node (ref "SW5") (pin "3") (pinfunction "3_3") (pintype "passive"))
      (node (ref "SW5") (pin "5") (pinfunction "5_5") (pintype "passive"))
      (node (ref "SW5") (pin "6") (pinfunction "6_6") (pintype "passive"))
    )
    (net (code "151") (name "Net-(U1A-PA5)") (class "Default")
      (node (ref "R13") (pin "1") (pinfunction "1_1") (pintype "passive"))
      (node (ref "U1") (pin "30") (pinfunction "PA5_30") (pintype "bidirectional"))
    )
    (net (code "152") (name "Net-(U1B-VCAP1)") (class "Default")
      (node (ref "C18") (pin "1") (pinfunction "1_1") (pintype "passive"))
      (node (ref "U1") (pin "49") (pinfunction "VCAP1_49") (pintype "bidirectional"))
    )
    (net (code "153") (name "Net-(U1B-VCAP2)") (class "Default")
      (node (ref "C17") (pin "1") (pinfunction "1_1") (pintype "passive"))
      (node (ref "U1") (pin "73") (pinfunction "VCAP2_73") (pintype "bidirectional"))
    )
    (net (code "154") (name "Net-(U2-~{EN})") (class "Default")
      (node (ref "R16") (pin "2") (pinfunction "2_2") (pintype "passive"))
      (node (ref "R18") (pin "1") (pinfunction "1_1") (pintype "passive"))
      (node (ref "U2") (pin "4") (pinfunction "~{EN}_4") (pintype "bidirectional"))
    )
    (net (code "155") (name "Net-(U6-IN)") (class "Default")
      (node (ref "C137") (pin "1") (pinfunction "1_1") (pintype "passive"))
      (node (ref "C26") (pin "1") (pinfunction "1_1") (pintype "passive"))
      (node (ref "FB20") (pin "2") (pinfunction "2_2") (pintype "passive"))
      (node (ref "U6") (pin "3") (pinfunction "IN_3") (pintype "bidirectional"))
    )
    (net (code "156") (name "Net-(U7--IN)") (class "Default")
      (node (ref "R35") (pin "2") (pinfunction "2_2") (pintype "passive"))
      (node (ref "R37") (pin "1") (pinfunction "1_1") (pintype "passive"))
      (node (ref "U7") (pin "3") (pinfunction "-IN_3") (pintype "input"))
    )
    (net (code "157") (name "Net-(U7-OUT)") (class "Default")
      (node (ref "C39") (pin "2") (pinfunction "2_2") (pintype "passive"))
      (node (ref "R39") (pin "1") (pinfunction "1_1") (pintype "passive"))
      (node (ref "R42") (pin "2") (pinfunction "2_2") (pintype "passive"))
      (node (ref "U7") (pin "4") (pinfunction "OUT_4") (pintype "output"))
    )
    (net (code "158") (name "Net-(U8-IN)") (class "Default")
      (node (ref "C138") (pin "1") (pinfunction "1_1") (pintype "passive"))
      (node (ref "C36") (pin "1") (pinfunction "1_1") (pintype "passive"))
      (node (ref "FB4") (pin "2") (pinfunction "2_2") (pintype "passive"))
      (node (ref "U8") (pin "3") (pinfunction "IN_3") (pintype "bidirectional"))
    )
    (net (code "159") (name "Net-(U9-EN)") (class "Default")
      (node (ref "R43") (pin "2") (pinfunction "2_2") (pintype "passive"))
      (node (ref "U9") (pin "7") (pinfunction "EN_7") (pintype "bidirectional"))
    )
    (net (code "160") (name "Net-(U9-SS)") (class "Default")
      (node (ref "C47") (pin "1") (pinfunction "1_1") (pintype "passive"))
      (node (ref "U9") (pin "8") (pinfunction "SS_8") (pintype "bidirectional"))
    )
    (net (code "161") (name "Net-(U9-SW)") (class "Default")
      (node (ref "C49") (pin "2") (pinfunction "2_2") (pintype "passive"))
      (node (ref "L1") (pin "1") (pinfunction "1_1") (pintype "passive"))
      (node (ref "U9") (pin "3") (pinfunction "SW_3") (pintype "bidirectional"))
    )
    (net (code "162") (name "Net-(U9-VBST)") (class "Default")
      (node (ref "C49") (pin "1") (pinfunction "1_1") (pintype "passive"))
      (node (ref "U9") (pin "1") (pinfunction "VBST_1") (pintype "bidirectional"))
    )
    (net (code "163") (name "Net-(U9-VFB)") (class "Default")
      (node (ref "C51") (pin "2") (pinfunction "2_2") (pintype "passive"))
      (node (ref "R51") (pin "2") (pinfunction "2_2") (pintype "passive"))
      (node (ref "R52") (pin "1") (pinfunction "1_1") (pintype "passive"))
      (node (ref "U9") (pin "5") (pinfunction "VFB_5") (pintype "bidirectional"))
    )
    (net (code "164") (name "Net-(U9-VREG5)") (class "Default")
      (node (ref "C46") (pin "1") (pinfunction "1_1") (pintype "passive"))
      (node (ref "U9") (pin "6") (pinfunction "VREG5_6") (pintype "bidirectional"))
    )
    (net (code "165") (name "Net-(U10-+IN)") (class "Default")
      (node (ref "C50") (pin "1") (pinfunction "1_1") (pintype "passive"))
      (node (ref "R48") (pin "2") (pinfunction "2_2") (pintype "passive"))
      (node (ref "U10") (pin "3") (pinfunction "+IN_3") (pintype "input"))
    )
    (net (code "166") (name "Net-(U10-OUT)") (class "Default")
      (node (ref "C53") (pin "1") (pinfunction "1_1") (pintype "passive"))
      (node (ref "C55") (pin "1") (pinfunction "1_1") (pintype "passive"))
      (node (ref "U10") (pin "5") (pinfunction "OUT_5") (pintype "output"))
    )
    (net (code "167") (name "Net-(U10-VS)") (class "Default")
      (node (ref "C52") (pin "1") (pinfunction "1_1") (pintype "passive"))
      (node (ref "R49") (pin "2") (pinfunction "2_2") (pintype "passive"))
      (node (ref "U10") (pin "6") (pinfunction "VS_6") (pintype "passive"))
    )
    (net (code "168") (name "Net-(U11-G3)") (class "Default")
      (node (ref "J6") (pin "2") (pinfunction "2_2") (pintype "bidirectional"))
      (node (ref "U11") (pin "5") (pinfunction "G3_5") (pintype "bidirectional"))
    )
    (net (code "169") (name "Net-(U11-RF)") (class "Default")
      (node (ref "J7") (pin "1") (pinfunction "1_1") (pintype "bidirectional"))
      (node (ref "U11") (pin "3") (pinfunction "RF_3") (pintype "bidirectional"))
    )
    (net (code "170") (name "Net-(U12-1N)") (class "Default")
      (node (ref "C78") (pin "1") (pinfunction "1_1") (pintype "passive"))
      (node (ref "U12") (pin "1") (pinfunction "1N_1") (pintype "bidirectional"))
    )
    (net (code "171") (name "Net-(U12-OUT)") (class "Default")
      (node (ref "C73") (pin "2") (pinfunction "2_2") (pintype "passive"))
      (node (ref "FB10") (pin "1") (pinfunction "1_1") (pintype "passive"))
      (node (ref "U12") (pin "3") (pinfunction "OUT_3") (pintype "bidirectional"))
    )
    (net (code "172") (name "Net-(U13--IN)") (class "Default")
      (node (ref "R80") (pin "1") (pinfunction "1_1") (pintype "passive"))
      (node (ref "R83") (pin "1") (pinfunction "1_1") (pintype "passive"))
      (node (ref "U13") (pin "3") (pinfunction "-IN_3") (pintype "input"))
    )
    (net (code "173") (name "Net-(U14-CLK0)") (class "Default")
      (node (ref "R100") (pin "2") (pinfunction "2_2") (pintype "passive"))
      (node (ref "R99") (pin "2") (pinfunction "2_2") (pintype "passive"))
      (node (ref "U14") (pin "10") (pinfunction "CLK0_10") (pintype "output"))
    )
    (net (code "174") (name "Net-(U14-CLK1)") (class "Default")
      (node (ref "R96") (pin "2") (pinfunction "2_2") (pintype "passive"))
      (node (ref "U14") (pin "9") (pinfunction "CLK1_9") (pintype "output"))
    )
    (net (code "175") (name "Net-(U14-CLK2)") (class "Default")
      (node (ref "R97") (pin "2") (pinfunction "2_2") (pintype "passive"))
      (node (ref "U14") (pin "6") (pinfunction "CLK2_6") (pintype "output"))
    )
    (net (code "176") (name "Net-(U14-VDD)") (class "Default")
      (node (ref "C114") (pin "1") (pinfunction "1_1") (pintype "passive"))
      (node (ref "FB15") (pin "2") (pinfunction "2_2") (pintype "passive"))
      (node (ref "U14") (pin "1") (pinfunction "VDD_1") (pintype "power_in"))
    )
    (net (code "177") (name "Net-(U14-VDDO)") (class "Default")
      (node (ref "C113") (pin "1") (pinfunction "1_1") (pintype "passive"))
      (node (ref "FB14") (pin "2") (pinfunction "2_2") (pintype "passive"))
      (node (ref "U14") (pin "7") (pinfunction "VDDO_7") (pintype "power_in"))
    )
    (net (code "178") (name "Net-(U14-XA)") (class "Default")
      (node (ref "U14") (pin "2") (pinfunction "XA_2") (pintype "bidirectional"))
      (node (ref "XTAL2") (pin "1") (pinfunction "1_1") (pintype "passive"))
    )
    (net (code "179") (name "Net-(U14-XB)") (class "Default")
      (node (ref "U14") (pin "3") (pinfunction "XB_3") (pintype "bidirectional"))
      (node (ref "XTAL2") (pin "3") (pinfunction "3_3") (pintype "passive"))
    )
    (net (code "180") (name "Net-(U15-CLK+)") (class "Default")
      (node (ref "R98") (pin "2") (pinfunction "2_2") (pintype "passive"))
      (node (ref "U15") (pin "4") (pinfunction "CLK+_4") (pintype "output"))
    )
    (net (code "181") (name "Net-(U15-OE)") (class "Default")
      (node (ref "C111") (pin "1") (pinfunction "1_1") (pintype "passive"))
      (node (ref "FB13") (pin "2") (pinfunction "2_2") (pintype "passive"))
      (node (ref "U15") (pin "2") (pinfunction "OE_2") (pintype "input"))
      (node (ref "U15") (pin "6") (pinfunction "VDD_6") (pintype "power_in"))
    )
    (net (code "182") (name "Net-(U16-OSC_B)") (class "Default")
      (node (ref "C128") (pin "2") (pinfunction "2_2") (pintype "passive"))
      (node (ref "U16") (pin "6") (pinfunction "OSC_B_6") (pintype "bidirectional"))
    )
    (net (code "183") (name "Net-(U16-VIN)") (class "Default")
      (node (ref "C131") (pin "2") (pinfunction "2_2") (pintype "passive"))
      (node (ref "C133") (pin "2") (pinfunction "2_2") (pintype "passive"))
      (node (ref "R116") (pin "1") (pinfunction "1_1") (pintype "passive"))
      (node (ref "U16") (pin "8") (pinfunction "VIN_8") (pintype "bidirectional"))
    )
    (net (code "184") (name "OSC_IN") (class "Default")
      (node (ref "C21") (pin "1") (pinfunction "1_1") (pintype "passive"))
      (node (ref "U1") (pin "12") (pinfunction "PH0_12") (pintype "bidirectional"))
      (node (ref "XTAL1") (pin "3") (pinfunction "3_3") (pintype "passive"))
    )
    (net (code "185") (name "OSC_OUT") (class "Default")
      (node (ref "R15") (pin "1") (pinfunction "1_1") (pintype "passive"))
      (node (ref "U1") (pin "13") (pinfunction "PH1_13") (pintype "bidirectional"))
    )
    (net (code "186") (name "OTG_DM") (class "Default")
      (node (ref "R21") (pin "2") (pinfunction "2_2") (pintype "passive"))
      (node (ref "U1") (pin "70") (pinfunction "PA11_70") (pintype "bidirectional"))
      (node (ref "U3") (pin "D3") (pinfunction "D-OUT_D3") (pintype "bidirectional"))
    )
    (net (code "187") (name "OTG_DP") (class "Default")
      (node (ref "R24") (pin "2") (pinfunction "2_2") (pintype "passive"))
      (node (ref "U1") (pin "71") (pinfunction "PA12_71") (pintype "bidirectional"))
      (node (ref "U3") (pin "C3") (pinfunction "D+OUT_C3") (pintype "bidirectional"))
    )
    (net (code "188") (name "OTG_ID") (class "Default")
      (node (ref "R26") (pin "2") (pinfunction "2_2") (pintype "passive"))
      (node (ref "U1") (pin "69") (pinfunction "PA10_69") (pintype "bidirectional"))
    )
    (net (code "189") (name "OTG_OVR_CUR") (class "Default")
      (node (ref "R25") (pin "2") (pinfunction "2_2") (pintype "passive"))
      (node (ref "U1") (pin "86") (pinfunction "PD5_86") (pintype "bidirectional"))
      (node (ref "U2") (pin "3") (pinfunction "~{FAULT}_3") (pintype "bidirectional"))
    )
    (net (code "190") (name "OTG_PWR_ON") (class "Default")
      (node (ref "R16") (pin "1") (pinfunction "1_1") (pintype "passive"))
      (node (ref "U1") (pin "15") (pinfunction "PC0_15") (pintype "bidirectional"))
    )
    (net (code "191") (name "PA_OUTPUT") (class "Default")
      (node (ref "C96") (pin "2") (pinfunction "2_2") (pintype "passive"))
      (node (ref "J12") (pin "2") (pinfunction "2_2") (pintype "bidirectional"))
    )
    (net (code "192") (name "PE0") (class "Default")
      (node (ref "J2") (pin "2") (pinfunction "2_2") (pintype "bidirectional"))
      (node (ref "U1") (pin "97") (pinfunction "PE0_97") (pintype "bidirectional"))
    )
    (net (code "193") (name "PE1") (class "Default")
      (node (ref "J2") (pin "3") (pinfunction "3_3") (pintype "bidirectional"))
      (node (ref "U1") (pin "98") (pinfunction "PE1_98") (pintype "bidirectional"))
    )
    (net (code "194") (name "PE2") (class "Default")
      (node (ref "J2") (pin "4") (pinfunction "4_4") (pintype "bidirectional"))
      (node (ref "U1") (pin "1") (pinfunction "PE2_1") (pintype "bidirectional"))
    )
    (net (code "195") (name "PE3") (class "Default")
      (node (ref "J2") (pin "5") (pinfunction "5_5") (pintype "bidirectional"))
      (node (ref "U1") (pin "2") (pinfunction "PE3_2") (pintype "bidirectional"))
    )
    (net (code "196") (name "RX+12V") (class "Default")
      (node (ref "Q2") (pin "3") (pinfunction "D_3") (pintype "bidirectional"))
      (node (ref "R50") (pin "2") (pinfunction "2_2") (pintype "passive"))
      (node (ref "R58") (pin "2") (pinfunction "2_2") (pintype "passive"))
      (node (ref "R78") (pin "1") (pinfunction "1_1") (pintype "passive"))
    )
    (net (code "197") (name "RX-2ND-LO") (class "Default")
      (node (ref "C128") (pin "1") (pinfunction "1_1") (pintype "passive"))
      (node (ref "R100") (pin "1") (pinfunction "1_1") (pintype "passive"))
      (node (ref "R102") (pin "1") (pinfunction "1_1") (pintype "passive"))
      (node (ref "SP8") (pin "1") (pinfunction "1_1") (pintype "bidirectional"))
    )
    (net (code "198") (name "SCK") (class "Default")
      (node (ref "P7") (pin "1") (pinfunction "1_1") (pintype "bidirectional"))
      (node (ref "U1") (pin "78") (pinfunction "PC10_78") (pintype "bidirectional"))
    )
    (net (code "199") (name "SCL3") (class "Default")
      (node (ref "R29") (pin "2") (pinfunction "2_2") (pintype "passive"))
      (node (ref "U1") (pin "67") (pinfunction "PA8_67") (pintype "bidirectional"))
      (node (ref "U14") (pin "4") (pinfunction "SCL_4") (pintype "bidirectional"))
      (node (ref "U15") (pin "8") (pinfunction "SCL_8") (pintype "bidirectional"))
      (node (ref "U4") (pin "6") (pinfunction "SCL_6") (pintype "bidirectional"))
    )
    (net (code "200") (name "SDA3") (class "Default")
      (node (ref "R28") (pin "2") (pinfunction "2_2") (pintype "passive"))
      (node (ref "U1") (pin "66") (pinfunction "PC9_66") (pintype "bidirectional"))
      (node (ref "U14") (pin "5") (pinfunction "SDA_5") (pintype "bidirectional"))
      (node (ref "U15") (pin "7") (pinfunction "SDA_7") (pintype "bidirectional"))
      (node (ref "U4") (pin "5") (pinfunction "SDA_5") (pintype "bidirectional"))
    )
    (net (code "201") (name "SWCLK") (class "Default")
      (node (ref "R5") (pin "1") (pinfunction "1_1") (pintype "passive"))
      (node (ref "U1") (pin "76") (pinfunction "PA14_76") (pintype "bidirectional"))
    )
    (net (code "202") (name "SWDIO") (class "Default")
      (node (ref "R6") (pin "1") (pinfunction "1_1") (pintype "passive"))
      (node (ref "U1") (pin "72") (pinfunction "PA13_72") (pintype "bidirectional"))
    )
    (net (code "203") (name "TIAOUT") (class "Default")
      (node (ref "J9") (pin "2") (pinfunction "2_2") (pintype "bidirectional"))
      (node (ref "L17") (pin "P$1") (pinfunction "1_P$1") (pintype "passive"))
    )
    (net (code "204") (name "TX+12V") (class "Default")
      (node (ref "L12") (pin "1") (pinfunction "1_1") (pintype "passive"))
      (node (ref "Q4") (pin "3") (pinfunction "D_3") (pintype "bidirectional"))
      (node (ref "R57") (pin "2") (pinfunction "2_2") (pintype "passive"))
      (node (ref "R61") (pin "1") (pinfunction "1_1") (pintype "passive"))
      (node (ref "R79") (pin "1") (pinfunction "1_1") (pintype "passive"))
      (node (ref "R90") (pin "2") (pinfunction "2_2") (pintype "passive"))
    )
    (net (code "205") (name "TX-2ND-LO") (class "Default")
      (node (ref "C121") (pin "2") (pinfunction "2_2") (pintype "passive"))
      (node (ref "R101") (pin "1") (pinfunction "1_1") (pintype "passive"))
      (node (ref "R99") (pin "1") (pinfunction "1_1") (pintype "passive"))
      (node (ref "SP7") (pin "1") (pinfunction "1_1") (pintype "bidirectional"))
    )
    (net (code "206") (name "TX_DAC") (class "Default")
      (node (ref "C118") (pin "2") (pinfunction "2_2") (pintype "passive"))
      (node (ref "SP3") (pin "1") (pinfunction "1_1") (pintype "bidirectional"))
      (node (ref "U1") (pin "29") (pinfunction "PA4_29") (pintype "bidirectional"))
    )
    (net (code "207") (name "USART3_RX") (class "Default")
      (node (ref "CN3") (pin "3") (pinfunction "3_3") (pintype "bidirectional"))
      (node (ref "R9") (pin "2") (pinfunction "2_2") (pintype "passive"))
      (node (ref "U1") (pin "48") (pinfunction "PB11_48") (pintype "bidirectional"))
    )
    (net (code "208") (name "USART3_TX") (class "Default")
      (node (ref "CN3") (pin "1") (pinfunction "1_1") (pintype "bidirectional"))
      (node (ref "R10") (pin "2") (pinfunction "2_2") (pintype "passive"))
      (node (ref "U1") (pin "47") (pinfunction "PB10_47") (pintype "bidirectional"))
    )
    (net (code "209") (name "VBAT") (class "Default")
      (node (ref "C16") (pin "1") (pinfunction "1_1") (pintype "passive"))
      (node (ref "R14") (pin "2") (pinfunction "2_2") (pintype "passive"))
      (node (ref "U1") (pin "6") (pinfunction "VBAT_6") (pintype "bidirectional"))
    )
    (net (code "210") (name "VBUS") (class "Default")
      (node (ref "C22") (pin "1") (pinfunction "1_1") (pintype "passive"))
      (node (ref "CN4") (pin "1") (pinfunction "VBUS_1") (pintype "bidirectional"))
      (node (ref "U1") (pin "68") (pinfunction "PA9_68") (pintype "bidirectional"))
      (node (ref "U2") (pin "1") (pinfunction "OUT_1") (pintype "bidirectional"))
      (node (ref "U3") (pin "B3") (pinfunction "VBUS_B3") (pintype "bidirectional"))
    )
    (net (code "211") (name "VDDA") (class "Default")
      (node (ref "C12") (pin "1") (pinfunction "1_1") (pintype "passive"))
      (node (ref "C7") (pin "1") (pinfunction "1_1") (pintype "passive"))
      (node (ref "FB1") (pin "2") (pinfunction "2_2") (pintype "passive"))
      (node (ref "R12") (pin "1") (pinfunction "1_1") (pintype "passive"))
      (node (ref "U1") (pin "22") (pinfunction "VDDA_22") (pintype "bidirectional"))
    )
    (net (code "212") (name "VGG") (class "Default")
      (node (ref "FB11") (pin "1") (pinfunction "1_1") (pintype "passive"))
      (node (ref "R83") (pin "2") (pinfunction "2_2") (pintype "passive"))
      (node (ref "SP5") (pin "1") (pinfunction "1_1") (pintype "bidirectional"))
      (node (ref "U13") (pin "4") (pinfunction "OUT_4") (pintype "output"))
    )
    (net (code "213") (name "VGG_DAC") (class "Default")
      (node (ref "U1") (pin "54") (pinfunction "PB15_54") (pintype "bidirectional"))
      (node (ref "U13") (pin "1") (pinfunction "+IN_1") (pintype "input"))
    )
    (net (code "214") (name "VREF+") (class "Default")
      (node (ref "C11") (pin "1") (pinfunction "1_1") (pintype "passive"))
      (node (ref "C6") (pin "1") (pinfunction "1_1") (pintype "passive"))
      (node (ref "R12") (pin "2") (pinfunction "2_2") (pintype "passive"))
      (node (ref "U1") (pin "21") (pinfunction "VREF+_21") (pintype "bidirectional"))
    )
    (net (code "215") (name "unconnected-(CN2-E-PadF)") (class "Default")
      (node (ref "CN2") (pin "F") (pinfunction "E_F") (pintype "bidirectional"))
    )
    (net (code "216") (name "unconnected-(CN2-PadB)") (class "Default")
      (node (ref "CN2") (pin "B") (pinfunction "B_B") (pintype "bidirectional"))
    )
    (net (code "217") (name "unconnected-(CN2-PadD)") (class "Default")
      (node (ref "CN2") (pin "D") (pinfunction "D_D") (pintype "bidirectional"))
    )
    (net (code "218") (name "unconnected-(CN5-Pad3)") (class "Default")
      (node (ref "CN5") (pin "3") (pinfunction "3_3") (pintype "bidirectional"))
    )
    (net (code "219") (name "unconnected-(CN6-E-PadF)") (class "Default")
      (node (ref "CN6") (pin "F") (pinfunction "E_F") (pintype "bidirectional"))
    )
    (net (code "220") (name "unconnected-(CN6-PadB)") (class "Default")
      (node (ref "CN6") (pin "B") (pinfunction "B_B") (pintype "bidirectional"))
    )
    (net (code "221") (name "unconnected-(CN7-E-PadF)") (class "Default")
      (node (ref "CN7") (pin "F") (pinfunction "E_F") (pintype "bidirectional"))
    )
    (net (code "222") (name "unconnected-(SW2-Pad3)") (class "Default")
      (node (ref "SW2") (pin "3") (pinfunction "3_3") (pintype "passive"))
    )
    (net (code "223") (name "unconnected-(SW2-Pad6)") (class "Default")
      (node (ref "SW2") (pin "6") (pinfunction "6_6") (pintype "passive"))
    )
    (net (code "224") (name "unconnected-(SW2-Pad7)") (class "Default")
      (node (ref "SW2") (pin "7") (pinfunction "7_7") (pintype "bidirectional"))
    )
    (net (code "225") (name "unconnected-(SW2-Pad8)") (class "Default")
      (node (ref "SW2") (pin "8") (pinfunction "8_8") (pintype "bidirectional"))
    )
    (net (code "226") (name "unconnected-(SW5-Pad7)") (class "Default")
      (node (ref "SW5") (pin "7") (pinfunction "7_7") (pintype "bidirectional"))
    )
    (net (code "227") (name "unconnected-(SW5-Pad8)") (class "Default")
      (node (ref "SW5") (pin "8") (pinfunction "8_8") (pintype "bidirectional"))
    )
    (net (code "228") (name "unconnected-(U1A-PA0-Pad23)") (class "Default")
      (node (ref "U1") (pin "23") (pinfunction "PA0_23") (pintype "bidirectional"))
    )
    (net (code "229") (name "unconnected-(U1A-PA6-Pad31)") (class "Default")
      (node (ref "U1") (pin "31") (pinfunction "PA6_31") (pintype "bidirectional"))
    )
    (net (code "230") (name "unconnected-(U1A-PA7-Pad32)") (class "Default")
      (node (ref "U1") (pin "32") (pinfunction "PA7_32") (pintype "bidirectional"))
    )
    (net (code "231") (name "unconnected-(U1A-PB0-Pad35)") (class "Default")
      (node (ref "U1") (pin "35") (pinfunction "PB0_35") (pintype "bidirectional"))
    )
    (net (code "232") (name "unconnected-(U1A-PB1-Pad36)") (class "Default")
      (node (ref "U1") (pin "36") (pinfunction "PB1_36") (pintype "bidirectional"))
    )
    (net (code "233") (name "unconnected-(U1A-PB3-Pad89)") (class "Default")
      (node (ref "U1") (pin "89") (pinfunction "PB3_89") (pintype "bidirectional"))
    )
    (net (code "234") (name "unconnected-(U1A-PB4-Pad90)") (class "Default")
      (node (ref "U1") (pin "90") (pinfunction "PB4_90") (pintype "bidirectional"))
    )
    (net (code "235") (name "unconnected-(U1A-PB5-Pad91)") (class "Default")
      (node (ref "U1") (pin "91") (pinfunction "PB5_91") (pintype "bidirectional"))
    )
    (net (code "236") (name "unconnected-(U1A-PB6-Pad92)") (class "Default")
      (node (ref "U1") (pin "92") (pinfunction "PB6_92") (pintype "bidirectional"))
    )
    (net (code "237") (name "unconnected-(U1A-PB7-Pad93)") (class "Default")
      (node (ref "U1") (pin "93") (pinfunction "PB7_93") (pintype "bidirectional"))
    )
    (net (code "238") (name "unconnected-(U1A-PB8-Pad95)") (class "Default")
      (node (ref "U1") (pin "95") (pinfunction "PB8_95") (pintype "bidirectional"))
    )
    (net (code "239") (name "unconnected-(U1A-PB9-Pad96)") (class "Default")
      (node (ref "U1") (pin "96") (pinfunction "PB9_96") (pintype "bidirectional"))
    )
    (net (code "240") (name "unconnected-(U1A-PB12-Pad51)") (class "Default")
      (node (ref "U1") (pin "51") (pinfunction "PB12_51") (pintype "bidirectional"))
    )
    (net (code "241") (name "unconnected-(U1A-PB13-Pad52)") (class "Default")
      (node (ref "U1") (pin "52") (pinfunction "PB13_52") (pintype "bidirectional"))
    )
    (net (code "242") (name "unconnected-(U1A-PB14-Pad53)") (class "Default")
      (node (ref "U1") (pin "53") (pinfunction "PB14_53") (pintype "bidirectional"))
    )
    (net (code "243") (name "unconnected-(U1A-PC1-Pad16)") (class "Default")
      (node (ref "U1") (pin "16") (pinfunction "PC1_16") (pintype "bidirectional"))
    )
    (net (code "244") (name "unconnected-(U1A-PC2-Pad17)") (class "Default")
      (node (ref "U1") (pin "17") (pinfunction "PC2_17") (pintype "bidirectional"))
    )
    (net (code "245") (name "unconnected-(U1A-PC3-Pad18)") (class "Default")
      (node (ref "U1") (pin "18") (pinfunction "PC3_18") (pintype "bidirectional"))
    )
    (net (code "246") (name "unconnected-(U1A-PC4-Pad33)") (class "Default")
      (node (ref "U1") (pin "33") (pinfunction "PC4_33") (pintype "bidirectional"))
    )
    (net (code "247") (name "unconnected-(U1A-PC5-Pad34)") (class "Default")
      (node (ref "U1") (pin "34") (pinfunction "PC5_34") (pintype "bidirectional"))
    )
    (net (code "248") (name "unconnected-(U1A-PC6-Pad63)") (class "Default")
      (node (ref "U1") (pin "63") (pinfunction "PC6_63") (pintype "bidirectional"))
    )
    (net (code "249") (name "unconnected-(U1A-PC7-Pad64)") (class "Default")
      (node (ref "U1") (pin "64") (pinfunction "PC7_64") (pintype "bidirectional"))
    )
    (net (code "250") (name "unconnected-(U1A-PC8-Pad65)") (class "Default")
      (node (ref "U1") (pin "65") (pinfunction "PC8_65") (pintype "bidirectional"))
    )
    (net (code "251") (name "unconnected-(U1A-PC13-Pad7)") (class "Default")
      (node (ref "U1") (pin "7") (pinfunction "PC13_7") (pintype "bidirectional"))
    )
    (net (code "252") (name "unconnected-(U1A-PC14-Pad8)") (class "Default")
      (node (ref "U1") (pin "8") (pinfunction "PC14_8") (pintype "bidirectional"))
    )
    (net (code "253") (name "unconnected-(U1A-PC15-Pad9)") (class "Default")
      (node (ref "U1") (pin "9") (pinfunction "PC15_9") (pintype "bidirectional"))
    )
    (net (code "254") (name "unconnected-(U1A-PD2-Pad83)") (class "Default")
      (node (ref "U1") (pin "83") (pinfunction "PD2_83") (pintype "bidirectional"))
    )
    (net (code "255") (name "unconnected-(U1A-PD3-Pad84)") (class "Default")
      (node (ref "U1") (pin "84") (pinfunction "PD3_84") (pintype "bidirectional"))
    )
    (net (code "256") (name "unconnected-(U1A-PD4-Pad85)") (class "Default")
      (node (ref "U1") (pin "85") (pinfunction "PD4_85") (pintype "bidirectional"))
    )
    (net (code "257") (name "unconnected-(U1A-PD6-Pad87)") (class "Default")
      (node (ref "U1") (pin "87") (pinfunction "PD6_87") (pintype "bidirectional"))
    )
    (net (code "258") (name "unconnected-(U1A-PD10-Pad57)") (class "Default")
      (node (ref "U1") (pin "57") (pinfunction "PD10_57") (pintype "bidirectional"))
    )
    (net (code "259") (name "unconnected-(U1A-PD11-Pad58)") (class "Default")
      (node (ref "U1") (pin "58") (pinfunction "PD11_58") (pintype "bidirectional"))
    )
    (net (code "260") (name "unconnected-(U1A-PE6-Pad5)") (class "Default")
      (node (ref "U1") (pin "5") (pinfunction "PE6_5") (pintype "bidirectional"))
    )
    (net (code "261") (name "unconnected-(U1A-PE7-Pad38)") (class "Default")
      (node (ref "U1") (pin "38") (pinfunction "PE7_38") (pintype "bidirectional"))
    )
    (net (code "262") (name "unconnected-(U1A-PE8-Pad39)") (class "Default")
      (node (ref "U1") (pin "39") (pinfunction "PE8_39") (pintype "bidirectional"))
    )
    (net (code "263") (name "unconnected-(U1A-PE9-Pad40)") (class "Default")
      (node (ref "U1") (pin "40") (pinfunction "PE9_40") (pintype "bidirectional"))
    )
    (net (code "264") (name "unconnected-(U1A-PE10-Pad41)") (class "Default")
      (node (ref "U1") (pin "41") (pinfunction "PE10_41") (pintype "bidirectional"))
    )
    (net (code "265") (name "unconnected-(U1A-PE11-Pad42)") (class "Default")
      (node (ref "U1") (pin "42") (pinfunction "PE11_42") (pintype "bidirectional"))
    )
    (net (code "266") (name "unconnected-(U1A-PE12-Pad43)") (class "Default")
      (node (ref "U1") (pin "43") (pinfunction "PE12_43") (pintype "bidirectional"))
    )
    (net (code "267") (name "unconnected-(U1A-PE13-Pad44)") (class "Default")
      (node (ref "U1") (pin "44") (pinfunction "PE13_44") (pintype "bidirectional"))
    )
    (net (code "268") (name "unconnected-(U1A-PE14-Pad45)") (class "Default")
      (node (ref "U1") (pin "45") (pinfunction "PE14_45") (pintype "bidirectional"))
    )
    (net (code "269") (name "unconnected-(U1A-PE15-Pad46)") (class "Default")
      (node (ref "U1") (pin "46") (pinfunction "PE15_46") (pintype "bidirectional"))
    )
    (net (code "270") (name "unconnected-(U3-DZ-PadA2)") (class "Default")
      (node (ref "U3") (pin "A2") (pinfunction "DZ_A2") (pintype "bidirectional"))
    )
    (net (code "271") (name "unconnected-(U3-PD1-PadB1)") (class "Default")
      (node (ref "U3") (pin "B1") (pinfunction "PD1_B1") (pintype "bidirectional"))
    )
    (net (code "272") (name "unconnected-(U3-PD2-PadC2)") (class "Default")
      (node (ref "U3") (pin "C2") (pinfunction "PD2_C2") (pintype "bidirectional"))
    )
    (net (code "273") (name "unconnected-(U3-PUP-PadB2)") (class "Default")
      (node (ref "U3") (pin "B2") (pinfunction "PUP_B2") (pintype "bidirectional"))
    )
    (net (code "274") (name "unconnected-(U10-BYPASS-Pad7)") (class "Default")
      (node (ref "U10") (pin "7") (pinfunction "BYPASS_7") (pintype "passive"))
    )
    (net (code "275") (name "unconnected-(U10-GAIN-Pad1)") (class "Default")
      (node (ref "U10") (pin "1") (pinfunction "GAIN_1") (pintype "passive"))
    )
    (net (code "276") (name "unconnected-(U10-GAIN-Pad8)") (class "Default")
      (node (ref "U10") (pin "8") (pinfunction "GAIN_8") (pintype "passive"))
    )
    (net (code "277") (name "unconnected-(U11-G2-Pad4)") (class "Default")
      (node (ref "U11") (pin "4") (pinfunction "G2_4") (pintype "bidirectional"))
    )
    (net (code "278") (name "unconnected-(U11-IF-Pad2)") (class "Default")
      (node (ref "U11") (pin "2") (pinfunction "IF_2") (pintype "bidirectional"))
    )
    (net (code "279") (name "unconnected-(U11-LO-Pad6)") (class "Default")
      (node (ref "U11") (pin "6") (pinfunction "LO_6") (pintype "bidirectional"))
    )
    (net (code "280") (name "unconnected-(U15-CLK--Pad5)") (class "Default")
      (node (ref "U15") (pin "5") (pinfunction "CLK-_5") (pintype "output"))
    )
    (net (code "281") (name "unconnected-(U15-NC-Pad1)") (class "Default")
      (node (ref "U15") (pin "1") (pinfunction "NC_1") (pintype "no_connect"))
    )
    (net (code "282") (name "unconnected-(U16-OSC_E-Pad7)") (class "Default")
      (node (ref "U16") (pin "7") (pinfunction "OSC_E_7") (pintype "bidirectional"))
    )
    (net (code "283") (name "unconnected-(U16-OUT_B-Pad5)") (class "Default")
      (node (ref "U16") (pin "5") (pinfunction "OUT_B_5") (pintype "bidirectional"))
    )
    (net (code "284") (name "~{BACK}") (class "Default")
      (node (ref "R27") (pin "1") (pinfunction "1_1") (pintype "passive"))
      (node (ref "SW4") (pin "1") (pinfunction "1_1") (pintype "bidirectional"))
      (node (ref "U1") (pin "82") (pinfunction "PD1_82") (pintype "bidirectional"))
    )
    (net (code "285") (name "~{BOOT0}") (class "Default")
      (node (ref "R19") (pin "1") (pinfunction "1_1") (pintype "passive"))
      (node (ref "U1") (pin "88") (pinfunction "PD7_88") (pintype "bidirectional"))
      (node (ref "U1") (pin "94") (pinfunction "BOOT0_94") (pintype "bidirectional"))
    )
    (net (code "286") (name "~{EXT-PTT}") (class "Default")
      (node (ref "R23") (pin "2") (pinfunction "2_2") (pintype "passive"))
      (node (ref "U1") (pin "55") (pinfunction "PD8_55") (pintype "bidirectional"))
    )
    (net (code "287") (name "~{SELECT}") (class "Default")
      (node (ref "R22") (pin "1") (pinfunction "1_1") (pintype "passive"))
      (node (ref "SW3") (pin "1") (pinfunction "1_1") (pintype "bidirectional"))
      (node (ref "U1") (pin "81") (pinfunction "PD0_81") (pintype "bidirectional"))
    )
    (net (code "288") (name "~{TEST}") (class "Default")
      (node (ref "J1") (pin "1") (pinfunction "1_1") (pintype "bidirectional"))
      (node (ref "R7") (pin "2") (pinfunction "2_2") (pintype "passive"))
      (node (ref "U1") (pin "56") (pinfunction "PD9_56") (pintype "bidirectional"))
    )
  )
)
